# Tri_Btate_Bank.net
KiCad netlist of a schematic drawn in Altium Designer
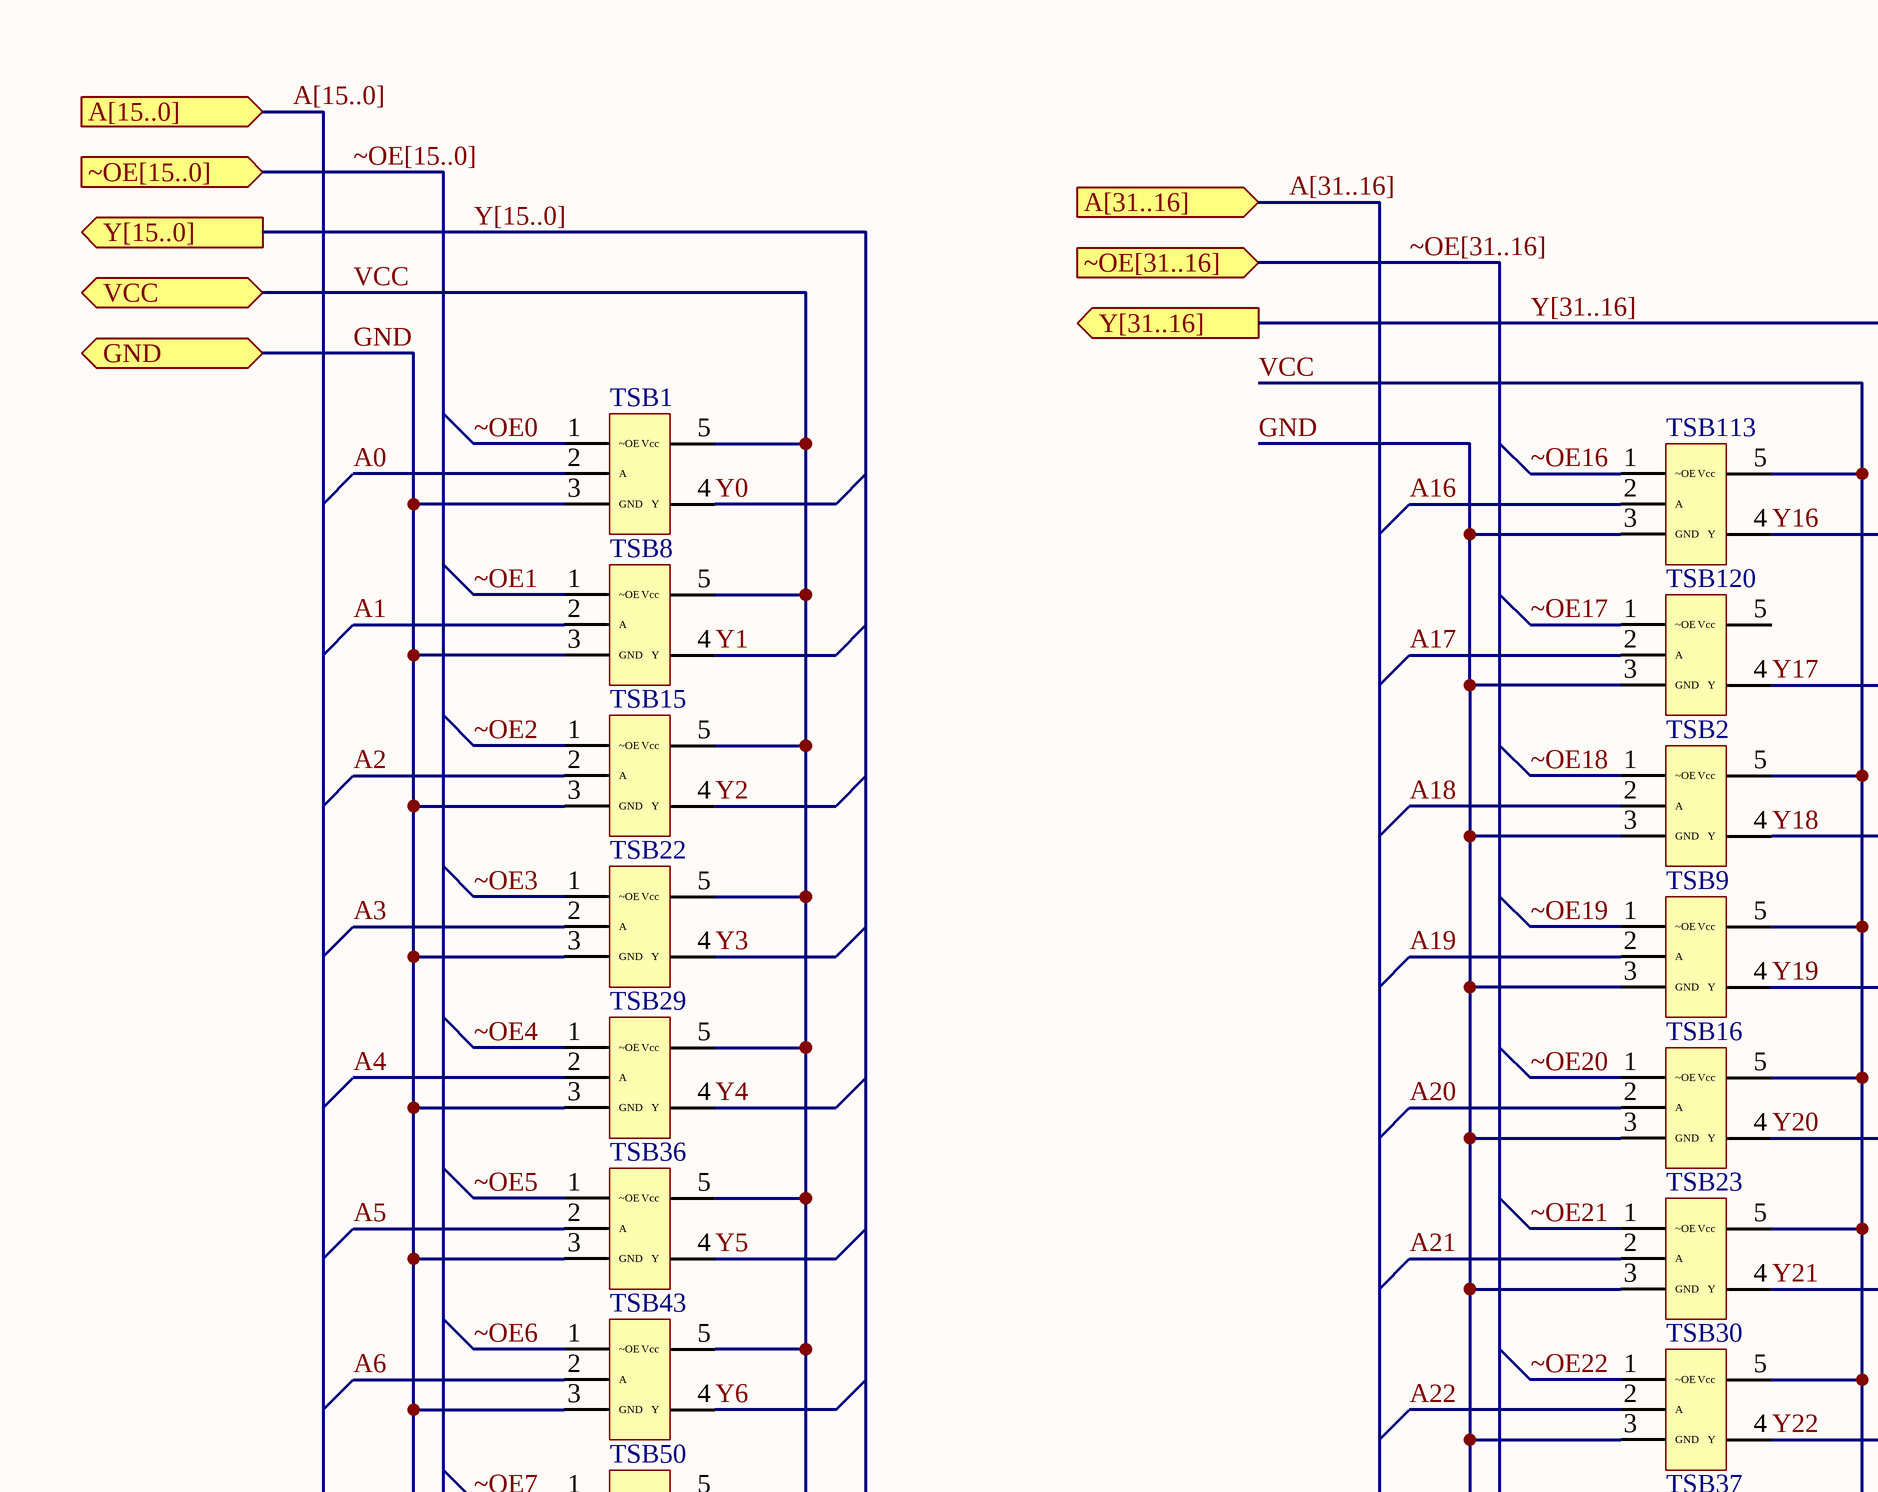
[diagram p0: Tri_Btate_Bank.SchDoc, top column 1 of 5]
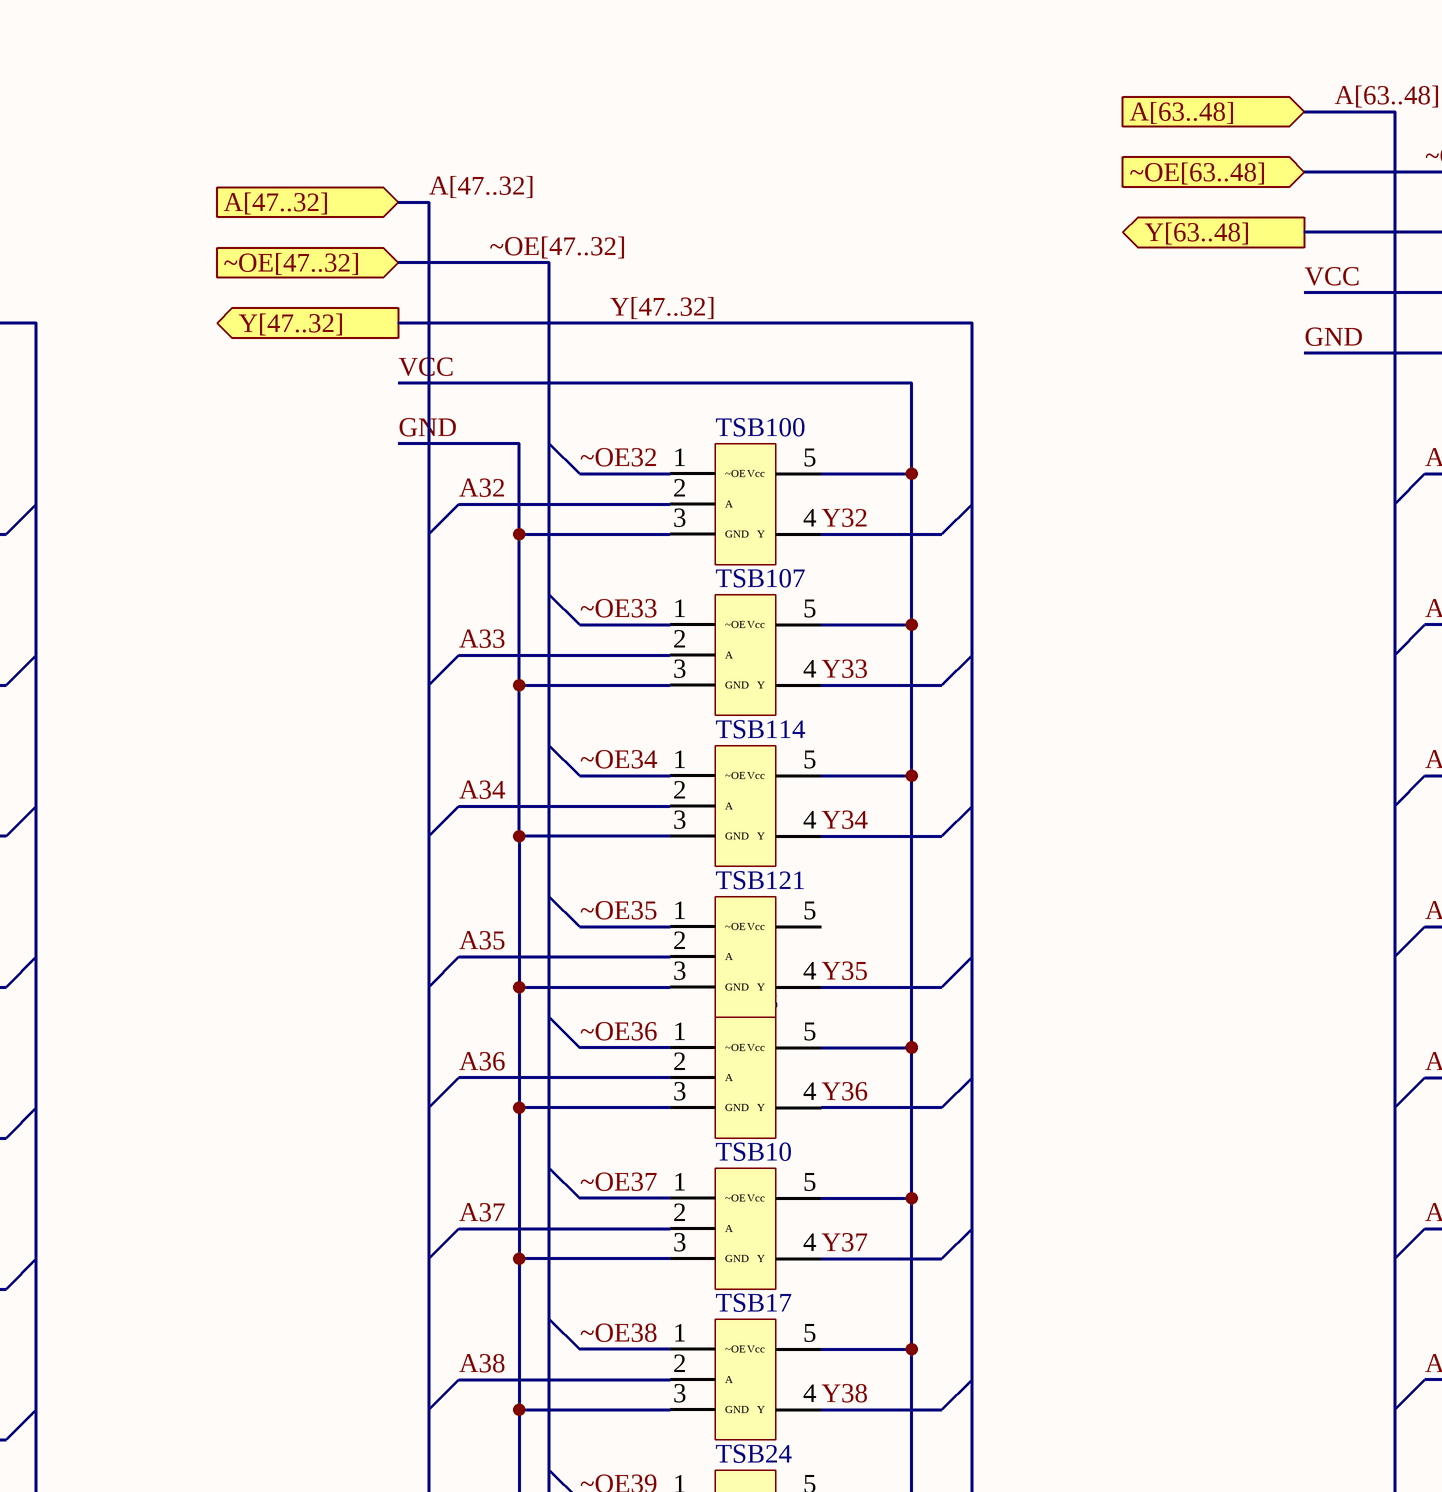
[diagram p1: Tri_Btate_Bank.SchDoc, top column 2 of 5]
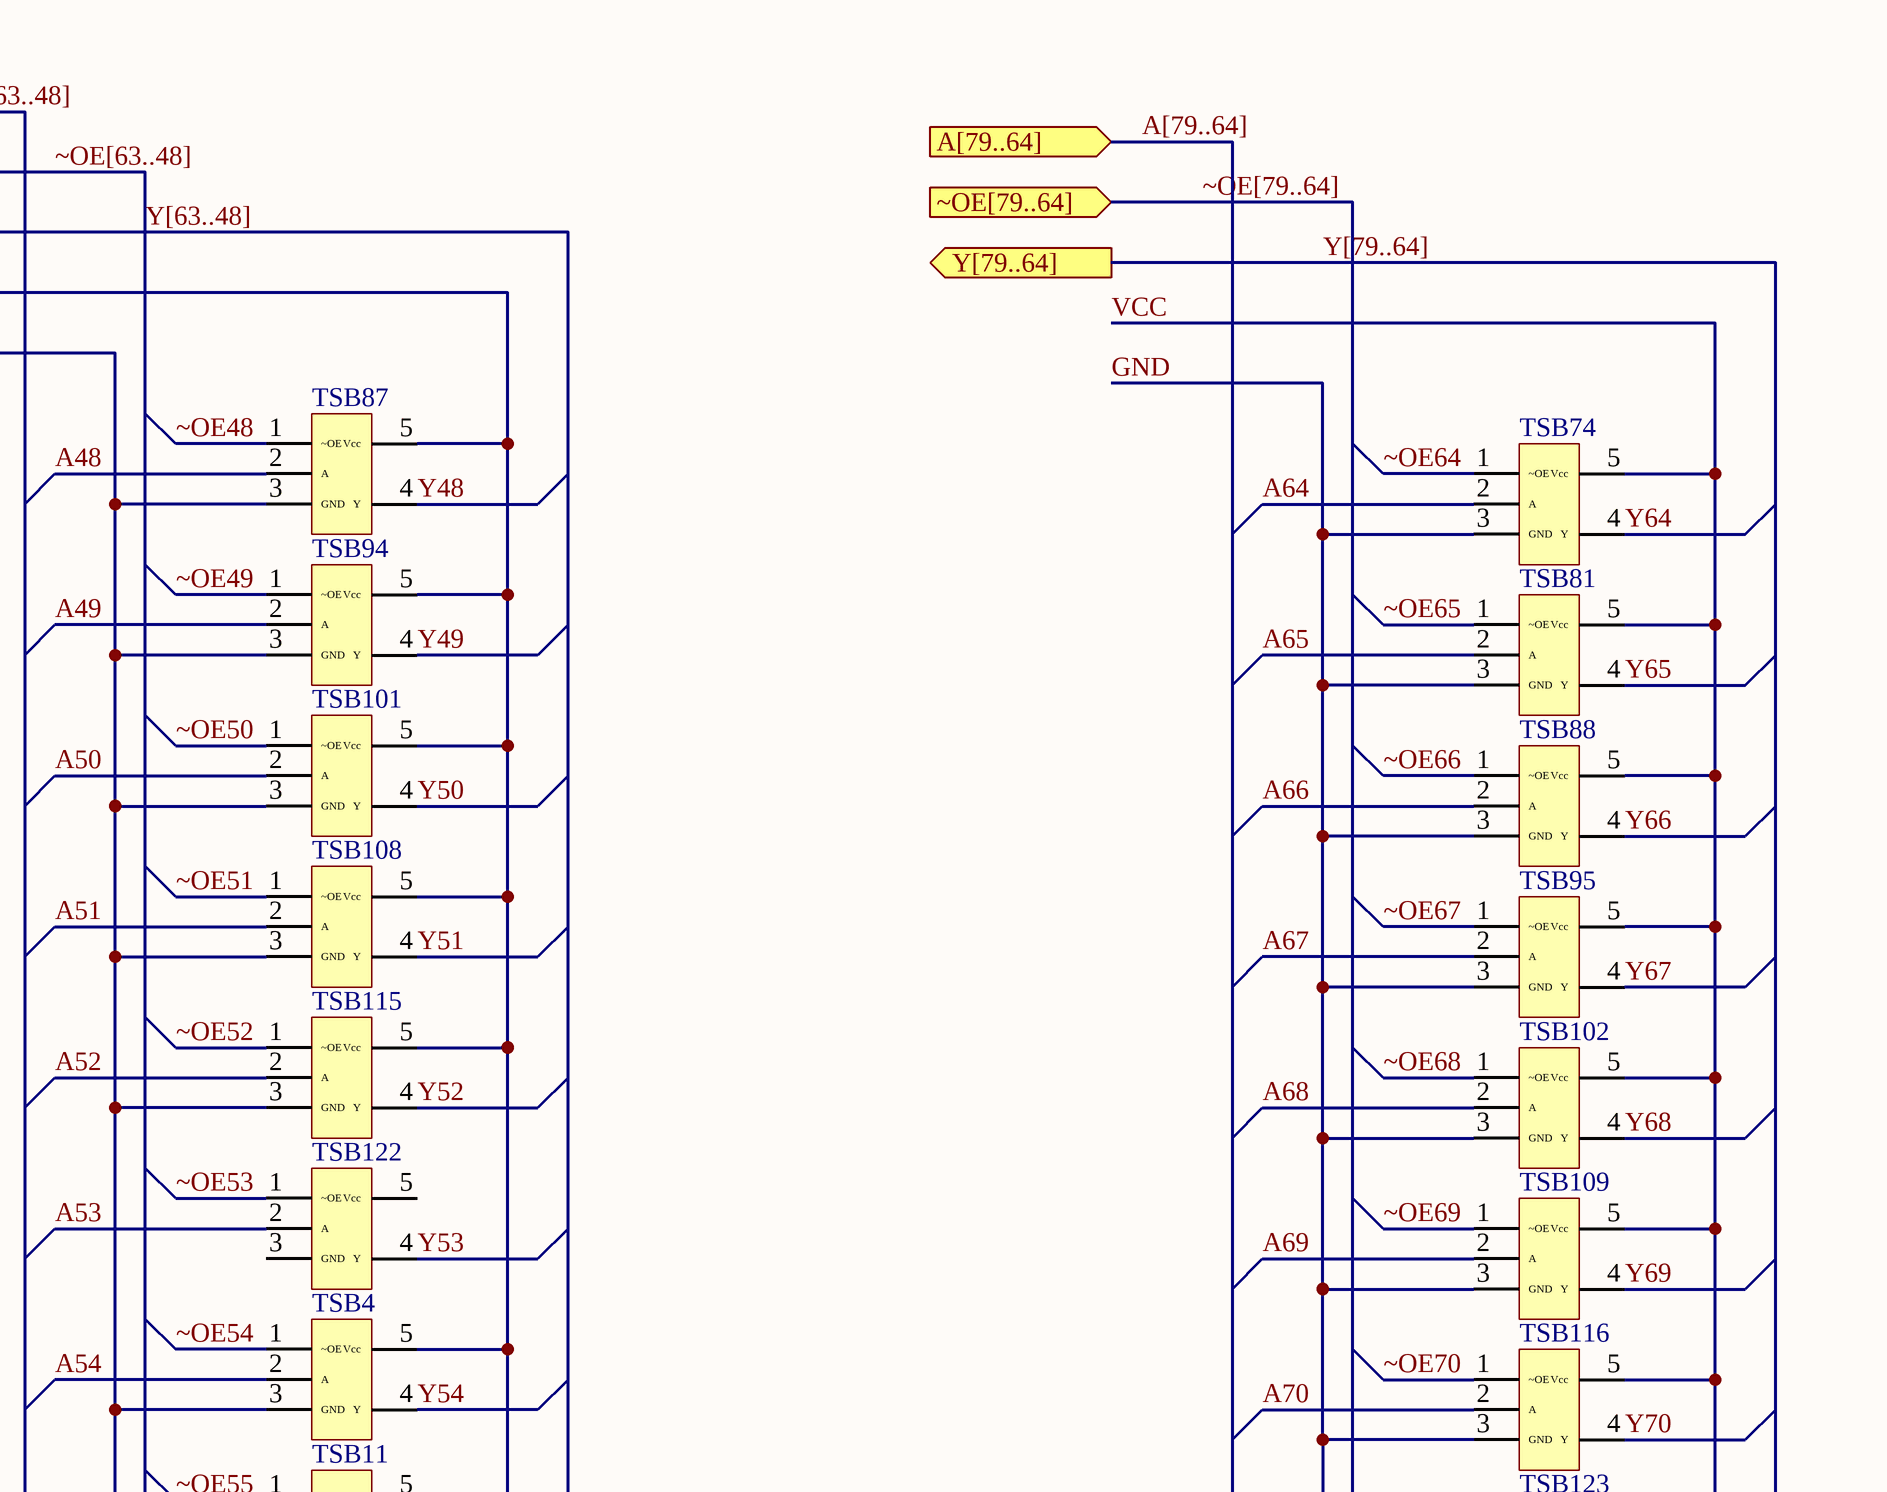
[diagram p2: Tri_Btate_Bank.SchDoc, top column 3 of 5]
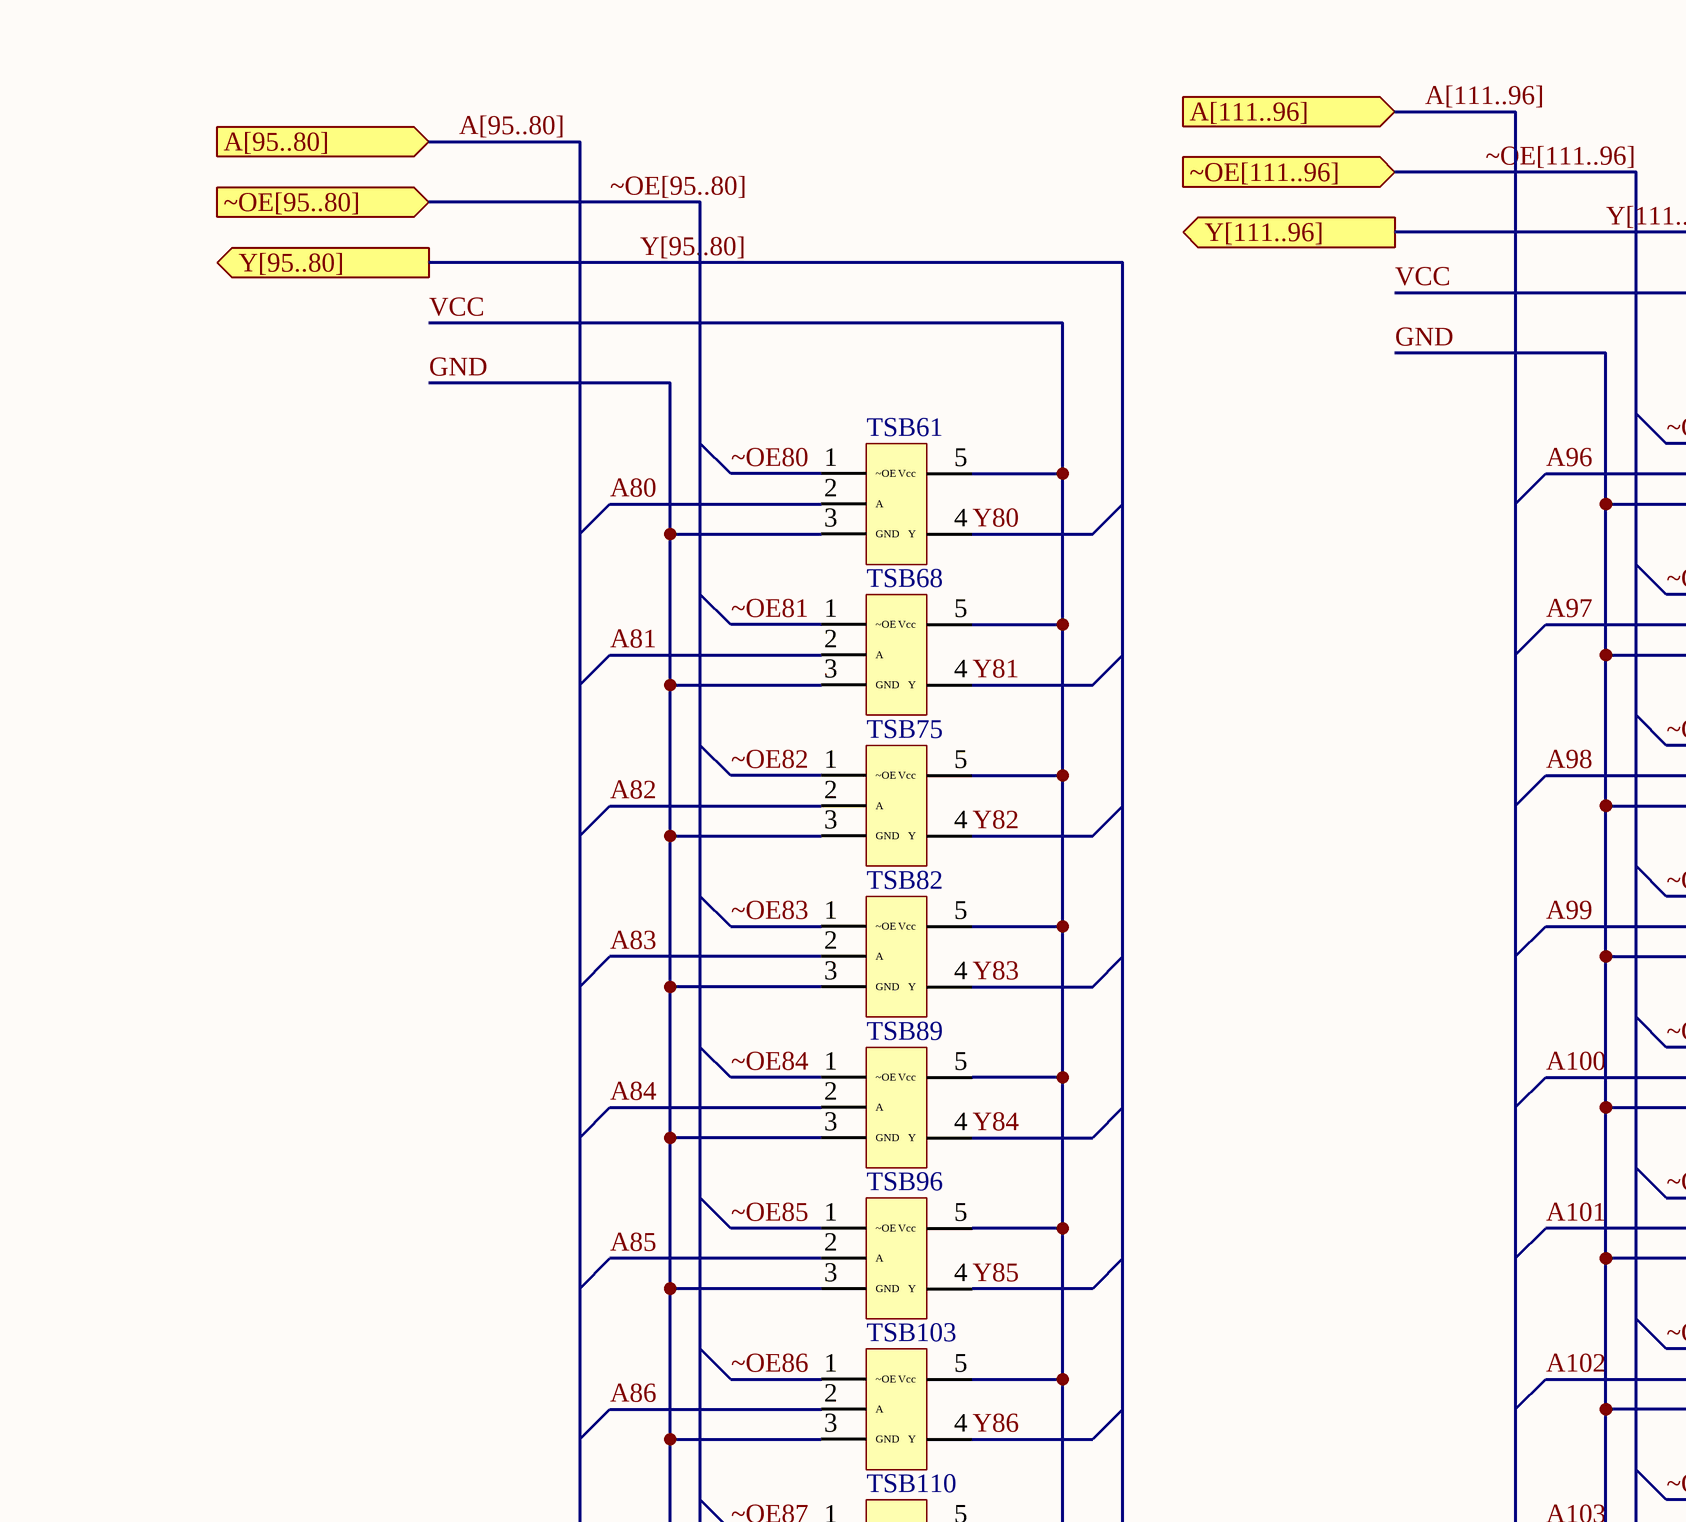
[diagram p3: Tri_Btate_Bank.SchDoc, top column 4 of 5]
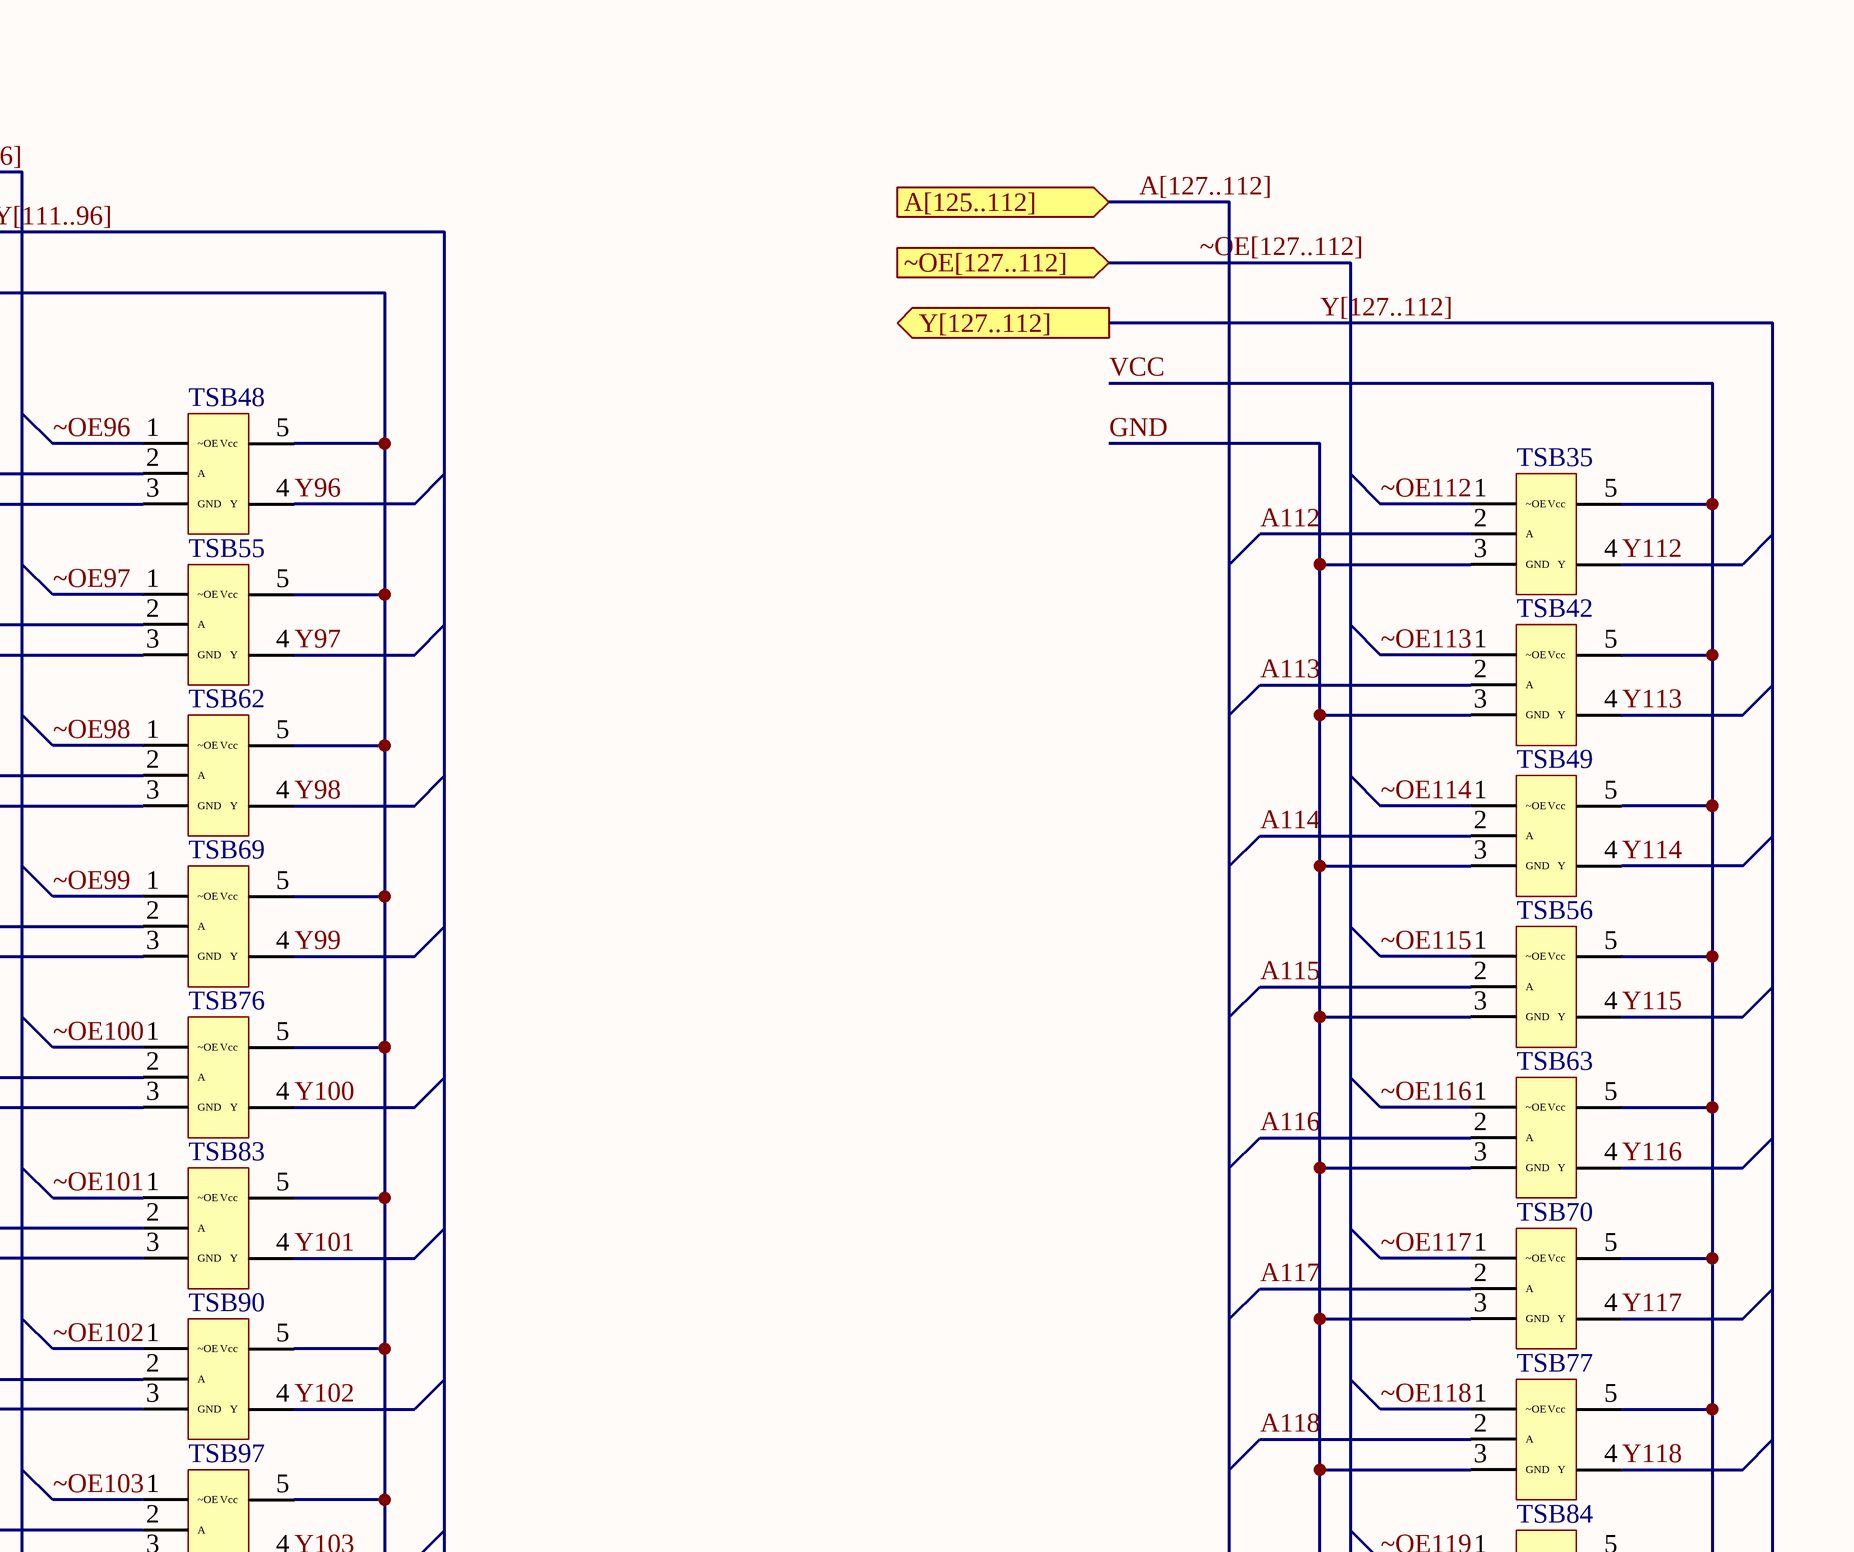
[diagram p4: Tri_Btate_Bank.SchDoc, top column 5 of 5]
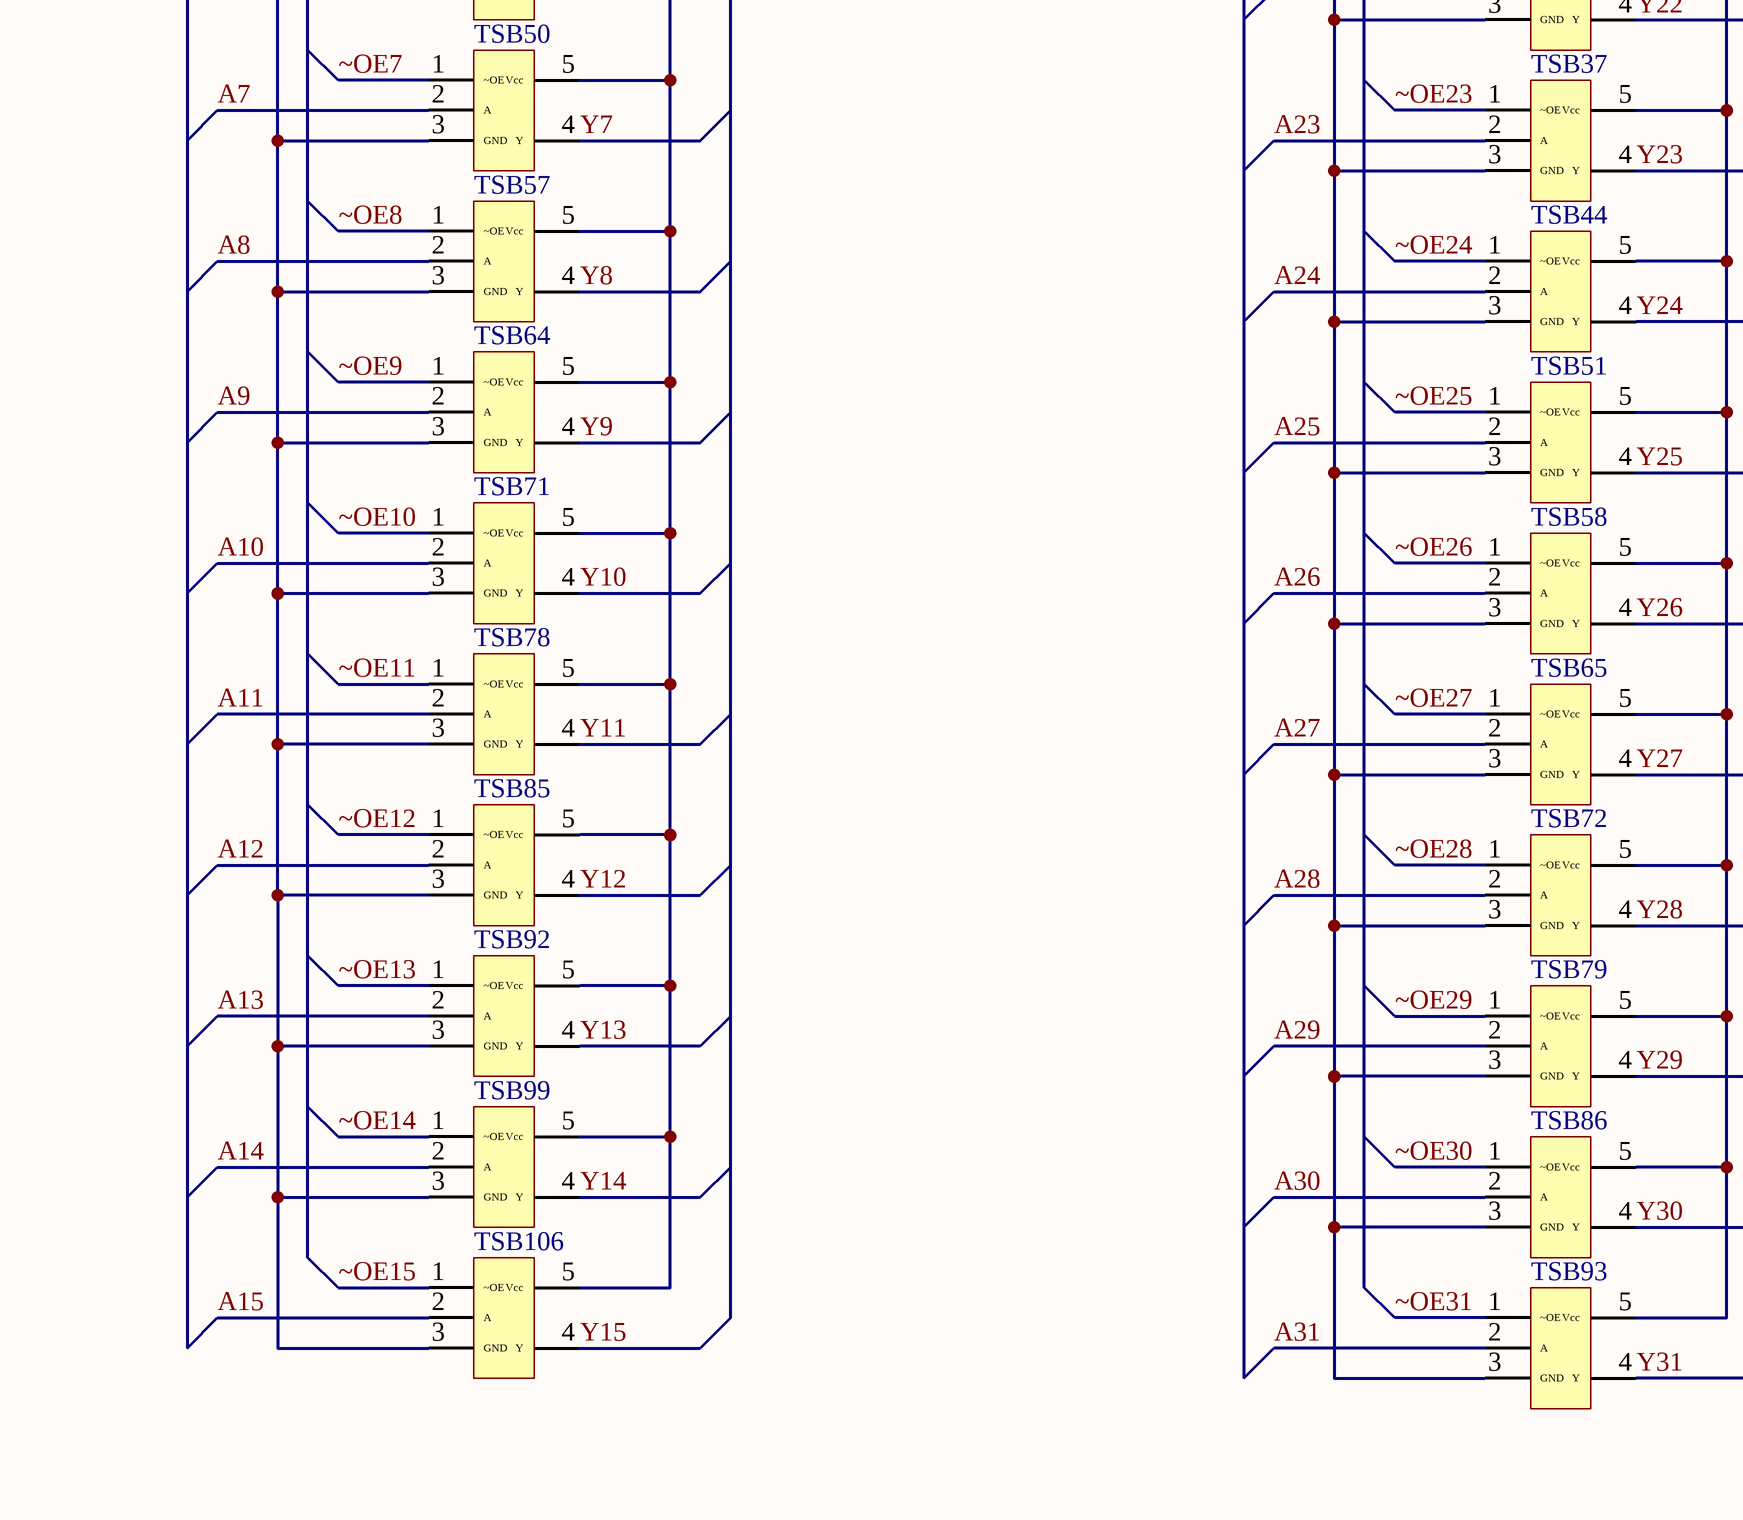
[diagram p5: Tri_Btate_Bank.SchDoc, bottom column 1 of 5]
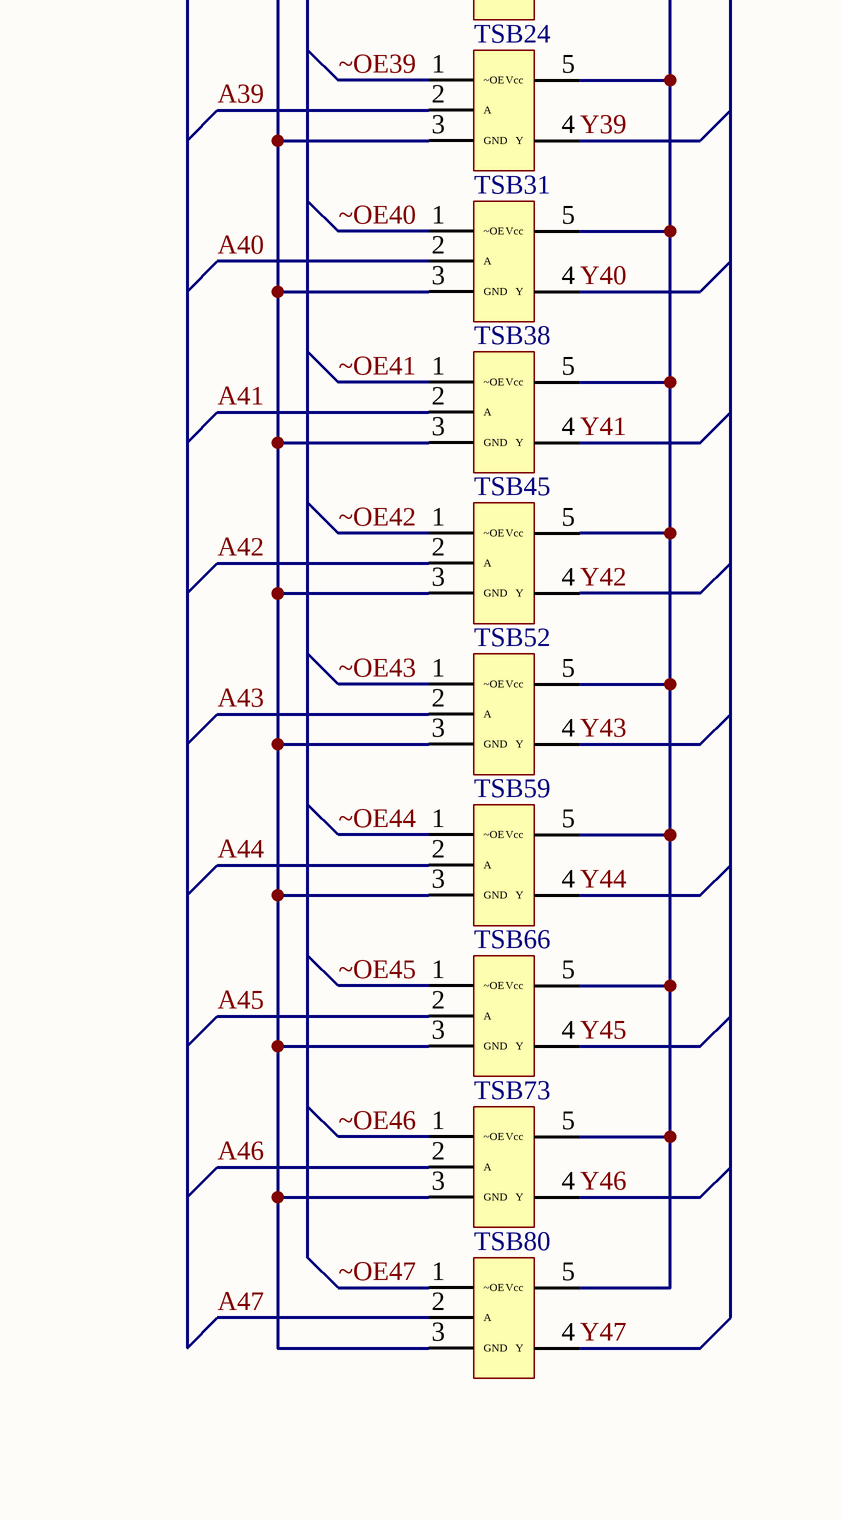
[diagram p6: Tri_Btate_Bank.SchDoc, bottom column 2 of 5]
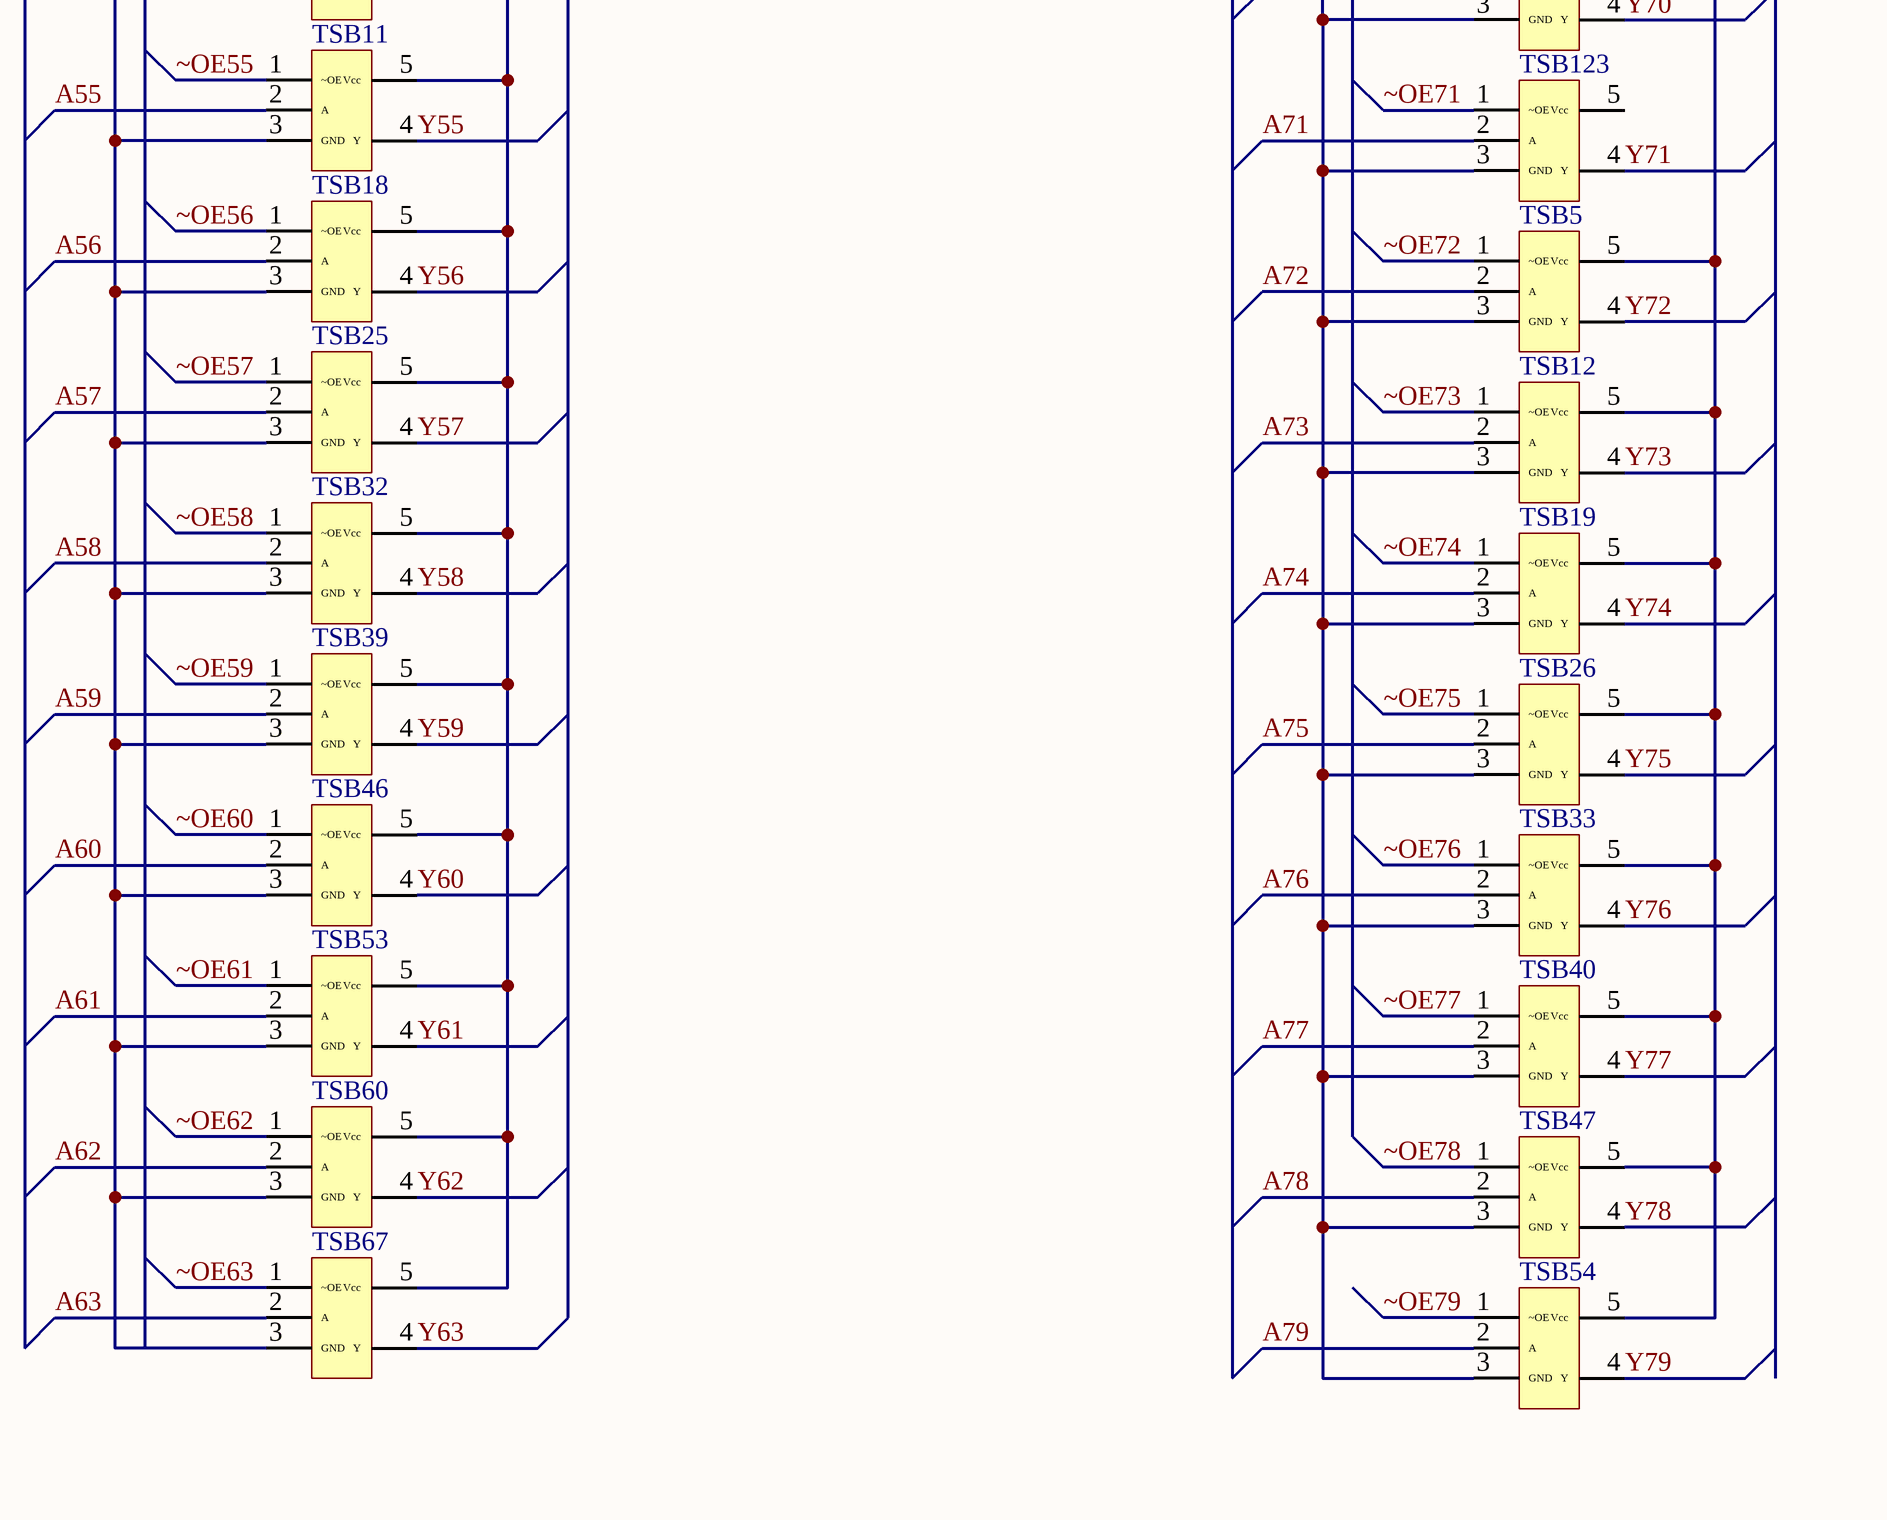
[diagram p7: Tri_Btate_Bank.SchDoc, bottom column 3 of 5]
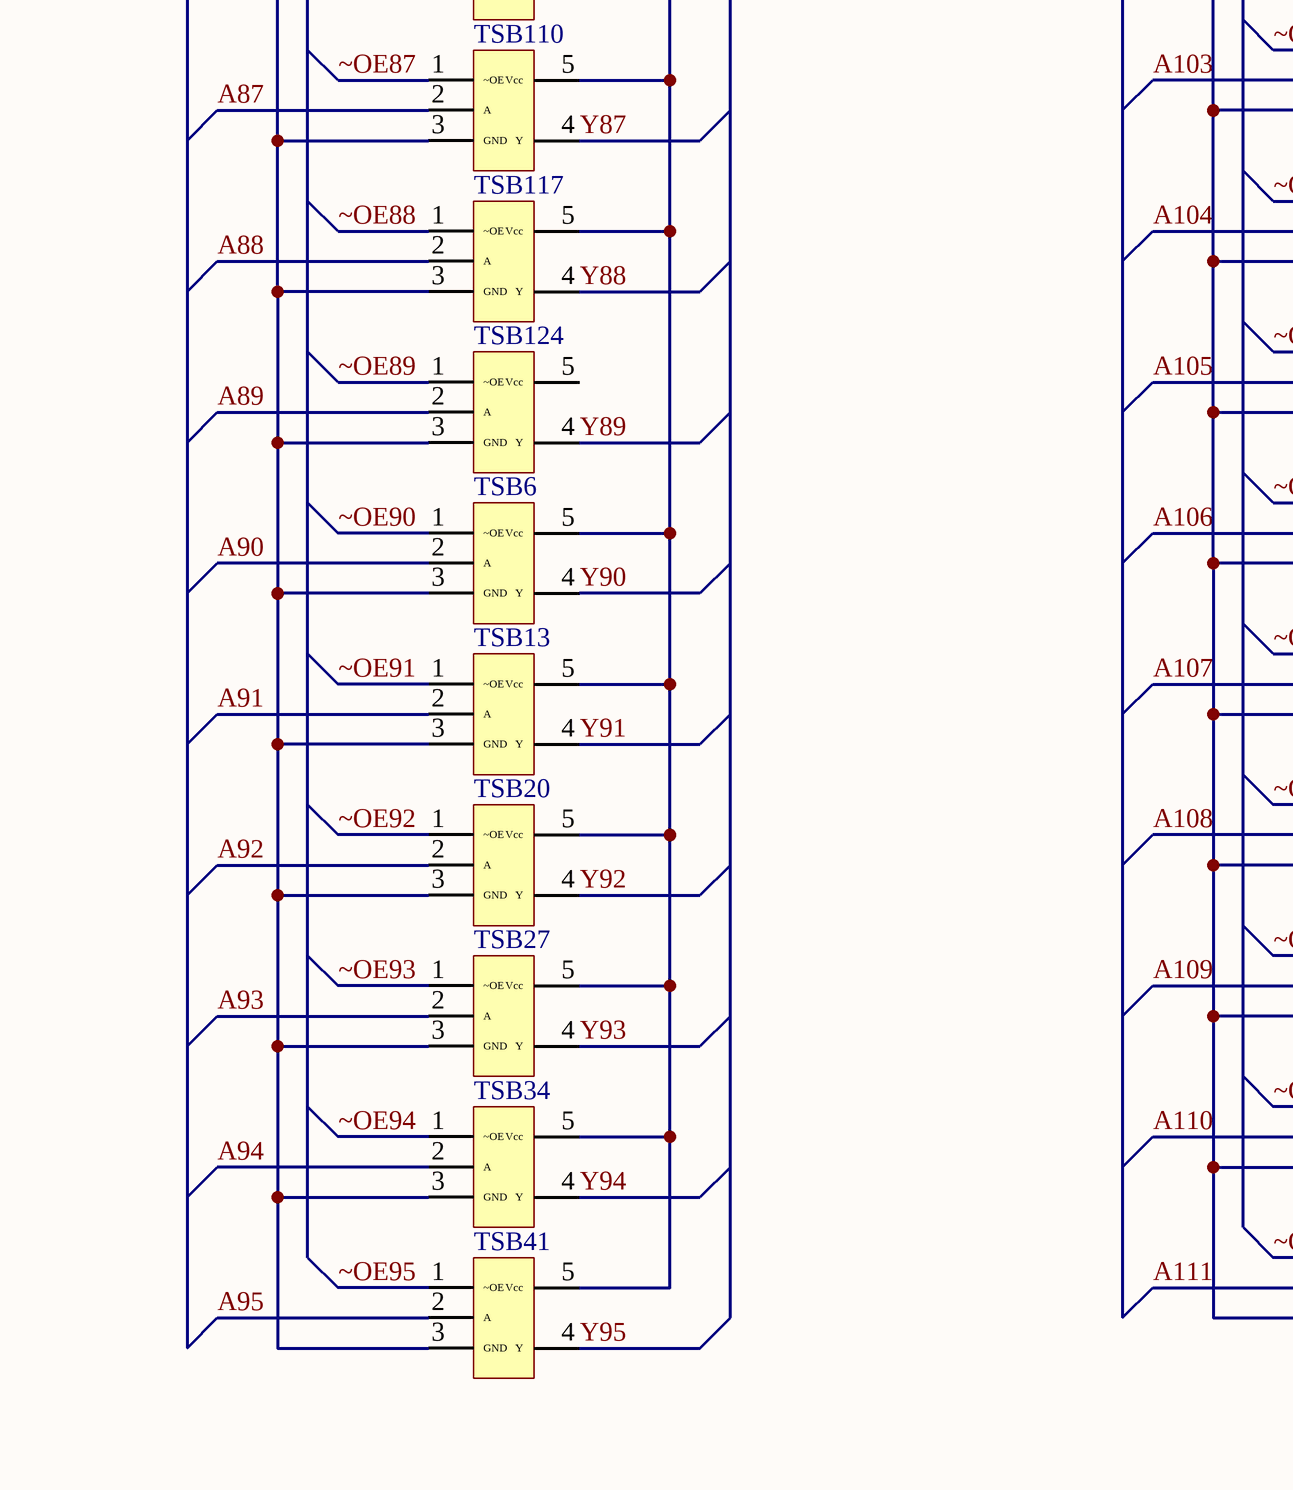
[diagram p8: Tri_Btate_Bank.SchDoc, bottom column 4 of 5]
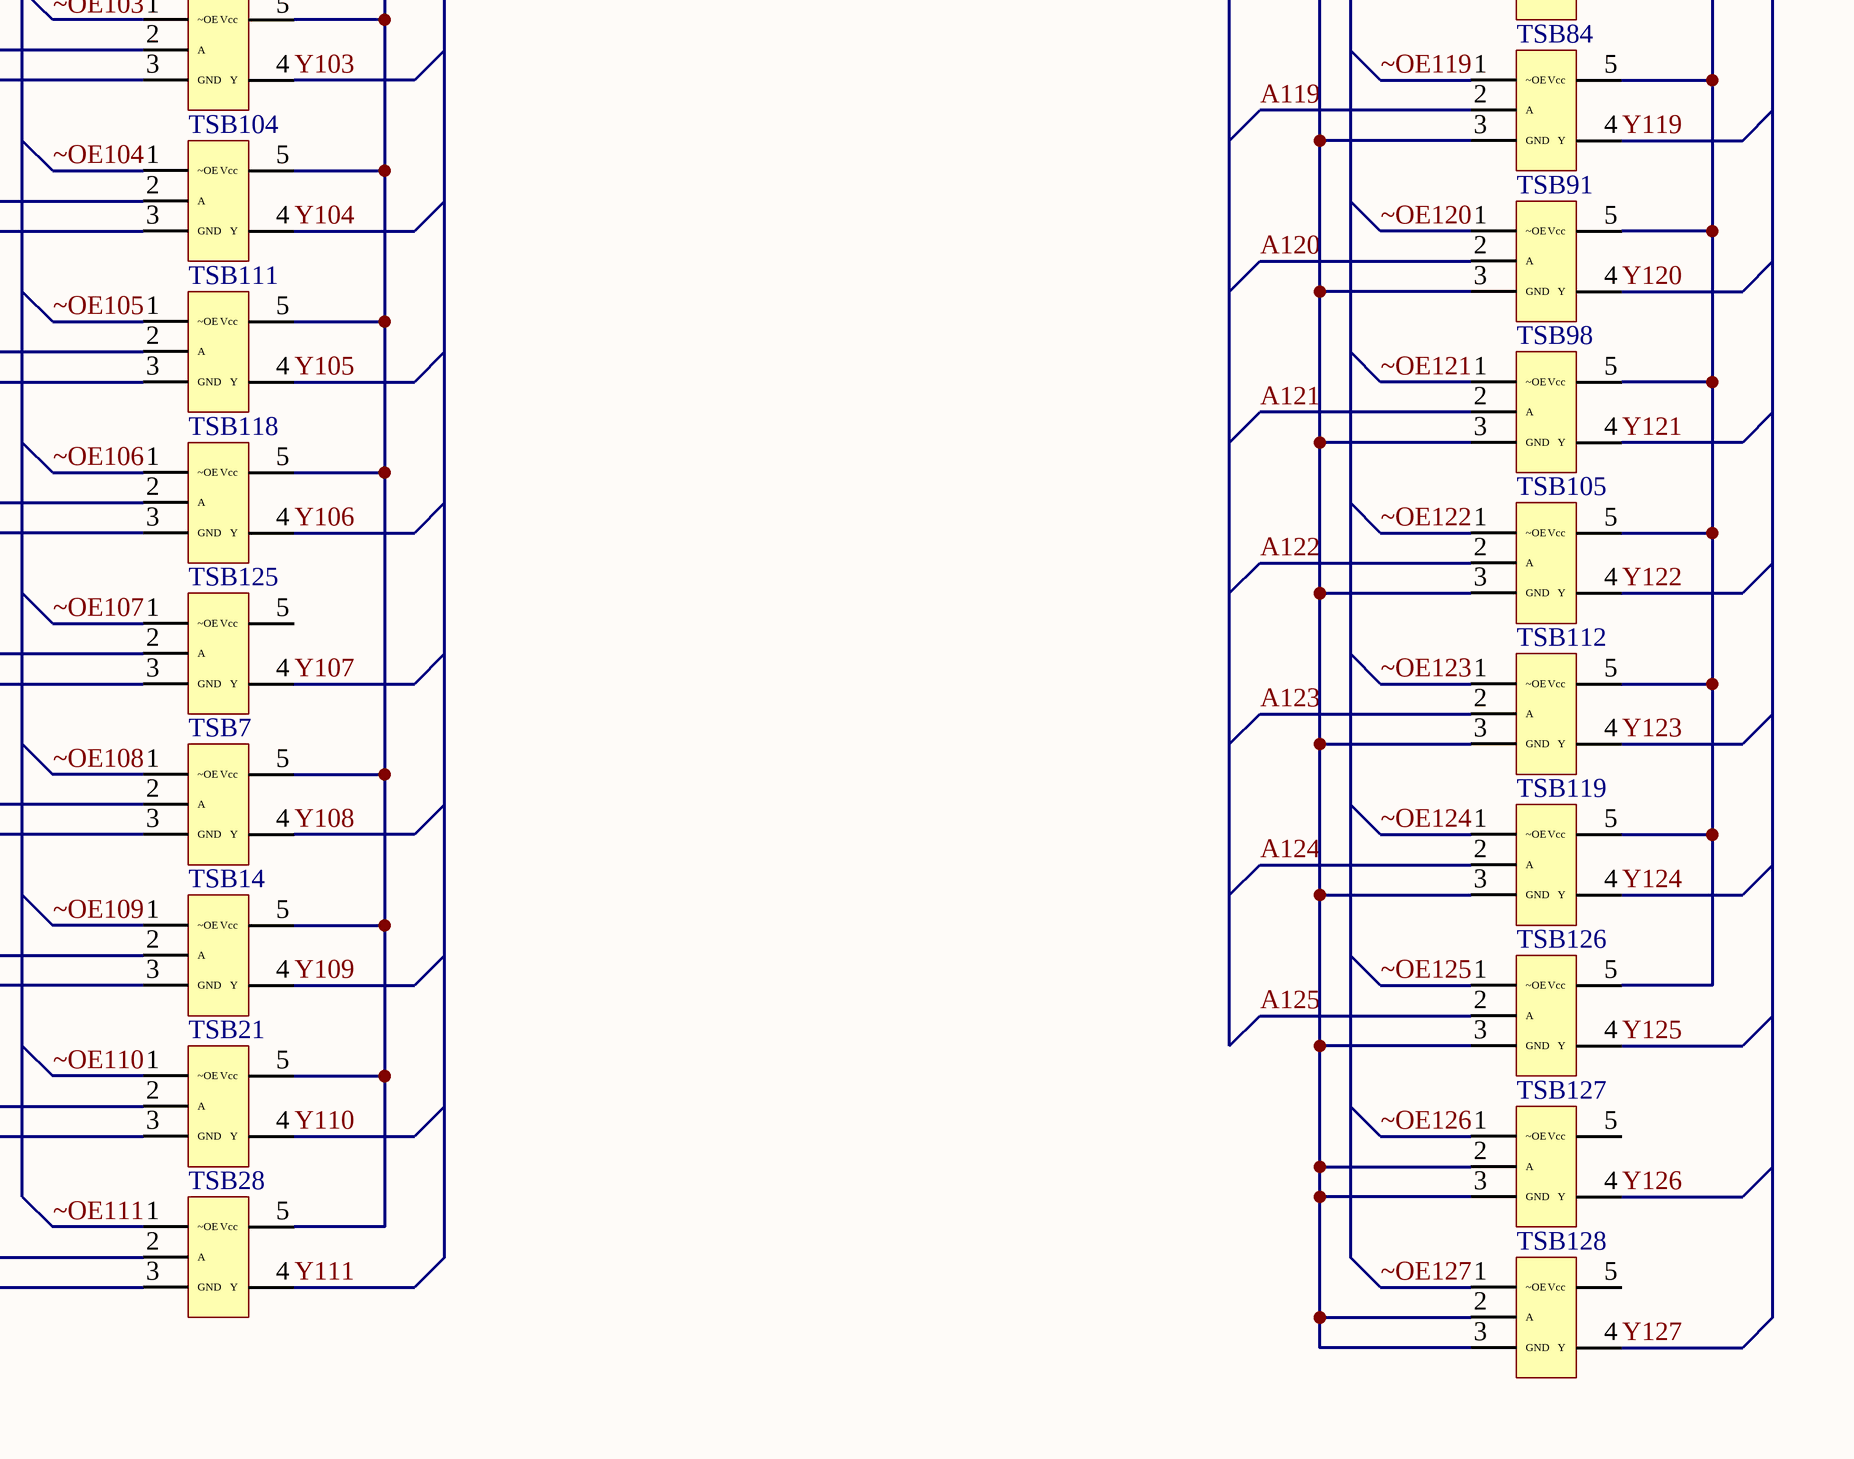
[diagram p9: Tri_Btate_Bank.SchDoc, bottom column 5 of 5]

(export (version "E")
  (design (tool "Eeschema 10.0.6"))
  (components
    (comp (ref "TSB1")
      (value "Tri-State Buffer Non-Inverting")
      (description "IC BUFF DVR TRI-ST N-INV 5TSSOP")
      (fields
        (field (name "MANUFACTURER") "NXP Semiconductors")
        (field (name "MANUFACTURER PART NUMBER") "74LVC1G125GW,125")
      )
      (libsource (lib "NORMS_LIB") (part "Tri-State Buffer Non-Inverting"))
    )
    (comp (ref "TSB2")
      (value "Tri-State Buffer Non-Inverting")
      (description "IC BUFF DVR TRI-ST N-INV 5TSSOP")
      (fields
        (field (name "MANUFACTURER") "NXP Semiconductors")
        (field (name "MANUFACTURER PART NUMBER") "74LVC1G125GW,125")
      )
      (libsource (lib "NORMS_LIB") (part "Tri-State Buffer Non-Inverting"))
    )
    (comp (ref "TSB3")
      (value "Tri-State Buffer Non-Inverting")
      (description "IC BUFF DVR TRI-ST N-INV 5TSSOP")
      (fields
        (field (name "MANUFACTURER") "NXP Semiconductors")
        (field (name "MANUFACTURER PART NUMBER") "74LVC1G125GW,125")
      )
      (libsource (lib "NORMS_LIB") (part "Tri-State Buffer Non-Inverting"))
    )
    (comp (ref "TSB4")
      (value "Tri-State Buffer Non-Inverting")
      (description "IC BUFF DVR TRI-ST N-INV 5TSSOP")
      (fields
        (field (name "MANUFACTURER") "NXP Semiconductors")
        (field (name "MANUFACTURER PART NUMBER") "74LVC1G125GW,125")
      )
      (libsource (lib "NORMS_LIB") (part "Tri-State Buffer Non-Inverting"))
    )
    (comp (ref "TSB5")
      (value "Tri-State Buffer Non-Inverting")
      (description "IC BUFF DVR TRI-ST N-INV 5TSSOP")
      (fields
        (field (name "MANUFACTURER") "NXP Semiconductors")
        (field (name "MANUFACTURER PART NUMBER") "74LVC1G125GW,125")
      )
      (libsource (lib "NORMS_LIB") (part "Tri-State Buffer Non-Inverting"))
    )
    (comp (ref "TSB6")
      (value "Tri-State Buffer Non-Inverting")
      (description "IC BUFF DVR TRI-ST N-INV 5TSSOP")
      (fields
        (field (name "MANUFACTURER") "NXP Semiconductors")
        (field (name "MANUFACTURER PART NUMBER") "74LVC1G125GW,125")
      )
      (libsource (lib "NORMS_LIB") (part "Tri-State Buffer Non-Inverting"))
    )
    (comp (ref "TSB7")
      (value "Tri-State Buffer Non-Inverting")
      (description "IC BUFF DVR TRI-ST N-INV 5TSSOP")
      (fields
        (field (name "MANUFACTURER") "NXP Semiconductors")
        (field (name "MANUFACTURER PART NUMBER") "74LVC1G125GW,125")
      )
      (libsource (lib "NORMS_LIB") (part "Tri-State Buffer Non-Inverting"))
    )
    (comp (ref "TSB8")
      (value "Tri-State Buffer Non-Inverting")
      (description "IC BUFF DVR TRI-ST N-INV 5TSSOP")
      (fields
        (field (name "MANUFACTURER") "NXP Semiconductors")
        (field (name "MANUFACTURER PART NUMBER") "74LVC1G125GW,125")
      )
      (libsource (lib "NORMS_LIB") (part "Tri-State Buffer Non-Inverting"))
    )
    (comp (ref "TSB9")
      (value "Tri-State Buffer Non-Inverting")
      (description "IC BUFF DVR TRI-ST N-INV 5TSSOP")
      (fields
        (field (name "MANUFACTURER") "NXP Semiconductors")
        (field (name "MANUFACTURER PART NUMBER") "74LVC1G125GW,125")
      )
      (libsource (lib "NORMS_LIB") (part "Tri-State Buffer Non-Inverting"))
    )
    (comp (ref "TSB10")
      (value "Tri-State Buffer Non-Inverting")
      (description "IC BUFF DVR TRI-ST N-INV 5TSSOP")
      (fields
        (field (name "MANUFACTURER") "NXP Semiconductors")
        (field (name "MANUFACTURER PART NUMBER") "74LVC1G125GW,125")
      )
      (libsource (lib "NORMS_LIB") (part "Tri-State Buffer Non-Inverting"))
    )
    (comp (ref "TSB11")
      (value "Tri-State Buffer Non-Inverting")
      (description "IC BUFF DVR TRI-ST N-INV 5TSSOP")
      (fields
        (field (name "MANUFACTURER") "NXP Semiconductors")
        (field (name "MANUFACTURER PART NUMBER") "74LVC1G125GW,125")
      )
      (libsource (lib "NORMS_LIB") (part "Tri-State Buffer Non-Inverting"))
    )
    (comp (ref "TSB12")
      (value "Tri-State Buffer Non-Inverting")
      (description "IC BUFF DVR TRI-ST N-INV 5TSSOP")
      (fields
        (field (name "MANUFACTURER") "NXP Semiconductors")
        (field (name "MANUFACTURER PART NUMBER") "74LVC1G125GW,125")
      )
      (libsource (lib "NORMS_LIB") (part "Tri-State Buffer Non-Inverting"))
    )
    (comp (ref "TSB13")
      (value "Tri-State Buffer Non-Inverting")
      (description "IC BUFF DVR TRI-ST N-INV 5TSSOP")
      (fields
        (field (name "MANUFACTURER") "NXP Semiconductors")
        (field (name "MANUFACTURER PART NUMBER") "74LVC1G125GW,125")
      )
      (libsource (lib "NORMS_LIB") (part "Tri-State Buffer Non-Inverting"))
    )
    (comp (ref "TSB14")
      (value "Tri-State Buffer Non-Inverting")
      (description "IC BUFF DVR TRI-ST N-INV 5TSSOP")
      (fields
        (field (name "MANUFACTURER") "NXP Semiconductors")
        (field (name "MANUFACTURER PART NUMBER") "74LVC1G125GW,125")
      )
      (libsource (lib "NORMS_LIB") (part "Tri-State Buffer Non-Inverting"))
    )
    (comp (ref "TSB15")
      (value "Tri-State Buffer Non-Inverting")
      (description "IC BUFF DVR TRI-ST N-INV 5TSSOP")
      (fields
        (field (name "MANUFACTURER") "NXP Semiconductors")
        (field (name "MANUFACTURER PART NUMBER") "74LVC1G125GW,125")
      )
      (libsource (lib "NORMS_LIB") (part "Tri-State Buffer Non-Inverting"))
    )
    (comp (ref "TSB16")
      (value "Tri-State Buffer Non-Inverting")
      (description "IC BUFF DVR TRI-ST N-INV 5TSSOP")
      (fields
        (field (name "MANUFACTURER") "NXP Semiconductors")
        (field (name "MANUFACTURER PART NUMBER") "74LVC1G125GW,125")
      )
      (libsource (lib "NORMS_LIB") (part "Tri-State Buffer Non-Inverting"))
    )
    (comp (ref "TSB17")
      (value "Tri-State Buffer Non-Inverting")
      (description "IC BUFF DVR TRI-ST N-INV 5TSSOP")
      (fields
        (field (name "MANUFACTURER") "NXP Semiconductors")
        (field (name "MANUFACTURER PART NUMBER") "74LVC1G125GW,125")
      )
      (libsource (lib "NORMS_LIB") (part "Tri-State Buffer Non-Inverting"))
    )
    (comp (ref "TSB18")
      (value "Tri-State Buffer Non-Inverting")
      (description "IC BUFF DVR TRI-ST N-INV 5TSSOP")
      (fields
        (field (name "MANUFACTURER") "NXP Semiconductors")
        (field (name "MANUFACTURER PART NUMBER") "74LVC1G125GW,125")
      )
      (libsource (lib "NORMS_LIB") (part "Tri-State Buffer Non-Inverting"))
    )
    (comp (ref "TSB19")
      (value "Tri-State Buffer Non-Inverting")
      (description "IC BUFF DVR TRI-ST N-INV 5TSSOP")
      (fields
        (field (name "MANUFACTURER") "NXP Semiconductors")
        (field (name "MANUFACTURER PART NUMBER") "74LVC1G125GW,125")
      )
      (libsource (lib "NORMS_LIB") (part "Tri-State Buffer Non-Inverting"))
    )
    (comp (ref "TSB20")
      (value "Tri-State Buffer Non-Inverting")
      (description "IC BUFF DVR TRI-ST N-INV 5TSSOP")
      (fields
        (field (name "MANUFACTURER") "NXP Semiconductors")
        (field (name "MANUFACTURER PART NUMBER") "74LVC1G125GW,125")
      )
      (libsource (lib "NORMS_LIB") (part "Tri-State Buffer Non-Inverting"))
    )
    (comp (ref "TSB21")
      (value "Tri-State Buffer Non-Inverting")
      (description "IC BUFF DVR TRI-ST N-INV 5TSSOP")
      (fields
        (field (name "MANUFACTURER") "NXP Semiconductors")
        (field (name "MANUFACTURER PART NUMBER") "74LVC1G125GW,125")
      )
      (libsource (lib "NORMS_LIB") (part "Tri-State Buffer Non-Inverting"))
    )
    (comp (ref "TSB22")
      (value "Tri-State Buffer Non-Inverting")
      (description "IC BUFF DVR TRI-ST N-INV 5TSSOP")
      (fields
        (field (name "MANUFACTURER") "NXP Semiconductors")
        (field (name "MANUFACTURER PART NUMBER") "74LVC1G125GW,125")
      )
      (libsource (lib "NORMS_LIB") (part "Tri-State Buffer Non-Inverting"))
    )
    (comp (ref "TSB23")
      (value "Tri-State Buffer Non-Inverting")
      (description "IC BUFF DVR TRI-ST N-INV 5TSSOP")
      (fields
        (field (name "MANUFACTURER") "NXP Semiconductors")
        (field (name "MANUFACTURER PART NUMBER") "74LVC1G125GW,125")
      )
      (libsource (lib "NORMS_LIB") (part "Tri-State Buffer Non-Inverting"))
    )
    (comp (ref "TSB24")
      (value "Tri-State Buffer Non-Inverting")
      (description "IC BUFF DVR TRI-ST N-INV 5TSSOP")
      (fields
        (field (name "MANUFACTURER") "NXP Semiconductors")
        (field (name "MANUFACTURER PART NUMBER") "74LVC1G125GW,125")
      )
      (libsource (lib "NORMS_LIB") (part "Tri-State Buffer Non-Inverting"))
    )
    (comp (ref "TSB25")
      (value "Tri-State Buffer Non-Inverting")
      (description "IC BUFF DVR TRI-ST N-INV 5TSSOP")
      (fields
        (field (name "MANUFACTURER") "NXP Semiconductors")
        (field (name "MANUFACTURER PART NUMBER") "74LVC1G125GW,125")
      )
      (libsource (lib "NORMS_LIB") (part "Tri-State Buffer Non-Inverting"))
    )
    (comp (ref "TSB26")
      (value "Tri-State Buffer Non-Inverting")
      (description "IC BUFF DVR TRI-ST N-INV 5TSSOP")
      (fields
        (field (name "MANUFACTURER") "NXP Semiconductors")
        (field (name "MANUFACTURER PART NUMBER") "74LVC1G125GW,125")
      )
      (libsource (lib "NORMS_LIB") (part "Tri-State Buffer Non-Inverting"))
    )
    (comp (ref "TSB27")
      (value "Tri-State Buffer Non-Inverting")
      (description "IC BUFF DVR TRI-ST N-INV 5TSSOP")
      (fields
        (field (name "MANUFACTURER") "NXP Semiconductors")
        (field (name "MANUFACTURER PART NUMBER") "74LVC1G125GW,125")
      )
      (libsource (lib "NORMS_LIB") (part "Tri-State Buffer Non-Inverting"))
    )
    (comp (ref "TSB28")
      (value "Tri-State Buffer Non-Inverting")
      (description "IC BUFF DVR TRI-ST N-INV 5TSSOP")
      (fields
        (field (name "MANUFACTURER") "NXP Semiconductors")
        (field (name "MANUFACTURER PART NUMBER") "74LVC1G125GW,125")
      )
      (libsource (lib "NORMS_LIB") (part "Tri-State Buffer Non-Inverting"))
    )
    (comp (ref "TSB29")
      (value "Tri-State Buffer Non-Inverting")
      (description "IC BUFF DVR TRI-ST N-INV 5TSSOP")
      (fields
        (field (name "MANUFACTURER") "NXP Semiconductors")
        (field (name "MANUFACTURER PART NUMBER") "74LVC1G125GW,125")
      )
      (libsource (lib "NORMS_LIB") (part "Tri-State Buffer Non-Inverting"))
    )
    (comp (ref "TSB30")
      (value "Tri-State Buffer Non-Inverting")
      (description "IC BUFF DVR TRI-ST N-INV 5TSSOP")
      (fields
        (field (name "MANUFACTURER") "NXP Semiconductors")
        (field (name "MANUFACTURER PART NUMBER") "74LVC1G125GW,125")
      )
      (libsource (lib "NORMS_LIB") (part "Tri-State Buffer Non-Inverting"))
    )
    (comp (ref "TSB31")
      (value "Tri-State Buffer Non-Inverting")
      (description "IC BUFF DVR TRI-ST N-INV 5TSSOP")
      (fields
        (field (name "MANUFACTURER") "NXP Semiconductors")
        (field (name "MANUFACTURER PART NUMBER") "74LVC1G125GW,125")
      )
      (libsource (lib "NORMS_LIB") (part "Tri-State Buffer Non-Inverting"))
    )
    (comp (ref "TSB32")
      (value "Tri-State Buffer Non-Inverting")
      (description "IC BUFF DVR TRI-ST N-INV 5TSSOP")
      (fields
        (field (name "MANUFACTURER") "NXP Semiconductors")
        (field (name "MANUFACTURER PART NUMBER") "74LVC1G125GW,125")
      )
      (libsource (lib "NORMS_LIB") (part "Tri-State Buffer Non-Inverting"))
    )
    (comp (ref "TSB33")
      (value "Tri-State Buffer Non-Inverting")
      (description "IC BUFF DVR TRI-ST N-INV 5TSSOP")
      (fields
        (field (name "MANUFACTURER") "NXP Semiconductors")
        (field (name "MANUFACTURER PART NUMBER") "74LVC1G125GW,125")
      )
      (libsource (lib "NORMS_LIB") (part "Tri-State Buffer Non-Inverting"))
    )
    (comp (ref "TSB34")
      (value "Tri-State Buffer Non-Inverting")
      (description "IC BUFF DVR TRI-ST N-INV 5TSSOP")
      (fields
        (field (name "MANUFACTURER") "NXP Semiconductors")
        (field (name "MANUFACTURER PART NUMBER") "74LVC1G125GW,125")
      )
      (libsource (lib "NORMS_LIB") (part "Tri-State Buffer Non-Inverting"))
    )
    (comp (ref "TSB35")
      (value "Tri-State Buffer Non-Inverting")
      (description "IC BUFF DVR TRI-ST N-INV 5TSSOP")
      (fields
        (field (name "MANUFACTURER") "NXP Semiconductors")
        (field (name "MANUFACTURER PART NUMBER") "74LVC1G125GW,125")
      )
      (libsource (lib "NORMS_LIB") (part "Tri-State Buffer Non-Inverting"))
    )
    (comp (ref "TSB36")
      (value "Tri-State Buffer Non-Inverting")
      (description "IC BUFF DVR TRI-ST N-INV 5TSSOP")
      (fields
        (field (name "MANUFACTURER") "NXP Semiconductors")
        (field (name "MANUFACTURER PART NUMBER") "74LVC1G125GW,125")
      )
      (libsource (lib "NORMS_LIB") (part "Tri-State Buffer Non-Inverting"))
    )
    (comp (ref "TSB37")
      (value "Tri-State Buffer Non-Inverting")
      (description "IC BUFF DVR TRI-ST N-INV 5TSSOP")
      (fields
        (field (name "MANUFACTURER") "NXP Semiconductors")
        (field (name "MANUFACTURER PART NUMBER") "74LVC1G125GW,125")
      )
      (libsource (lib "NORMS_LIB") (part "Tri-State Buffer Non-Inverting"))
    )
    (comp (ref "TSB38")
      (value "Tri-State Buffer Non-Inverting")
      (description "IC BUFF DVR TRI-ST N-INV 5TSSOP")
      (fields
        (field (name "MANUFACTURER") "NXP Semiconductors")
        (field (name "MANUFACTURER PART NUMBER") "74LVC1G125GW,125")
      )
      (libsource (lib "NORMS_LIB") (part "Tri-State Buffer Non-Inverting"))
    )
    (comp (ref "TSB39")
      (value "Tri-State Buffer Non-Inverting")
      (description "IC BUFF DVR TRI-ST N-INV 5TSSOP")
      (fields
        (field (name "MANUFACTURER") "NXP Semiconductors")
        (field (name "MANUFACTURER PART NUMBER") "74LVC1G125GW,125")
      )
      (libsource (lib "NORMS_LIB") (part "Tri-State Buffer Non-Inverting"))
    )
    (comp (ref "TSB40")
      (value "Tri-State Buffer Non-Inverting")
      (description "IC BUFF DVR TRI-ST N-INV 5TSSOP")
      (fields
        (field (name "MANUFACTURER") "NXP Semiconductors")
        (field (name "MANUFACTURER PART NUMBER") "74LVC1G125GW,125")
      )
      (libsource (lib "NORMS_LIB") (part "Tri-State Buffer Non-Inverting"))
    )
    (comp (ref "TSB41")
      (value "Tri-State Buffer Non-Inverting")
      (description "IC BUFF DVR TRI-ST N-INV 5TSSOP")
      (fields
        (field (name "MANUFACTURER") "NXP Semiconductors")
        (field (name "MANUFACTURER PART NUMBER") "74LVC1G125GW,125")
      )
      (libsource (lib "NORMS_LIB") (part "Tri-State Buffer Non-Inverting"))
    )
    (comp (ref "TSB42")
      (value "Tri-State Buffer Non-Inverting")
      (description "IC BUFF DVR TRI-ST N-INV 5TSSOP")
      (fields
        (field (name "MANUFACTURER") "NXP Semiconductors")
        (field (name "MANUFACTURER PART NUMBER") "74LVC1G125GW,125")
      )
      (libsource (lib "NORMS_LIB") (part "Tri-State Buffer Non-Inverting"))
    )
    (comp (ref "TSB43")
      (value "Tri-State Buffer Non-Inverting")
      (description "IC BUFF DVR TRI-ST N-INV 5TSSOP")
      (fields
        (field (name "MANUFACTURER") "NXP Semiconductors")
        (field (name "MANUFACTURER PART NUMBER") "74LVC1G125GW,125")
      )
      (libsource (lib "NORMS_LIB") (part "Tri-State Buffer Non-Inverting"))
    )
    (comp (ref "TSB44")
      (value "Tri-State Buffer Non-Inverting")
      (description "IC BUFF DVR TRI-ST N-INV 5TSSOP")
      (fields
        (field (name "MANUFACTURER") "NXP Semiconductors")
        (field (name "MANUFACTURER PART NUMBER") "74LVC1G125GW,125")
      )
      (libsource (lib "NORMS_LIB") (part "Tri-State Buffer Non-Inverting"))
    )
    (comp (ref "TSB45")
      (value "Tri-State Buffer Non-Inverting")
      (description "IC BUFF DVR TRI-ST N-INV 5TSSOP")
      (fields
        (field (name "MANUFACTURER") "NXP Semiconductors")
        (field (name "MANUFACTURER PART NUMBER") "74LVC1G125GW,125")
      )
      (libsource (lib "NORMS_LIB") (part "Tri-State Buffer Non-Inverting"))
    )
    (comp (ref "TSB46")
      (value "Tri-State Buffer Non-Inverting")
      (description "IC BUFF DVR TRI-ST N-INV 5TSSOP")
      (fields
        (field (name "MANUFACTURER") "NXP Semiconductors")
        (field (name "MANUFACTURER PART NUMBER") "74LVC1G125GW,125")
      )
      (libsource (lib "NORMS_LIB") (part "Tri-State Buffer Non-Inverting"))
    )
    (comp (ref "TSB47")
      (value "Tri-State Buffer Non-Inverting")
      (description "IC BUFF DVR TRI-ST N-INV 5TSSOP")
      (fields
        (field (name "MANUFACTURER") "NXP Semiconductors")
        (field (name "MANUFACTURER PART NUMBER") "74LVC1G125GW,125")
      )
      (libsource (lib "NORMS_LIB") (part "Tri-State Buffer Non-Inverting"))
    )
    (comp (ref "TSB48")
      (value "Tri-State Buffer Non-Inverting")
      (description "IC BUFF DVR TRI-ST N-INV 5TSSOP")
      (fields
        (field (name "MANUFACTURER") "NXP Semiconductors")
        (field (name "MANUFACTURER PART NUMBER") "74LVC1G125GW,125")
      )
      (libsource (lib "NORMS_LIB") (part "Tri-State Buffer Non-Inverting"))
    )
    (comp (ref "TSB49")
      (value "Tri-State Buffer Non-Inverting")
      (description "IC BUFF DVR TRI-ST N-INV 5TSSOP")
      (fields
        (field (name "MANUFACTURER") "NXP Semiconductors")
        (field (name "MANUFACTURER PART NUMBER") "74LVC1G125GW,125")
      )
      (libsource (lib "NORMS_LIB") (part "Tri-State Buffer Non-Inverting"))
    )
    (comp (ref "TSB50")
      (value "Tri-State Buffer Non-Inverting")
      (description "IC BUFF DVR TRI-ST N-INV 5TSSOP")
      (fields
        (field (name "MANUFACTURER") "NXP Semiconductors")
        (field (name "MANUFACTURER PART NUMBER") "74LVC1G125GW,125")
      )
      (libsource (lib "NORMS_LIB") (part "Tri-State Buffer Non-Inverting"))
    )
    (comp (ref "TSB51")
      (value "Tri-State Buffer Non-Inverting")
      (description "IC BUFF DVR TRI-ST N-INV 5TSSOP")
      (fields
        (field (name "MANUFACTURER") "NXP Semiconductors")
        (field (name "MANUFACTURER PART NUMBER") "74LVC1G125GW,125")
      )
      (libsource (lib "NORMS_LIB") (part "Tri-State Buffer Non-Inverting"))
    )
    (comp (ref "TSB52")
      (value "Tri-State Buffer Non-Inverting")
      (description "IC BUFF DVR TRI-ST N-INV 5TSSOP")
      (fields
        (field (name "MANUFACTURER") "NXP Semiconductors")
        (field (name "MANUFACTURER PART NUMBER") "74LVC1G125GW,125")
      )
      (libsource (lib "NORMS_LIB") (part "Tri-State Buffer Non-Inverting"))
    )
    (comp (ref "TSB53")
      (value "Tri-State Buffer Non-Inverting")
      (description "IC BUFF DVR TRI-ST N-INV 5TSSOP")
      (fields
        (field (name "MANUFACTURER") "NXP Semiconductors")
        (field (name "MANUFACTURER PART NUMBER") "74LVC1G125GW,125")
      )
      (libsource (lib "NORMS_LIB") (part "Tri-State Buffer Non-Inverting"))
    )
    (comp (ref "TSB54")
      (value "Tri-State Buffer Non-Inverting")
      (description "IC BUFF DVR TRI-ST N-INV 5TSSOP")
      (fields
        (field (name "MANUFACTURER") "NXP Semiconductors")
        (field (name "MANUFACTURER PART NUMBER") "74LVC1G125GW,125")
      )
      (libsource (lib "NORMS_LIB") (part "Tri-State Buffer Non-Inverting"))
    )
    (comp (ref "TSB55")
      (value "Tri-State Buffer Non-Inverting")
      (description "IC BUFF DVR TRI-ST N-INV 5TSSOP")
      (fields
        (field (name "MANUFACTURER") "NXP Semiconductors")
        (field (name "MANUFACTURER PART NUMBER") "74LVC1G125GW,125")
      )
      (libsource (lib "NORMS_LIB") (part "Tri-State Buffer Non-Inverting"))
    )
    (comp (ref "TSB56")
      (value "Tri-State Buffer Non-Inverting")
      (description "IC BUFF DVR TRI-ST N-INV 5TSSOP")
      (fields
        (field (name "MANUFACTURER") "NXP Semiconductors")
        (field (name "MANUFACTURER PART NUMBER") "74LVC1G125GW,125")
      )
      (libsource (lib "NORMS_LIB") (part "Tri-State Buffer Non-Inverting"))
    )
    (comp (ref "TSB57")
      (value "Tri-State Buffer Non-Inverting")
      (description "IC BUFF DVR TRI-ST N-INV 5TSSOP")
      (fields
        (field (name "MANUFACTURER") "NXP Semiconductors")
        (field (name "MANUFACTURER PART NUMBER") "74LVC1G125GW,125")
      )
      (libsource (lib "NORMS_LIB") (part "Tri-State Buffer Non-Inverting"))
    )
    (comp (ref "TSB58")
      (value "Tri-State Buffer Non-Inverting")
      (description "IC BUFF DVR TRI-ST N-INV 5TSSOP")
      (fields
        (field (name "MANUFACTURER") "NXP Semiconductors")
        (field (name "MANUFACTURER PART NUMBER") "74LVC1G125GW,125")
      )
      (libsource (lib "NORMS_LIB") (part "Tri-State Buffer Non-Inverting"))
    )
    (comp (ref "TSB59")
      (value "Tri-State Buffer Non-Inverting")
      (description "IC BUFF DVR TRI-ST N-INV 5TSSOP")
      (fields
        (field (name "MANUFACTURER") "NXP Semiconductors")
        (field (name "MANUFACTURER PART NUMBER") "74LVC1G125GW,125")
      )
      (libsource (lib "NORMS_LIB") (part "Tri-State Buffer Non-Inverting"))
    )
    (comp (ref "TSB60")
      (value "Tri-State Buffer Non-Inverting")
      (description "IC BUFF DVR TRI-ST N-INV 5TSSOP")
      (fields
        (field (name "MANUFACTURER") "NXP Semiconductors")
        (field (name "MANUFACTURER PART NUMBER") "74LVC1G125GW,125")
      )
      (libsource (lib "NORMS_LIB") (part "Tri-State Buffer Non-Inverting"))
    )
    (comp (ref "TSB61")
      (value "Tri-State Buffer Non-Inverting")
      (description "IC BUFF DVR TRI-ST N-INV 5TSSOP")
      (fields
        (field (name "MANUFACTURER") "NXP Semiconductors")
        (field (name "MANUFACTURER PART NUMBER") "74LVC1G125GW,125")
      )
      (libsource (lib "NORMS_LIB") (part "Tri-State Buffer Non-Inverting"))
    )
    (comp (ref "TSB62")
      (value "Tri-State Buffer Non-Inverting")
      (description "IC BUFF DVR TRI-ST N-INV 5TSSOP")
      (fields
        (field (name "MANUFACTURER") "NXP Semiconductors")
        (field (name "MANUFACTURER PART NUMBER") "74LVC1G125GW,125")
      )
      (libsource (lib "NORMS_LIB") (part "Tri-State Buffer Non-Inverting"))
    )
    (comp (ref "TSB63")
      (value "Tri-State Buffer Non-Inverting")
      (description "IC BUFF DVR TRI-ST N-INV 5TSSOP")
      (fields
        (field (name "MANUFACTURER") "NXP Semiconductors")
        (field (name "MANUFACTURER PART NUMBER") "74LVC1G125GW,125")
      )
      (libsource (lib "NORMS_LIB") (part "Tri-State Buffer Non-Inverting"))
    )
    (comp (ref "TSB64")
      (value "Tri-State Buffer Non-Inverting")
      (description "IC BUFF DVR TRI-ST N-INV 5TSSOP")
      (fields
        (field (name "MANUFACTURER") "NXP Semiconductors")
        (field (name "MANUFACTURER PART NUMBER") "74LVC1G125GW,125")
      )
      (libsource (lib "NORMS_LIB") (part "Tri-State Buffer Non-Inverting"))
    )
    (comp (ref "TSB65")
      (value "Tri-State Buffer Non-Inverting")
      (description "IC BUFF DVR TRI-ST N-INV 5TSSOP")
      (fields
        (field (name "MANUFACTURER") "NXP Semiconductors")
        (field (name "MANUFACTURER PART NUMBER") "74LVC1G125GW,125")
      )
      (libsource (lib "NORMS_LIB") (part "Tri-State Buffer Non-Inverting"))
    )
    (comp (ref "TSB66")
      (value "Tri-State Buffer Non-Inverting")
      (description "IC BUFF DVR TRI-ST N-INV 5TSSOP")
      (fields
        (field (name "MANUFACTURER") "NXP Semiconductors")
        (field (name "MANUFACTURER PART NUMBER") "74LVC1G125GW,125")
      )
      (libsource (lib "NORMS_LIB") (part "Tri-State Buffer Non-Inverting"))
    )
    (comp (ref "TSB67")
      (value "Tri-State Buffer Non-Inverting")
      (description "IC BUFF DVR TRI-ST N-INV 5TSSOP")
      (fields
        (field (name "MANUFACTURER") "NXP Semiconductors")
        (field (name "MANUFACTURER PART NUMBER") "74LVC1G125GW,125")
      )
      (libsource (lib "NORMS_LIB") (part "Tri-State Buffer Non-Inverting"))
    )
    (comp (ref "TSB68")
      (value "Tri-State Buffer Non-Inverting")
      (description "IC BUFF DVR TRI-ST N-INV 5TSSOP")
      (fields
        (field (name "MANUFACTURER") "NXP Semiconductors")
        (field (name "MANUFACTURER PART NUMBER") "74LVC1G125GW,125")
      )
      (libsource (lib "NORMS_LIB") (part "Tri-State Buffer Non-Inverting"))
    )
    (comp (ref "TSB69")
      (value "Tri-State Buffer Non-Inverting")
      (description "IC BUFF DVR TRI-ST N-INV 5TSSOP")
      (fields
        (field (name "MANUFACTURER") "NXP Semiconductors")
        (field (name "MANUFACTURER PART NUMBER") "74LVC1G125GW,125")
      )
      (libsource (lib "NORMS_LIB") (part "Tri-State Buffer Non-Inverting"))
    )
    (comp (ref "TSB70")
      (value "Tri-State Buffer Non-Inverting")
      (description "IC BUFF DVR TRI-ST N-INV 5TSSOP")
      (fields
        (field (name "MANUFACTURER") "NXP Semiconductors")
        (field (name "MANUFACTURER PART NUMBER") "74LVC1G125GW,125")
      )
      (libsource (lib "NORMS_LIB") (part "Tri-State Buffer Non-Inverting"))
    )
    (comp (ref "TSB71")
      (value "Tri-State Buffer Non-Inverting")
      (description "IC BUFF DVR TRI-ST N-INV 5TSSOP")
      (fields
        (field (name "MANUFACTURER") "NXP Semiconductors")
        (field (name "MANUFACTURER PART NUMBER") "74LVC1G125GW,125")
      )
      (libsource (lib "NORMS_LIB") (part "Tri-State Buffer Non-Inverting"))
    )
    (comp (ref "TSB72")
      (value "Tri-State Buffer Non-Inverting")
      (description "IC BUFF DVR TRI-ST N-INV 5TSSOP")
      (fields
        (field (name "MANUFACTURER") "NXP Semiconductors")
        (field (name "MANUFACTURER PART NUMBER") "74LVC1G125GW,125")
      )
      (libsource (lib "NORMS_LIB") (part "Tri-State Buffer Non-Inverting"))
    )
    (comp (ref "TSB73")
      (value "Tri-State Buffer Non-Inverting")
      (description "IC BUFF DVR TRI-ST N-INV 5TSSOP")
      (fields
        (field (name "MANUFACTURER") "NXP Semiconductors")
        (field (name "MANUFACTURER PART NUMBER") "74LVC1G125GW,125")
      )
      (libsource (lib "NORMS_LIB") (part "Tri-State Buffer Non-Inverting"))
    )
    (comp (ref "TSB74")
      (value "Tri-State Buffer Non-Inverting")
      (description "IC BUFF DVR TRI-ST N-INV 5TSSOP")
      (fields
        (field (name "MANUFACTURER") "NXP Semiconductors")
        (field (name "MANUFACTURER PART NUMBER") "74LVC1G125GW,125")
      )
      (libsource (lib "NORMS_LIB") (part "Tri-State Buffer Non-Inverting"))
    )
    (comp (ref "TSB75")
      (value "Tri-State Buffer Non-Inverting")
      (description "IC BUFF DVR TRI-ST N-INV 5TSSOP")
      (fields
        (field (name "MANUFACTURER") "NXP Semiconductors")
        (field (name "MANUFACTURER PART NUMBER") "74LVC1G125GW,125")
      )
      (libsource (lib "NORMS_LIB") (part "Tri-State Buffer Non-Inverting"))
    )
    (comp (ref "TSB76")
      (value "Tri-State Buffer Non-Inverting")
      (description "IC BUFF DVR TRI-ST N-INV 5TSSOP")
      (fields
        (field (name "MANUFACTURER") "NXP Semiconductors")
        (field (name "MANUFACTURER PART NUMBER") "74LVC1G125GW,125")
      )
      (libsource (lib "NORMS_LIB") (part "Tri-State Buffer Non-Inverting"))
    )
    (comp (ref "TSB77")
      (value "Tri-State Buffer Non-Inverting")
      (description "IC BUFF DVR TRI-ST N-INV 5TSSOP")
      (fields
        (field (name "MANUFACTURER") "NXP Semiconductors")
        (field (name "MANUFACTURER PART NUMBER") "74LVC1G125GW,125")
      )
      (libsource (lib "NORMS_LIB") (part "Tri-State Buffer Non-Inverting"))
    )
    (comp (ref "TSB78")
      (value "Tri-State Buffer Non-Inverting")
      (description "IC BUFF DVR TRI-ST N-INV 5TSSOP")
      (fields
        (field (name "MANUFACTURER") "NXP Semiconductors")
        (field (name "MANUFACTURER PART NUMBER") "74LVC1G125GW,125")
      )
      (libsource (lib "NORMS_LIB") (part "Tri-State Buffer Non-Inverting"))
    )
    (comp (ref "TSB79")
      (value "Tri-State Buffer Non-Inverting")
      (description "IC BUFF DVR TRI-ST N-INV 5TSSOP")
      (fields
        (field (name "MANUFACTURER") "NXP Semiconductors")
        (field (name "MANUFACTURER PART NUMBER") "74LVC1G125GW,125")
      )
      (libsource (lib "NORMS_LIB") (part "Tri-State Buffer Non-Inverting"))
    )
    (comp (ref "TSB80")
      (value "Tri-State Buffer Non-Inverting")
      (description "IC BUFF DVR TRI-ST N-INV 5TSSOP")
      (fields
        (field (name "MANUFACTURER") "NXP Semiconductors")
        (field (name "MANUFACTURER PART NUMBER") "74LVC1G125GW,125")
      )
      (libsource (lib "NORMS_LIB") (part "Tri-State Buffer Non-Inverting"))
    )
    (comp (ref "TSB81")
      (value "Tri-State Buffer Non-Inverting")
      (description "IC BUFF DVR TRI-ST N-INV 5TSSOP")
      (fields
        (field (name "MANUFACTURER") "NXP Semiconductors")
        (field (name "MANUFACTURER PART NUMBER") "74LVC1G125GW,125")
      )
      (libsource (lib "NORMS_LIB") (part "Tri-State Buffer Non-Inverting"))
    )
    (comp (ref "TSB82")
      (value "Tri-State Buffer Non-Inverting")
      (description "IC BUFF DVR TRI-ST N-INV 5TSSOP")
      (fields
        (field (name "MANUFACTURER") "NXP Semiconductors")
        (field (name "MANUFACTURER PART NUMBER") "74LVC1G125GW,125")
      )
      (libsource (lib "NORMS_LIB") (part "Tri-State Buffer Non-Inverting"))
    )
    (comp (ref "TSB83")
      (value "Tri-State Buffer Non-Inverting")
      (description "IC BUFF DVR TRI-ST N-INV 5TSSOP")
      (fields
        (field (name "MANUFACTURER") "NXP Semiconductors")
        (field (name "MANUFACTURER PART NUMBER") "74LVC1G125GW,125")
      )
      (libsource (lib "NORMS_LIB") (part "Tri-State Buffer Non-Inverting"))
    )
    (comp (ref "TSB84")
      (value "Tri-State Buffer Non-Inverting")
      (description "IC BUFF DVR TRI-ST N-INV 5TSSOP")
      (fields
        (field (name "MANUFACTURER") "NXP Semiconductors")
        (field (name "MANUFACTURER PART NUMBER") "74LVC1G125GW,125")
      )
      (libsource (lib "NORMS_LIB") (part "Tri-State Buffer Non-Inverting"))
    )
    (comp (ref "TSB85")
      (value "Tri-State Buffer Non-Inverting")
      (description "IC BUFF DVR TRI-ST N-INV 5TSSOP")
      (fields
        (field (name "MANUFACTURER") "NXP Semiconductors")
        (field (name "MANUFACTURER PART NUMBER") "74LVC1G125GW,125")
      )
      (libsource (lib "NORMS_LIB") (part "Tri-State Buffer Non-Inverting"))
    )
    (comp (ref "TSB86")
      (value "Tri-State Buffer Non-Inverting")
      (description "IC BUFF DVR TRI-ST N-INV 5TSSOP")
      (fields
        (field (name "MANUFACTURER") "NXP Semiconductors")
        (field (name "MANUFACTURER PART NUMBER") "74LVC1G125GW,125")
      )
      (libsource (lib "NORMS_LIB") (part "Tri-State Buffer Non-Inverting"))
    )
    (comp (ref "TSB87")
      (value "Tri-State Buffer Non-Inverting")
      (description "IC BUFF DVR TRI-ST N-INV 5TSSOP")
      (fields
        (field (name "MANUFACTURER") "NXP Semiconductors")
        (field (name "MANUFACTURER PART NUMBER") "74LVC1G125GW,125")
      )
      (libsource (lib "NORMS_LIB") (part "Tri-State Buffer Non-Inverting"))
    )
    (comp (ref "TSB88")
      (value "Tri-State Buffer Non-Inverting")
      (description "IC BUFF DVR TRI-ST N-INV 5TSSOP")
      (fields
        (field (name "MANUFACTURER") "NXP Semiconductors")
        (field (name "MANUFACTURER PART NUMBER") "74LVC1G125GW,125")
      )
      (libsource (lib "NORMS_LIB") (part "Tri-State Buffer Non-Inverting"))
    )
    (comp (ref "TSB89")
      (value "Tri-State Buffer Non-Inverting")
      (description "IC BUFF DVR TRI-ST N-INV 5TSSOP")
      (fields
        (field (name "MANUFACTURER") "NXP Semiconductors")
        (field (name "MANUFACTURER PART NUMBER") "74LVC1G125GW,125")
      )
      (libsource (lib "NORMS_LIB") (part "Tri-State Buffer Non-Inverting"))
    )
    (comp (ref "TSB90")
      (value "Tri-State Buffer Non-Inverting")
      (description "IC BUFF DVR TRI-ST N-INV 5TSSOP")
      (fields
        (field (name "MANUFACTURER") "NXP Semiconductors")
        (field (name "MANUFACTURER PART NUMBER") "74LVC1G125GW,125")
      )
      (libsource (lib "NORMS_LIB") (part "Tri-State Buffer Non-Inverting"))
    )
    (comp (ref "TSB91")
      (value "Tri-State Buffer Non-Inverting")
      (description "IC BUFF DVR TRI-ST N-INV 5TSSOP")
      (fields
        (field (name "MANUFACTURER") "NXP Semiconductors")
        (field (name "MANUFACTURER PART NUMBER") "74LVC1G125GW,125")
      )
      (libsource (lib "NORMS_LIB") (part "Tri-State Buffer Non-Inverting"))
    )
    (comp (ref "TSB92")
      (value "Tri-State Buffer Non-Inverting")
      (description "IC BUFF DVR TRI-ST N-INV 5TSSOP")
      (fields
        (field (name "MANUFACTURER") "NXP Semiconductors")
        (field (name "MANUFACTURER PART NUMBER") "74LVC1G125GW,125")
      )
      (libsource (lib "NORMS_LIB") (part "Tri-State Buffer Non-Inverting"))
    )
    (comp (ref "TSB93")
      (value "Tri-State Buffer Non-Inverting")
      (description "IC BUFF DVR TRI-ST N-INV 5TSSOP")
      (fields
        (field (name "MANUFACTURER") "NXP Semiconductors")
        (field (name "MANUFACTURER PART NUMBER") "74LVC1G125GW,125")
      )
      (libsource (lib "NORMS_LIB") (part "Tri-State Buffer Non-Inverting"))
    )
    (comp (ref "TSB94")
      (value "Tri-State Buffer Non-Inverting")
      (description "IC BUFF DVR TRI-ST N-INV 5TSSOP")
      (fields
        (field (name "MANUFACTURER") "NXP Semiconductors")
        (field (name "MANUFACTURER PART NUMBER") "74LVC1G125GW,125")
      )
      (libsource (lib "NORMS_LIB") (part "Tri-State Buffer Non-Inverting"))
    )
    (comp (ref "TSB95")
      (value "Tri-State Buffer Non-Inverting")
      (description "IC BUFF DVR TRI-ST N-INV 5TSSOP")
      (fields
        (field (name "MANUFACTURER") "NXP Semiconductors")
        (field (name "MANUFACTURER PART NUMBER") "74LVC1G125GW,125")
      )
      (libsource (lib "NORMS_LIB") (part "Tri-State Buffer Non-Inverting"))
    )
    (comp (ref "TSB96")
      (value "Tri-State Buffer Non-Inverting")
      (description "IC BUFF DVR TRI-ST N-INV 5TSSOP")
      (fields
        (field (name "MANUFACTURER") "NXP Semiconductors")
        (field (name "MANUFACTURER PART NUMBER") "74LVC1G125GW,125")
      )
      (libsource (lib "NORMS_LIB") (part "Tri-State Buffer Non-Inverting"))
    )
    (comp (ref "TSB97")
      (value "Tri-State Buffer Non-Inverting")
      (description "IC BUFF DVR TRI-ST N-INV 5TSSOP")
      (fields
        (field (name "MANUFACTURER") "NXP Semiconductors")
        (field (name "MANUFACTURER PART NUMBER") "74LVC1G125GW,125")
      )
      (libsource (lib "NORMS_LIB") (part "Tri-State Buffer Non-Inverting"))
    )
    (comp (ref "TSB98")
      (value "Tri-State Buffer Non-Inverting")
      (description "IC BUFF DVR TRI-ST N-INV 5TSSOP")
      (fields
        (field (name "MANUFACTURER") "NXP Semiconductors")
        (field (name "MANUFACTURER PART NUMBER") "74LVC1G125GW,125")
      )
      (libsource (lib "NORMS_LIB") (part "Tri-State Buffer Non-Inverting"))
    )
    (comp (ref "TSB99")
      (value "Tri-State Buffer Non-Inverting")
      (description "IC BUFF DVR TRI-ST N-INV 5TSSOP")
      (fields
        (field (name "MANUFACTURER") "NXP Semiconductors")
        (field (name "MANUFACTURER PART NUMBER") "74LVC1G125GW,125")
      )
      (libsource (lib "NORMS_LIB") (part "Tri-State Buffer Non-Inverting"))
    )
    (comp (ref "TSB100")
      (value "Tri-State Buffer Non-Inverting")
      (description "IC BUFF DVR TRI-ST N-INV 5TSSOP")
      (fields
        (field (name "MANUFACTURER") "NXP Semiconductors")
        (field (name "MANUFACTURER PART NUMBER") "74LVC1G125GW,125")
      )
      (libsource (lib "NORMS_LIB") (part "Tri-State Buffer Non-Inverting"))
    )
    (comp (ref "TSB101")
      (value "Tri-State Buffer Non-Inverting")
      (description "IC BUFF DVR TRI-ST N-INV 5TSSOP")
      (fields
        (field (name "MANUFACTURER") "NXP Semiconductors")
        (field (name "MANUFACTURER PART NUMBER") "74LVC1G125GW,125")
      )
      (libsource (lib "NORMS_LIB") (part "Tri-State Buffer Non-Inverting"))
    )
    (comp (ref "TSB102")
      (value "Tri-State Buffer Non-Inverting")
      (description "IC BUFF DVR TRI-ST N-INV 5TSSOP")
      (fields
        (field (name "MANUFACTURER") "NXP Semiconductors")
        (field (name "MANUFACTURER PART NUMBER") "74LVC1G125GW,125")
      )
      (libsource (lib "NORMS_LIB") (part "Tri-State Buffer Non-Inverting"))
    )
    (comp (ref "TSB103")
      (value "Tri-State Buffer Non-Inverting")
      (description "IC BUFF DVR TRI-ST N-INV 5TSSOP")
      (fields
        (field (name "MANUFACTURER") "NXP Semiconductors")
        (field (name "MANUFACTURER PART NUMBER") "74LVC1G125GW,125")
      )
      (libsource (lib "NORMS_LIB") (part "Tri-State Buffer Non-Inverting"))
    )
    (comp (ref "TSB104")
      (value "Tri-State Buffer Non-Inverting")
      (description "IC BUFF DVR TRI-ST N-INV 5TSSOP")
      (fields
        (field (name "MANUFACTURER") "NXP Semiconductors")
        (field (name "MANUFACTURER PART NUMBER") "74LVC1G125GW,125")
      )
      (libsource (lib "NORMS_LIB") (part "Tri-State Buffer Non-Inverting"))
    )
    (comp (ref "TSB105")
      (value "Tri-State Buffer Non-Inverting")
      (description "IC BUFF DVR TRI-ST N-INV 5TSSOP")
      (fields
        (field (name "MANUFACTURER") "NXP Semiconductors")
        (field (name "MANUFACTURER PART NUMBER") "74LVC1G125GW,125")
      )
      (libsource (lib "NORMS_LIB") (part "Tri-State Buffer Non-Inverting"))
    )
    (comp (ref "TSB106")
      (value "Tri-State Buffer Non-Inverting")
      (description "IC BUFF DVR TRI-ST N-INV 5TSSOP")
      (fields
        (field (name "MANUFACTURER") "NXP Semiconductors")
        (field (name "MANUFACTURER PART NUMBER") "74LVC1G125GW,125")
      )
      (libsource (lib "NORMS_LIB") (part "Tri-State Buffer Non-Inverting"))
    )
    (comp (ref "TSB107")
      (value "Tri-State Buffer Non-Inverting")
      (description "IC BUFF DVR TRI-ST N-INV 5TSSOP")
      (fields
        (field (name "MANUFACTURER") "NXP Semiconductors")
        (field (name "MANUFACTURER PART NUMBER") "74LVC1G125GW,125")
      )
      (libsource (lib "NORMS_LIB") (part "Tri-State Buffer Non-Inverting"))
    )
    (comp (ref "TSB108")
      (value "Tri-State Buffer Non-Inverting")
      (description "IC BUFF DVR TRI-ST N-INV 5TSSOP")
      (fields
        (field (name "MANUFACTURER") "NXP Semiconductors")
        (field (name "MANUFACTURER PART NUMBER") "74LVC1G125GW,125")
      )
      (libsource (lib "NORMS_LIB") (part "Tri-State Buffer Non-Inverting"))
    )
    (comp (ref "TSB109")
      (value "Tri-State Buffer Non-Inverting")
      (description "IC BUFF DVR TRI-ST N-INV 5TSSOP")
      (fields
        (field (name "MANUFACTURER") "NXP Semiconductors")
        (field (name "MANUFACTURER PART NUMBER") "74LVC1G125GW,125")
      )
      (libsource (lib "NORMS_LIB") (part "Tri-State Buffer Non-Inverting"))
    )
    (comp (ref "TSB110")
      (value "Tri-State Buffer Non-Inverting")
      (description "IC BUFF DVR TRI-ST N-INV 5TSSOP")
      (fields
        (field (name "MANUFACTURER") "NXP Semiconductors")
        (field (name "MANUFACTURER PART NUMBER") "74LVC1G125GW,125")
      )
      (libsource (lib "NORMS_LIB") (part "Tri-State Buffer Non-Inverting"))
    )
    (comp (ref "TSB111")
      (value "Tri-State Buffer Non-Inverting")
      (description "IC BUFF DVR TRI-ST N-INV 5TSSOP")
      (fields
        (field (name "MANUFACTURER") "NXP Semiconductors")
        (field (name "MANUFACTURER PART NUMBER") "74LVC1G125GW,125")
      )
      (libsource (lib "NORMS_LIB") (part "Tri-State Buffer Non-Inverting"))
    )
    (comp (ref "TSB112")
      (value "Tri-State Buffer Non-Inverting")
      (description "IC BUFF DVR TRI-ST N-INV 5TSSOP")
      (fields
        (field (name "MANUFACTURER") "NXP Semiconductors")
        (field (name "MANUFACTURER PART NUMBER") "74LVC1G125GW,125")
      )
      (libsource (lib "NORMS_LIB") (part "Tri-State Buffer Non-Inverting"))
    )
    (comp (ref "TSB113")
      (value "Tri-State Buffer Non-Inverting")
      (description "IC BUFF DVR TRI-ST N-INV 5TSSOP")
      (fields
        (field (name "MANUFACTURER") "NXP Semiconductors")
        (field (name "MANUFACTURER PART NUMBER") "74LVC1G125GW,125")
      )
      (libsource (lib "NORMS_LIB") (part "Tri-State Buffer Non-Inverting"))
    )
    (comp (ref "TSB114")
      (value "Tri-State Buffer Non-Inverting")
      (description "IC BUFF DVR TRI-ST N-INV 5TSSOP")
      (fields
        (field (name "MANUFACTURER") "NXP Semiconductors")
        (field (name "MANUFACTURER PART NUMBER") "74LVC1G125GW,125")
      )
      (libsource (lib "NORMS_LIB") (part "Tri-State Buffer Non-Inverting"))
    )
    (comp (ref "TSB115")
      (value "Tri-State Buffer Non-Inverting")
      (description "IC BUFF DVR TRI-ST N-INV 5TSSOP")
      (fields
        (field (name "MANUFACTURER") "NXP Semiconductors")
        (field (name "MANUFACTURER PART NUMBER") "74LVC1G125GW,125")
      )
      (libsource (lib "NORMS_LIB") (part "Tri-State Buffer Non-Inverting"))
    )
    (comp (ref "TSB116")
      (value "Tri-State Buffer Non-Inverting")
      (description "IC BUFF DVR TRI-ST N-INV 5TSSOP")
      (fields
        (field (name "MANUFACTURER") "NXP Semiconductors")
        (field (name "MANUFACTURER PART NUMBER") "74LVC1G125GW,125")
      )
      (libsource (lib "NORMS_LIB") (part "Tri-State Buffer Non-Inverting"))
    )
    (comp (ref "TSB117")
      (value "Tri-State Buffer Non-Inverting")
      (description "IC BUFF DVR TRI-ST N-INV 5TSSOP")
      (fields
        (field (name "MANUFACTURER") "NXP Semiconductors")
        (field (name "MANUFACTURER PART NUMBER") "74LVC1G125GW,125")
      )
      (libsource (lib "NORMS_LIB") (part "Tri-State Buffer Non-Inverting"))
    )
    (comp (ref "TSB118")
      (value "Tri-State Buffer Non-Inverting")
      (description "IC BUFF DVR TRI-ST N-INV 5TSSOP")
      (fields
        (field (name "MANUFACTURER") "NXP Semiconductors")
        (field (name "MANUFACTURER PART NUMBER") "74LVC1G125GW,125")
      )
      (libsource (lib "NORMS_LIB") (part "Tri-State Buffer Non-Inverting"))
    )
    (comp (ref "TSB119")
      (value "Tri-State Buffer Non-Inverting")
      (description "IC BUFF DVR TRI-ST N-INV 5TSSOP")
      (fields
        (field (name "MANUFACTURER") "NXP Semiconductors")
        (field (name "MANUFACTURER PART NUMBER") "74LVC1G125GW,125")
      )
      (libsource (lib "NORMS_LIB") (part "Tri-State Buffer Non-Inverting"))
    )
    (comp (ref "TSB120")
      (value "Tri-State Buffer Non-Inverting")
      (description "IC BUFF DVR TRI-ST N-INV 5TSSOP")
      (fields
        (field (name "MANUFACTURER") "NXP Semiconductors")
        (field (name "MANUFACTURER PART NUMBER") "74LVC1G125GW,125")
      )
      (libsource (lib "NORMS_LIB") (part "Tri-State Buffer Non-Inverting"))
    )
    (comp (ref "TSB121")
      (value "Tri-State Buffer Non-Inverting")
      (description "IC BUFF DVR TRI-ST N-INV 5TSSOP")
      (fields
        (field (name "MANUFACTURER") "NXP Semiconductors")
        (field (name "MANUFACTURER PART NUMBER") "74LVC1G125GW,125")
      )
      (libsource (lib "NORMS_LIB") (part "Tri-State Buffer Non-Inverting"))
    )
    (comp (ref "TSB122")
      (value "Tri-State Buffer Non-Inverting")
      (description "IC BUFF DVR TRI-ST N-INV 5TSSOP")
      (fields
        (field (name "MANUFACTURER") "NXP Semiconductors")
        (field (name "MANUFACTURER PART NUMBER") "74LVC1G125GW,125")
      )
      (libsource (lib "NORMS_LIB") (part "Tri-State Buffer Non-Inverting"))
    )
    (comp (ref "TSB123")
      (value "Tri-State Buffer Non-Inverting")
      (description "IC BUFF DVR TRI-ST N-INV 5TSSOP")
      (fields
        (field (name "MANUFACTURER") "NXP Semiconductors")
        (field (name "MANUFACTURER PART NUMBER") "74LVC1G125GW,125")
      )
      (libsource (lib "NORMS_LIB") (part "Tri-State Buffer Non-Inverting"))
    )
    (comp (ref "TSB124")
      (value "Tri-State Buffer Non-Inverting")
      (description "IC BUFF DVR TRI-ST N-INV 5TSSOP")
      (fields
        (field (name "MANUFACTURER") "NXP Semiconductors")
        (field (name "MANUFACTURER PART NUMBER") "74LVC1G125GW,125")
      )
      (libsource (lib "NORMS_LIB") (part "Tri-State Buffer Non-Inverting"))
    )
    (comp (ref "TSB125")
      (value "Tri-State Buffer Non-Inverting")
      (description "IC BUFF DVR TRI-ST N-INV 5TSSOP")
      (fields
        (field (name "MANUFACTURER") "NXP Semiconductors")
        (field (name "MANUFACTURER PART NUMBER") "74LVC1G125GW,125")
      )
      (libsource (lib "NORMS_LIB") (part "Tri-State Buffer Non-Inverting"))
    )
    (comp (ref "TSB126")
      (value "Tri-State Buffer Non-Inverting")
      (description "IC BUFF DVR TRI-ST N-INV 5TSSOP")
      (fields
        (field (name "MANUFACTURER") "NXP Semiconductors")
        (field (name "MANUFACTURER PART NUMBER") "74LVC1G125GW,125")
      )
      (libsource (lib "NORMS_LIB") (part "Tri-State Buffer Non-Inverting"))
    )
    (comp (ref "TSB127")
      (value "Tri-State Buffer Non-Inverting")
      (description "IC BUFF DVR TRI-ST N-INV 5TSSOP")
      (fields
        (field (name "MANUFACTURER") "NXP Semiconductors")
        (field (name "MANUFACTURER PART NUMBER") "74LVC1G125GW,125")
      )
      (libsource (lib "NORMS_LIB") (part "Tri-State Buffer Non-Inverting"))
    )
    (comp (ref "TSB128")
      (value "Tri-State Buffer Non-Inverting")
      (description "IC BUFF DVR TRI-ST N-INV 5TSSOP")
      (fields
        (field (name "MANUFACTURER") "NXP Semiconductors")
        (field (name "MANUFACTURER PART NUMBER") "74LVC1G125GW,125")
      )
      (libsource (lib "NORMS_LIB") (part "Tri-State Buffer Non-Inverting"))
    )
  )
  (nets
    (net (code "3") (name "/A0") (class "Default")
      (node (ref "TSB1") (pin "2") (pinfunction "A_2") (pintype "passive"))
    )
    (net (code "4") (name "/A1") (class "Default")
      (node (ref "TSB8") (pin "2") (pinfunction "A_2") (pintype "passive"))
    )
    (net (code "5") (name "/A2") (class "Default")
      (node (ref "TSB15") (pin "2") (pinfunction "A_2") (pintype "passive"))
    )
    (net (code "6") (name "/A3") (class "Default")
      (node (ref "TSB22") (pin "2") (pinfunction "A_2") (pintype "passive"))
    )
    (net (code "7") (name "/A4") (class "Default")
      (node (ref "TSB29") (pin "2") (pinfunction "A_2") (pintype "passive"))
    )
    (net (code "8") (name "/A5") (class "Default")
      (node (ref "TSB36") (pin "2") (pinfunction "A_2") (pintype "passive"))
    )
    (net (code "9") (name "/A6") (class "Default")
      (node (ref "TSB43") (pin "2") (pinfunction "A_2") (pintype "passive"))
    )
    (net (code "10") (name "/A7") (class "Default")
      (node (ref "TSB50") (pin "2") (pinfunction "A_2") (pintype "passive"))
    )
    (net (code "11") (name "/A8") (class "Default")
      (node (ref "TSB57") (pin "2") (pinfunction "A_2") (pintype "passive"))
    )
    (net (code "12") (name "/A9") (class "Default")
      (node (ref "TSB64") (pin "2") (pinfunction "A_2") (pintype "passive"))
    )
    (net (code "13") (name "/A10") (class "Default")
      (node (ref "TSB71") (pin "2") (pinfunction "A_2") (pintype "passive"))
    )
    (net (code "14") (name "/A11") (class "Default")
      (node (ref "TSB78") (pin "2") (pinfunction "A_2") (pintype "passive"))
    )
    (net (code "15") (name "/A12") (class "Default")
      (node (ref "TSB85") (pin "2") (pinfunction "A_2") (pintype "passive"))
    )
    (net (code "16") (name "/A13") (class "Default")
      (node (ref "TSB92") (pin "2") (pinfunction "A_2") (pintype "passive"))
    )
    (net (code "17") (name "/A14") (class "Default")
      (node (ref "TSB99") (pin "2") (pinfunction "A_2") (pintype "passive"))
    )
    (net (code "18") (name "/A15") (class "Default")
      (node (ref "TSB106") (pin "2") (pinfunction "A_2") (pintype "passive"))
    )
    (net (code "19") (name "/A16") (class "Default")
      (node (ref "TSB113") (pin "2") (pinfunction "A_2") (pintype "passive"))
    )
    (net (code "20") (name "/A17") (class "Default")
      (node (ref "TSB120") (pin "2") (pinfunction "A_2") (pintype "passive"))
    )
    (net (code "21") (name "/A18") (class "Default")
      (node (ref "TSB2") (pin "2") (pinfunction "A_2") (pintype "passive"))
    )
    (net (code "22") (name "/A19") (class "Default")
      (node (ref "TSB9") (pin "2") (pinfunction "A_2") (pintype "passive"))
    )
    (net (code "23") (name "/A20") (class "Default")
      (node (ref "TSB16") (pin "2") (pinfunction "A_2") (pintype "passive"))
    )
    (net (code "24") (name "/A21") (class "Default")
      (node (ref "TSB23") (pin "2") (pinfunction "A_2") (pintype "passive"))
    )
    (net (code "25") (name "/A22") (class "Default")
      (node (ref "TSB30") (pin "2") (pinfunction "A_2") (pintype "passive"))
    )
    (net (code "26") (name "/A23") (class "Default")
      (node (ref "TSB37") (pin "2") (pinfunction "A_2") (pintype "passive"))
    )
    (net (code "27") (name "/A24") (class "Default")
      (node (ref "TSB44") (pin "2") (pinfunction "A_2") (pintype "passive"))
    )
    (net (code "28") (name "/A25") (class "Default")
      (node (ref "TSB51") (pin "2") (pinfunction "A_2") (pintype "passive"))
    )
    (net (code "29") (name "/A26") (class "Default")
      (node (ref "TSB58") (pin "2") (pinfunction "A_2") (pintype "passive"))
    )
    (net (code "30") (name "/A27") (class "Default")
      (node (ref "TSB65") (pin "2") (pinfunction "A_2") (pintype "passive"))
    )
    (net (code "31") (name "/A28") (class "Default")
      (node (ref "TSB72") (pin "2") (pinfunction "A_2") (pintype "passive"))
    )
    (net (code "32") (name "/A29") (class "Default")
      (node (ref "TSB79") (pin "2") (pinfunction "A_2") (pintype "passive"))
    )
    (net (code "33") (name "/A30") (class "Default")
      (node (ref "TSB86") (pin "2") (pinfunction "A_2") (pintype "passive"))
    )
    (net (code "34") (name "/A31") (class "Default")
      (node (ref "TSB93") (pin "2") (pinfunction "A_2") (pintype "passive"))
    )
    (net (code "35") (name "/A32") (class "Default")
      (node (ref "TSB100") (pin "2") (pinfunction "A_2") (pintype "passive"))
    )
    (net (code "36") (name "/A33") (class "Default")
      (node (ref "TSB107") (pin "2") (pinfunction "A_2") (pintype "passive"))
    )
    (net (code "37") (name "/A34") (class "Default")
      (node (ref "TSB114") (pin "2") (pinfunction "A_2") (pintype "passive"))
    )
    (net (code "38") (name "/A35") (class "Default")
      (node (ref "TSB121") (pin "2") (pinfunction "A_2") (pintype "passive"))
    )
    (net (code "39") (name "/A36") (class "Default")
      (node (ref "TSB3") (pin "2") (pinfunction "A_2") (pintype "passive"))
    )
    (net (code "40") (name "/A37") (class "Default")
      (node (ref "TSB10") (pin "2") (pinfunction "A_2") (pintype "passive"))
    )
    (net (code "41") (name "/A38") (class "Default")
      (node (ref "TSB17") (pin "2") (pinfunction "A_2") (pintype "passive"))
    )
    (net (code "42") (name "/A39") (class "Default")
      (node (ref "TSB24") (pin "2") (pinfunction "A_2") (pintype "passive"))
    )
    (net (code "43") (name "/A40") (class "Default")
      (node (ref "TSB31") (pin "2") (pinfunction "A_2") (pintype "passive"))
    )
    (net (code "44") (name "/A41") (class "Default")
      (node (ref "TSB38") (pin "2") (pinfunction "A_2") (pintype "passive"))
    )
    (net (code "45") (name "/A42") (class "Default")
      (node (ref "TSB45") (pin "2") (pinfunction "A_2") (pintype "passive"))
    )
    (net (code "46") (name "/A43") (class "Default")
      (node (ref "TSB52") (pin "2") (pinfunction "A_2") (pintype "passive"))
    )
    (net (code "47") (name "/A44") (class "Default")
      (node (ref "TSB59") (pin "2") (pinfunction "A_2") (pintype "passive"))
    )
    (net (code "48") (name "/A45") (class "Default")
      (node (ref "TSB66") (pin "2") (pinfunction "A_2") (pintype "passive"))
    )
    (net (code "49") (name "/A46") (class "Default")
      (node (ref "TSB73") (pin "2") (pinfunction "A_2") (pintype "passive"))
    )
    (net (code "50") (name "/A47") (class "Default")
      (node (ref "TSB80") (pin "2") (pinfunction "A_2") (pintype "passive"))
    )
    (net (code "51") (name "/A48") (class "Default")
      (node (ref "TSB87") (pin "2") (pinfunction "A_2") (pintype "passive"))
    )
    (net (code "52") (name "/A49") (class "Default")
      (node (ref "TSB94") (pin "2") (pinfunction "A_2") (pintype "passive"))
    )
    (net (code "53") (name "/A50") (class "Default")
      (node (ref "TSB101") (pin "2") (pinfunction "A_2") (pintype "passive"))
    )
    (net (code "54") (name "/A51") (class "Default")
      (node (ref "TSB108") (pin "2") (pinfunction "A_2") (pintype "passive"))
    )
    (net (code "55") (name "/A52") (class "Default")
      (node (ref "TSB115") (pin "2") (pinfunction "A_2") (pintype "passive"))
    )
    (net (code "56") (name "/A53") (class "Default")
      (node (ref "TSB122") (pin "2") (pinfunction "A_2") (pintype "passive"))
    )
    (net (code "57") (name "/A54") (class "Default")
      (node (ref "TSB4") (pin "2") (pinfunction "A_2") (pintype "passive"))
    )
    (net (code "58") (name "/A55") (class "Default")
      (node (ref "TSB11") (pin "2") (pinfunction "A_2") (pintype "passive"))
    )
    (net (code "59") (name "/A56") (class "Default")
      (node (ref "TSB18") (pin "2") (pinfunction "A_2") (pintype "passive"))
    )
    (net (code "60") (name "/A57") (class "Default")
      (node (ref "TSB25") (pin "2") (pinfunction "A_2") (pintype "passive"))
    )
    (net (code "61") (name "/A58") (class "Default")
      (node (ref "TSB32") (pin "2") (pinfunction "A_2") (pintype "passive"))
    )
    (net (code "62") (name "/A59") (class "Default")
      (node (ref "TSB39") (pin "2") (pinfunction "A_2") (pintype "passive"))
    )
    (net (code "63") (name "/A60") (class "Default")
      (node (ref "TSB46") (pin "2") (pinfunction "A_2") (pintype "passive"))
    )
    (net (code "64") (name "/A61") (class "Default")
      (node (ref "TSB53") (pin "2") (pinfunction "A_2") (pintype "passive"))
    )
    (net (code "65") (name "/A62") (class "Default")
      (node (ref "TSB60") (pin "2") (pinfunction "A_2") (pintype "passive"))
    )
    (net (code "66") (name "/A63") (class "Default")
      (node (ref "TSB67") (pin "2") (pinfunction "A_2") (pintype "passive"))
    )
    (net (code "67") (name "/A64") (class "Default")
      (node (ref "TSB74") (pin "2") (pinfunction "A_2") (pintype "passive"))
    )
    (net (code "68") (name "/A65") (class "Default")
      (node (ref "TSB81") (pin "2") (pinfunction "A_2") (pintype "passive"))
    )
    (net (code "69") (name "/A66") (class "Default")
      (node (ref "TSB88") (pin "2") (pinfunction "A_2") (pintype "passive"))
    )
    (net (code "70") (name "/A67") (class "Default")
      (node (ref "TSB95") (pin "2") (pinfunction "A_2") (pintype "passive"))
    )
    (net (code "71") (name "/A68") (class "Default")
      (node (ref "TSB102") (pin "2") (pinfunction "A_2") (pintype "passive"))
    )
    (net (code "72") (name "/A69") (class "Default")
      (node (ref "TSB109") (pin "2") (pinfunction "A_2") (pintype "passive"))
    )
    (net (code "73") (name "/A70") (class "Default")
      (node (ref "TSB116") (pin "2") (pinfunction "A_2") (pintype "passive"))
    )
    (net (code "74") (name "/A71") (class "Default")
      (node (ref "TSB123") (pin "2") (pinfunction "A_2") (pintype "passive"))
    )
    (net (code "75") (name "/A72") (class "Default")
      (node (ref "TSB5") (pin "2") (pinfunction "A_2") (pintype "passive"))
    )
    (net (code "76") (name "/A73") (class "Default")
      (node (ref "TSB12") (pin "2") (pinfunction "A_2") (pintype "passive"))
    )
    (net (code "77") (name "/A74") (class "Default")
      (node (ref "TSB19") (pin "2") (pinfunction "A_2") (pintype "passive"))
    )
    (net (code "78") (name "/A75") (class "Default")
      (node (ref "TSB26") (pin "2") (pinfunction "A_2") (pintype "passive"))
    )
    (net (code "79") (name "/A76") (class "Default")
      (node (ref "TSB33") (pin "2") (pinfunction "A_2") (pintype "passive"))
    )
    (net (code "80") (name "/A77") (class "Default")
      (node (ref "TSB40") (pin "2") (pinfunction "A_2") (pintype "passive"))
    )
    (net (code "81") (name "/A78") (class "Default")
      (node (ref "TSB47") (pin "2") (pinfunction "A_2") (pintype "passive"))
    )
    (net (code "82") (name "/A79") (class "Default")
      (node (ref "TSB54") (pin "2") (pinfunction "A_2") (pintype "passive"))
    )
    (net (code "83") (name "/A80") (class "Default")
      (node (ref "TSB61") (pin "2") (pinfunction "A_2") (pintype "passive"))
    )
    (net (code "84") (name "/A81") (class "Default")
      (node (ref "TSB68") (pin "2") (pinfunction "A_2") (pintype "passive"))
    )
    (net (code "85") (name "/A82") (class "Default")
      (node (ref "TSB75") (pin "2") (pinfunction "A_2") (pintype "passive"))
    )
    (net (code "86") (name "/A83") (class "Default")
      (node (ref "TSB82") (pin "2") (pinfunction "A_2") (pintype "passive"))
    )
    (net (code "87") (name "/A84") (class "Default")
      (node (ref "TSB89") (pin "2") (pinfunction "A_2") (pintype "passive"))
    )
    (net (code "88") (name "/A85") (class "Default")
      (node (ref "TSB96") (pin "2") (pinfunction "A_2") (pintype "passive"))
    )
    (net (code "89") (name "/A86") (class "Default")
      (node (ref "TSB103") (pin "2") (pinfunction "A_2") (pintype "passive"))
    )
    (net (code "90") (name "/A87") (class "Default")
      (node (ref "TSB110") (pin "2") (pinfunction "A_2") (pintype "passive"))
    )
    (net (code "91") (name "/A88") (class "Default")
      (node (ref "TSB117") (pin "2") (pinfunction "A_2") (pintype "passive"))
    )
    (net (code "92") (name "/A89") (class "Default")
      (node (ref "TSB124") (pin "2") (pinfunction "A_2") (pintype "passive"))
    )
    (net (code "93") (name "/A90") (class "Default")
      (node (ref "TSB6") (pin "2") (pinfunction "A_2") (pintype "passive"))
    )
    (net (code "94") (name "/A91") (class "Default")
      (node (ref "TSB13") (pin "2") (pinfunction "A_2") (pintype "passive"))
    )
    (net (code "95") (name "/A92") (class "Default")
      (node (ref "TSB20") (pin "2") (pinfunction "A_2") (pintype "passive"))
    )
    (net (code "96") (name "/A93") (class "Default")
      (node (ref "TSB27") (pin "2") (pinfunction "A_2") (pintype "passive"))
    )
    (net (code "97") (name "/A94") (class "Default")
      (node (ref "TSB34") (pin "2") (pinfunction "A_2") (pintype "passive"))
    )
    (net (code "98") (name "/A95") (class "Default")
      (node (ref "TSB41") (pin "2") (pinfunction "A_2") (pintype "passive"))
    )
    (net (code "99") (name "/A96") (class "Default")
      (node (ref "TSB48") (pin "2") (pinfunction "A_2") (pintype "passive"))
    )
    (net (code "100") (name "/A97") (class "Default")
      (node (ref "TSB55") (pin "2") (pinfunction "A_2") (pintype "passive"))
    )
    (net (code "101") (name "/A98") (class "Default")
      (node (ref "TSB62") (pin "2") (pinfunction "A_2") (pintype "passive"))
    )
    (net (code "102") (name "/A99") (class "Default")
      (node (ref "TSB69") (pin "2") (pinfunction "A_2") (pintype "passive"))
    )
    (net (code "103") (name "/A100") (class "Default")
      (node (ref "TSB76") (pin "2") (pinfunction "A_2") (pintype "passive"))
    )
    (net (code "104") (name "/A101") (class "Default")
      (node (ref "TSB83") (pin "2") (pinfunction "A_2") (pintype "passive"))
    )
    (net (code "105") (name "/A102") (class "Default")
      (node (ref "TSB90") (pin "2") (pinfunction "A_2") (pintype "passive"))
    )
    (net (code "106") (name "/A103") (class "Default")
      (node (ref "TSB97") (pin "2") (pinfunction "A_2") (pintype "passive"))
    )
    (net (code "107") (name "/A104") (class "Default")
      (node (ref "TSB104") (pin "2") (pinfunction "A_2") (pintype "passive"))
    )
    (net (code "108") (name "/A105") (class "Default")
      (node (ref "TSB111") (pin "2") (pinfunction "A_2") (pintype "passive"))
    )
    (net (code "109") (name "/A106") (class "Default")
      (node (ref "TSB118") (pin "2") (pinfunction "A_2") (pintype "passive"))
    )
    (net (code "110") (name "/A107") (class "Default")
      (node (ref "TSB125") (pin "2") (pinfunction "A_2") (pintype "passive"))
    )
    (net (code "111") (name "/A108") (class "Default")
      (node (ref "TSB7") (pin "2") (pinfunction "A_2") (pintype "passive"))
    )
    (net (code "112") (name "/A109") (class "Default")
      (node (ref "TSB14") (pin "2") (pinfunction "A_2") (pintype "passive"))
    )
    (net (code "113") (name "/A110") (class "Default")
      (node (ref "TSB21") (pin "2") (pinfunction "A_2") (pintype "passive"))
    )
    (net (code "114") (name "/A111") (class "Default")
      (node (ref "TSB28") (pin "2") (pinfunction "A_2") (pintype "passive"))
    )
    (net (code "115") (name "/A112") (class "Default")
      (node (ref "TSB35") (pin "2") (pinfunction "A_2") (pintype "passive"))
    )
    (net (code "116") (name "/A113") (class "Default")
      (node (ref "TSB42") (pin "2") (pinfunction "A_2") (pintype "passive"))
    )
    (net (code "117") (name "/A114") (class "Default")
      (node (ref "TSB49") (pin "2") (pinfunction "A_2") (pintype "passive"))
    )
    (net (code "118") (name "/A115") (class "Default")
      (node (ref "TSB56") (pin "2") (pinfunction "A_2") (pintype "passive"))
    )
    (net (code "119") (name "/A116") (class "Default")
      (node (ref "TSB63") (pin "2") (pinfunction "A_2") (pintype "passive"))
    )
    (net (code "120") (name "/A117") (class "Default")
      (node (ref "TSB70") (pin "2") (pinfunction "A_2") (pintype "passive"))
    )
    (net (code "121") (name "/A118") (class "Default")
      (node (ref "TSB77") (pin "2") (pinfunction "A_2") (pintype "passive"))
    )
    (net (code "122") (name "/A119") (class "Default")
      (node (ref "TSB84") (pin "2") (pinfunction "A_2") (pintype "passive"))
    )
    (net (code "123") (name "/A120") (class "Default")
      (node (ref "TSB91") (pin "2") (pinfunction "A_2") (pintype "passive"))
    )
    (net (code "124") (name "/A121") (class "Default")
      (node (ref "TSB98") (pin "2") (pinfunction "A_2") (pintype "passive"))
    )
    (net (code "125") (name "/A122") (class "Default")
      (node (ref "TSB105") (pin "2") (pinfunction "A_2") (pintype "passive"))
    )
    (net (code "126") (name "/A123") (class "Default")
      (node (ref "TSB112") (pin "2") (pinfunction "A_2") (pintype "passive"))
    )
    (net (code "127") (name "/A124") (class "Default")
      (node (ref "TSB119") (pin "2") (pinfunction "A_2") (pintype "passive"))
    )
    (net (code "128") (name "/A125") (class "Default")
      (node (ref "TSB126") (pin "2") (pinfunction "A_2") (pintype "passive"))
    )
    (net (code "137") (name "/GND") (class "Default")
      (node (ref "TSB1") (pin "3") (pinfunction "GND_3") (pintype "passive"))
      (node (ref "TSB10") (pin "3") (pinfunction "GND_3") (pintype "passive"))
      (node (ref "TSB100") (pin "3") (pinfunction "GND_3") (pintype "passive"))
      (node (ref "TSB101") (pin "3") (pinfunction "GND_3") (pintype "passive"))
      (node (ref "TSB102") (pin "3") (pinfunction "GND_3") (pintype "passive"))
      (node (ref "TSB103") (pin "3") (pinfunction "GND_3") (pintype "passive"))
      (node (ref "TSB104") (pin "3") (pinfunction "GND_3") (pintype "passive"))
      (node (ref "TSB105") (pin "3") (pinfunction "GND_3") (pintype "passive"))
      (node (ref "TSB106") (pin "3") (pinfunction "GND_3") (pintype "passive"))
      (node (ref "TSB107") (pin "3") (pinfunction "GND_3") (pintype "passive"))
      (node (ref "TSB108") (pin "3") (pinfunction "GND_3") (pintype "passive"))
      (node (ref "TSB109") (pin "3") (pinfunction "GND_3") (pintype "passive"))
      (node (ref "TSB11") (pin "3") (pinfunction "GND_3") (pintype "passive"))
      (node (ref "TSB110") (pin "3") (pinfunction "GND_3") (pintype "passive"))
      (node (ref "TSB111") (pin "3") (pinfunction "GND_3") (pintype "passive"))
      (node (ref "TSB112") (pin "3") (pinfunction "GND_3") (pintype "passive"))
      (node (ref "TSB113") (pin "3") (pinfunction "GND_3") (pintype "passive"))
      (node (ref "TSB114") (pin "3") (pinfunction "GND_3") (pintype "passive"))
      (node (ref "TSB115") (pin "3") (pinfunction "GND_3") (pintype "passive"))
      (node (ref "TSB116") (pin "3") (pinfunction "GND_3") (pintype "passive"))
      (node (ref "TSB117") (pin "3") (pinfunction "GND_3") (pintype "passive"))
      (node (ref "TSB118") (pin "3") (pinfunction "GND_3") (pintype "passive"))
      (node (ref "TSB119") (pin "3") (pinfunction "GND_3") (pintype "passive"))
      (node (ref "TSB12") (pin "3") (pinfunction "GND_3") (pintype "passive"))
      (node (ref "TSB120") (pin "3") (pinfunction "GND_3") (pintype "passive"))
      (node (ref "TSB121") (pin "3") (pinfunction "GND_3") (pintype "passive"))
      (node (ref "TSB123") (pin "3") (pinfunction "GND_3") (pintype "passive"))
      (node (ref "TSB124") (pin "3") (pinfunction "GND_3") (pintype "passive"))
      (node (ref "TSB125") (pin "3") (pinfunction "GND_3") (pintype "passive"))
      (node (ref "TSB126") (pin "3") (pinfunction "GND_3") (pintype "passive"))
      (node (ref "TSB127") (pin "2") (pinfunction "A_2") (pintype "passive"))
      (node (ref "TSB127") (pin "3") (pinfunction "GND_3") (pintype "passive"))
      (node (ref "TSB128") (pin "2") (pinfunction "A_2") (pintype "passive"))
      (node (ref "TSB128") (pin "3") (pinfunction "GND_3") (pintype "passive"))
      (node (ref "TSB13") (pin "3") (pinfunction "GND_3") (pintype "passive"))
      (node (ref "TSB14") (pin "3") (pinfunction "GND_3") (pintype "passive"))
      (node (ref "TSB15") (pin "3") (pinfunction "GND_3") (pintype "passive"))
      (node (ref "TSB16") (pin "3") (pinfunction "GND_3") (pintype "passive"))
      (node (ref "TSB17") (pin "3") (pinfunction "GND_3") (pintype "passive"))
      (node (ref "TSB18") (pin "3") (pinfunction "GND_3") (pintype "passive"))
      (node (ref "TSB19") (pin "3") (pinfunction "GND_3") (pintype "passive"))
      (node (ref "TSB2") (pin "3") (pinfunction "GND_3") (pintype "passive"))
      (node (ref "TSB20") (pin "3") (pinfunction "GND_3") (pintype "passive"))
      (node (ref "TSB21") (pin "3") (pinfunction "GND_3") (pintype "passive"))
      (node (ref "TSB22") (pin "3") (pinfunction "GND_3") (pintype "passive"))
      (node (ref "TSB23") (pin "3") (pinfunction "GND_3") (pintype "passive"))
      (node (ref "TSB24") (pin "3") (pinfunction "GND_3") (pintype "passive"))
      (node (ref "TSB25") (pin "3") (pinfunction "GND_3") (pintype "passive"))
      (node (ref "TSB26") (pin "3") (pinfunction "GND_3") (pintype "passive"))
      (node (ref "TSB27") (pin "3") (pinfunction "GND_3") (pintype "passive"))
      (node (ref "TSB28") (pin "3") (pinfunction "GND_3") (pintype "passive"))
      (node (ref "TSB29") (pin "3") (pinfunction "GND_3") (pintype "passive"))
      (node (ref "TSB3") (pin "3") (pinfunction "GND_3") (pintype "passive"))
      (node (ref "TSB30") (pin "3") (pinfunction "GND_3") (pintype "passive"))
      (node (ref "TSB31") (pin "3") (pinfunction "GND_3") (pintype "passive"))
      (node (ref "TSB32") (pin "3") (pinfunction "GND_3") (pintype "passive"))
      (node (ref "TSB33") (pin "3") (pinfunction "GND_3") (pintype "passive"))
      (node (ref "TSB34") (pin "3") (pinfunction "GND_3") (pintype "passive"))
      (node (ref "TSB35") (pin "3") (pinfunction "GND_3") (pintype "passive"))
      (node (ref "TSB36") (pin "3") (pinfunction "GND_3") (pintype "passive"))
      (node (ref "TSB37") (pin "3") (pinfunction "GND_3") (pintype "passive"))
      (node (ref "TSB38") (pin "3") (pinfunction "GND_3") (pintype "passive"))
      (node (ref "TSB39") (pin "3") (pinfunction "GND_3") (pintype "passive"))
      (node (ref "TSB4") (pin "3") (pinfunction "GND_3") (pintype "passive"))
      (node (ref "TSB40") (pin "3") (pinfunction "GND_3") (pintype "passive"))
      (node (ref "TSB41") (pin "3") (pinfunction "GND_3") (pintype "passive"))
      (node (ref "TSB42") (pin "3") (pinfunction "GND_3") (pintype "passive"))
      (node (ref "TSB43") (pin "3") (pinfunction "GND_3") (pintype "passive"))
      (node (ref "TSB44") (pin "3") (pinfunction "GND_3") (pintype "passive"))
      (node (ref "TSB45") (pin "3") (pinfunction "GND_3") (pintype "passive"))
      (node (ref "TSB46") (pin "3") (pinfunction "GND_3") (pintype "passive"))
      (node (ref "TSB47") (pin "3") (pinfunction "GND_3") (pintype "passive"))
      (node (ref "TSB48") (pin "3") (pinfunction "GND_3") (pintype "passive"))
      (node (ref "TSB49") (pin "3") (pinfunction "GND_3") (pintype "passive"))
      (node (ref "TSB5") (pin "3") (pinfunction "GND_3") (pintype "passive"))
      (node (ref "TSB50") (pin "3") (pinfunction "GND_3") (pintype "passive"))
      (node (ref "TSB51") (pin "3") (pinfunction "GND_3") (pintype "passive"))
      (node (ref "TSB52") (pin "3") (pinfunction "GND_3") (pintype "passive"))
      (node (ref "TSB53") (pin "3") (pinfunction "GND_3") (pintype "passive"))
      (node (ref "TSB54") (pin "3") (pinfunction "GND_3") (pintype "passive"))
      (node (ref "TSB55") (pin "3") (pinfunction "GND_3") (pintype "passive"))
      (node (ref "TSB56") (pin "3") (pinfunction "GND_3") (pintype "passive"))
      (node (ref "TSB57") (pin "3") (pinfunction "GND_3") (pintype "passive"))
      (node (ref "TSB58") (pin "3") (pinfunction "GND_3") (pintype "passive"))
      (node (ref "TSB59") (pin "3") (pinfunction "GND_3") (pintype "passive"))
      (node (ref "TSB6") (pin "3") (pinfunction "GND_3") (pintype "passive"))
      (node (ref "TSB60") (pin "3") (pinfunction "GND_3") (pintype "passive"))
      (node (ref "TSB61") (pin "3") (pinfunction "GND_3") (pintype "passive"))
      (node (ref "TSB62") (pin "3") (pinfunction "GND_3") (pintype "passive"))
      (node (ref "TSB63") (pin "3") (pinfunction "GND_3") (pintype "passive"))
      (node (ref "TSB64") (pin "3") (pinfunction "GND_3") (pintype "passive"))
      (node (ref "TSB65") (pin "3") (pinfunction "GND_3") (pintype "passive"))
      (node (ref "TSB66") (pin "3") (pinfunction "GND_3") (pintype "passive"))
      (node (ref "TSB67") (pin "3") (pinfunction "GND_3") (pintype "passive"))
      (node (ref "TSB68") (pin "3") (pinfunction "GND_3") (pintype "passive"))
      (node (ref "TSB69") (pin "3") (pinfunction "GND_3") (pintype "passive"))
      (node (ref "TSB7") (pin "3") (pinfunction "GND_3") (pintype "passive"))
      (node (ref "TSB70") (pin "3") (pinfunction "GND_3") (pintype "passive"))
      (node (ref "TSB71") (pin "3") (pinfunction "GND_3") (pintype "passive"))
      (node (ref "TSB72") (pin "3") (pinfunction "GND_3") (pintype "passive"))
      (node (ref "TSB73") (pin "3") (pinfunction "GND_3") (pintype "passive"))
      (node (ref "TSB74") (pin "3") (pinfunction "GND_3") (pintype "passive"))
      (node (ref "TSB75") (pin "3") (pinfunction "GND_3") (pintype "passive"))
      (node (ref "TSB76") (pin "3") (pinfunction "GND_3") (pintype "passive"))
      (node (ref "TSB77") (pin "3") (pinfunction "GND_3") (pintype "passive"))
      (node (ref "TSB78") (pin "3") (pinfunction "GND_3") (pintype "passive"))
      (node (ref "TSB79") (pin "3") (pinfunction "GND_3") (pintype "passive"))
      (node (ref "TSB8") (pin "3") (pinfunction "GND_3") (pintype "passive"))
      (node (ref "TSB80") (pin "3") (pinfunction "GND_3") (pintype "passive"))
      (node (ref "TSB81") (pin "3") (pinfunction "GND_3") (pintype "passive"))
      (node (ref "TSB82") (pin "3") (pinfunction "GND_3") (pintype "passive"))
      (node (ref "TSB83") (pin "3") (pinfunction "GND_3") (pintype "passive"))
      (node (ref "TSB84") (pin "3") (pinfunction "GND_3") (pintype "passive"))
      (node (ref "TSB85") (pin "3") (pinfunction "GND_3") (pintype "passive"))
      (node (ref "TSB86") (pin "3") (pinfunction "GND_3") (pintype "passive"))
      (node (ref "TSB87") (pin "3") (pinfunction "GND_3") (pintype "passive"))
      (node (ref "TSB88") (pin "3") (pinfunction "GND_3") (pintype "passive"))
      (node (ref "TSB89") (pin "3") (pinfunction "GND_3") (pintype "passive"))
      (node (ref "TSB9") (pin "3") (pinfunction "GND_3") (pintype "passive"))
      (node (ref "TSB90") (pin "3") (pinfunction "GND_3") (pintype "passive"))
      (node (ref "TSB91") (pin "3") (pinfunction "GND_3") (pintype "passive"))
      (node (ref "TSB92") (pin "3") (pinfunction "GND_3") (pintype "passive"))
      (node (ref "TSB93") (pin "3") (pinfunction "GND_3") (pintype "passive"))
      (node (ref "TSB94") (pin "3") (pinfunction "GND_3") (pintype "passive"))
      (node (ref "TSB95") (pin "3") (pinfunction "GND_3") (pintype "passive"))
      (node (ref "TSB96") (pin "3") (pinfunction "GND_3") (pintype "passive"))
      (node (ref "TSB97") (pin "3") (pinfunction "GND_3") (pintype "passive"))
      (node (ref "TSB98") (pin "3") (pinfunction "GND_3") (pintype "passive"))
      (node (ref "TSB99") (pin "3") (pinfunction "GND_3") (pintype "passive"))
    )
    (net (code "138") (name "/VCC") (class "Default")
      (node (ref "TSB1") (pin "5") (pinfunction "Vcc_5") (pintype "passive"))
      (node (ref "TSB10") (pin "5") (pinfunction "Vcc_5") (pintype "passive"))
      (node (ref "TSB100") (pin "5") (pinfunction "Vcc_5") (pintype "passive"))
      (node (ref "TSB101") (pin "5") (pinfunction "Vcc_5") (pintype "passive"))
      (node (ref "TSB102") (pin "5") (pinfunction "Vcc_5") (pintype "passive"))
      (node (ref "TSB103") (pin "5") (pinfunction "Vcc_5") (pintype "passive"))
      (node (ref "TSB104") (pin "5") (pinfunction "Vcc_5") (pintype "passive"))
      (node (ref "TSB105") (pin "5") (pinfunction "Vcc_5") (pintype "passive"))
      (node (ref "TSB106") (pin "5") (pinfunction "Vcc_5") (pintype "passive"))
      (node (ref "TSB107") (pin "5") (pinfunction "Vcc_5") (pintype "passive"))
      (node (ref "TSB108") (pin "5") (pinfunction "Vcc_5") (pintype "passive"))
      (node (ref "TSB109") (pin "5") (pinfunction "Vcc_5") (pintype "passive"))
      (node (ref "TSB11") (pin "5") (pinfunction "Vcc_5") (pintype "passive"))
      (node (ref "TSB110") (pin "5") (pinfunction "Vcc_5") (pintype "passive"))
      (node (ref "TSB111") (pin "5") (pinfunction "Vcc_5") (pintype "passive"))
      (node (ref "TSB112") (pin "5") (pinfunction "Vcc_5") (pintype "passive"))
      (node (ref "TSB113") (pin "5") (pinfunction "Vcc_5") (pintype "passive"))
      (node (ref "TSB114") (pin "5") (pinfunction "Vcc_5") (pintype "passive"))
      (node (ref "TSB115") (pin "5") (pinfunction "Vcc_5") (pintype "passive"))
      (node (ref "TSB116") (pin "5") (pinfunction "Vcc_5") (pintype "passive"))
      (node (ref "TSB117") (pin "5") (pinfunction "Vcc_5") (pintype "passive"))
      (node (ref "TSB118") (pin "5") (pinfunction "Vcc_5") (pintype "passive"))
      (node (ref "TSB119") (pin "5") (pinfunction "Vcc_5") (pintype "passive"))
      (node (ref "TSB12") (pin "5") (pinfunction "Vcc_5") (pintype "passive"))
      (node (ref "TSB126") (pin "5") (pinfunction "Vcc_5") (pintype "passive"))
      (node (ref "TSB13") (pin "5") (pinfunction "Vcc_5") (pintype "passive"))
      (node (ref "TSB14") (pin "5") (pinfunction "Vcc_5") (pintype "passive"))
      (node (ref "TSB15") (pin "5") (pinfunction "Vcc_5") (pintype "passive"))
      (node (ref "TSB16") (pin "5") (pinfunction "Vcc_5") (pintype "passive"))
      (node (ref "TSB17") (pin "5") (pinfunction "Vcc_5") (pintype "passive"))
      (node (ref "TSB18") (pin "5") (pinfunction "Vcc_5") (pintype "passive"))
      (node (ref "TSB19") (pin "5") (pinfunction "Vcc_5") (pintype "passive"))
      (node (ref "TSB2") (pin "5") (pinfunction "Vcc_5") (pintype "passive"))
      (node (ref "TSB20") (pin "5") (pinfunction "Vcc_5") (pintype "passive"))
      (node (ref "TSB21") (pin "5") (pinfunction "Vcc_5") (pintype "passive"))
      (node (ref "TSB22") (pin "5") (pinfunction "Vcc_5") (pintype "passive"))
      (node (ref "TSB23") (pin "5") (pinfunction "Vcc_5") (pintype "passive"))
      (node (ref "TSB24") (pin "5") (pinfunction "Vcc_5") (pintype "passive"))
      (node (ref "TSB25") (pin "5") (pinfunction "Vcc_5") (pintype "passive"))
      (node (ref "TSB26") (pin "5") (pinfunction "Vcc_5") (pintype "passive"))
      (node (ref "TSB27") (pin "5") (pinfunction "Vcc_5") (pintype "passive"))
      (node (ref "TSB28") (pin "5") (pinfunction "Vcc_5") (pintype "passive"))
      (node (ref "TSB29") (pin "5") (pinfunction "Vcc_5") (pintype "passive"))
      (node (ref "TSB3") (pin "5") (pinfunction "Vcc_5") (pintype "passive"))
      (node (ref "TSB30") (pin "5") (pinfunction "Vcc_5") (pintype "passive"))
      (node (ref "TSB31") (pin "5") (pinfunction "Vcc_5") (pintype "passive"))
      (node (ref "TSB32") (pin "5") (pinfunction "Vcc_5") (pintype "passive"))
      (node (ref "TSB33") (pin "5") (pinfunction "Vcc_5") (pintype "passive"))
      (node (ref "TSB34") (pin "5") (pinfunction "Vcc_5") (pintype "passive"))
      (node (ref "TSB35") (pin "5") (pinfunction "Vcc_5") (pintype "passive"))
      (node (ref "TSB36") (pin "5") (pinfunction "Vcc_5") (pintype "passive"))
      (node (ref "TSB37") (pin "5") (pinfunction "Vcc_5") (pintype "passive"))
      (node (ref "TSB38") (pin "5") (pinfunction "Vcc_5") (pintype "passive"))
      (node (ref "TSB39") (pin "5") (pinfunction "Vcc_5") (pintype "passive"))
      (node (ref "TSB4") (pin "5") (pinfunction "Vcc_5") (pintype "passive"))
      (node (ref "TSB40") (pin "5") (pinfunction "Vcc_5") (pintype "passive"))
      (node (ref "TSB41") (pin "5") (pinfunction "Vcc_5") (pintype "passive"))
      (node (ref "TSB42") (pin "5") (pinfunction "Vcc_5") (pintype "passive"))
      (node (ref "TSB43") (pin "5") (pinfunction "Vcc_5") (pintype "passive"))
      (node (ref "TSB44") (pin "5") (pinfunction "Vcc_5") (pintype "passive"))
      (node (ref "TSB45") (pin "5") (pinfunction "Vcc_5") (pintype "passive"))
      (node (ref "TSB46") (pin "5") (pinfunction "Vcc_5") (pintype "passive"))
      (node (ref "TSB47") (pin "5") (pinfunction "Vcc_5") (pintype "passive"))
      (node (ref "TSB48") (pin "5") (pinfunction "Vcc_5") (pintype "passive"))
      (node (ref "TSB49") (pin "5") (pinfunction "Vcc_5") (pintype "passive"))
      (node (ref "TSB5") (pin "5") (pinfunction "Vcc_5") (pintype "passive"))
      (node (ref "TSB50") (pin "5") (pinfunction "Vcc_5") (pintype "passive"))
      (node (ref "TSB51") (pin "5") (pinfunction "Vcc_5") (pintype "passive"))
      (node (ref "TSB52") (pin "5") (pinfunction "Vcc_5") (pintype "passive"))
      (node (ref "TSB53") (pin "5") (pinfunction "Vcc_5") (pintype "passive"))
      (node (ref "TSB54") (pin "5") (pinfunction "Vcc_5") (pintype "passive"))
      (node (ref "TSB55") (pin "5") (pinfunction "Vcc_5") (pintype "passive"))
      (node (ref "TSB56") (pin "5") (pinfunction "Vcc_5") (pintype "passive"))
      (node (ref "TSB57") (pin "5") (pinfunction "Vcc_5") (pintype "passive"))
      (node (ref "TSB58") (pin "5") (pinfunction "Vcc_5") (pintype "passive"))
      (node (ref "TSB59") (pin "5") (pinfunction "Vcc_5") (pintype "passive"))
      (node (ref "TSB6") (pin "5") (pinfunction "Vcc_5") (pintype "passive"))
      (node (ref "TSB60") (pin "5") (pinfunction "Vcc_5") (pintype "passive"))
      (node (ref "TSB61") (pin "5") (pinfunction "Vcc_5") (pintype "passive"))
      (node (ref "TSB62") (pin "5") (pinfunction "Vcc_5") (pintype "passive"))
      (node (ref "TSB63") (pin "5") (pinfunction "Vcc_5") (pintype "passive"))
      (node (ref "TSB64") (pin "5") (pinfunction "Vcc_5") (pintype "passive"))
      (node (ref "TSB65") (pin "5") (pinfunction "Vcc_5") (pintype "passive"))
      (node (ref "TSB66") (pin "5") (pinfunction "Vcc_5") (pintype "passive"))
      (node (ref "TSB67") (pin "5") (pinfunction "Vcc_5") (pintype "passive"))
      (node (ref "TSB68") (pin "5") (pinfunction "Vcc_5") (pintype "passive"))
      (node (ref "TSB69") (pin "5") (pinfunction "Vcc_5") (pintype "passive"))
      (node (ref "TSB7") (pin "5") (pinfunction "Vcc_5") (pintype "passive"))
      (node (ref "TSB70") (pin "5") (pinfunction "Vcc_5") (pintype "passive"))
      (node (ref "TSB71") (pin "5") (pinfunction "Vcc_5") (pintype "passive"))
      (node (ref "TSB72") (pin "5") (pinfunction "Vcc_5") (pintype "passive"))
      (node (ref "TSB73") (pin "5") (pinfunction "Vcc_5") (pintype "passive"))
      (node (ref "TSB74") (pin "5") (pinfunction "Vcc_5") (pintype "passive"))
      (node (ref "TSB75") (pin "5") (pinfunction "Vcc_5") (pintype "passive"))
      (node (ref "TSB76") (pin "5") (pinfunction "Vcc_5") (pintype "passive"))
      (node (ref "TSB77") (pin "5") (pinfunction "Vcc_5") (pintype "passive"))
      (node (ref "TSB78") (pin "5") (pinfunction "Vcc_5") (pintype "passive"))
      (node (ref "TSB79") (pin "5") (pinfunction "Vcc_5") (pintype "passive"))
      (node (ref "TSB8") (pin "5") (pinfunction "Vcc_5") (pintype "passive"))
      (node (ref "TSB80") (pin "5") (pinfunction "Vcc_5") (pintype "passive"))
      (node (ref "TSB81") (pin "5") (pinfunction "Vcc_5") (pintype "passive"))
      (node (ref "TSB82") (pin "5") (pinfunction "Vcc_5") (pintype "passive"))
      (node (ref "TSB83") (pin "5") (pinfunction "Vcc_5") (pintype "passive"))
      (node (ref "TSB84") (pin "5") (pinfunction "Vcc_5") (pintype "passive"))
      (node (ref "TSB85") (pin "5") (pinfunction "Vcc_5") (pintype "passive"))
      (node (ref "TSB86") (pin "5") (pinfunction "Vcc_5") (pintype "passive"))
      (node (ref "TSB87") (pin "5") (pinfunction "Vcc_5") (pintype "passive"))
      (node (ref "TSB88") (pin "5") (pinfunction "Vcc_5") (pintype "passive"))
      (node (ref "TSB89") (pin "5") (pinfunction "Vcc_5") (pintype "passive"))
      (node (ref "TSB9") (pin "5") (pinfunction "Vcc_5") (pintype "passive"))
      (node (ref "TSB90") (pin "5") (pinfunction "Vcc_5") (pintype "passive"))
      (node (ref "TSB91") (pin "5") (pinfunction "Vcc_5") (pintype "passive"))
      (node (ref "TSB92") (pin "5") (pinfunction "Vcc_5") (pintype "passive"))
      (node (ref "TSB93") (pin "5") (pinfunction "Vcc_5") (pintype "passive"))
      (node (ref "TSB94") (pin "5") (pinfunction "Vcc_5") (pintype "passive"))
      (node (ref "TSB95") (pin "5") (pinfunction "Vcc_5") (pintype "passive"))
      (node (ref "TSB96") (pin "5") (pinfunction "Vcc_5") (pintype "passive"))
      (node (ref "TSB97") (pin "5") (pinfunction "Vcc_5") (pintype "passive"))
      (node (ref "TSB98") (pin "5") (pinfunction "Vcc_5") (pintype "passive"))
      (node (ref "TSB99") (pin "5") (pinfunction "Vcc_5") (pintype "passive"))
    )
    (net (code "139") (name "/Y0") (class "Default")
      (node (ref "TSB1") (pin "4") (pinfunction "Y_4") (pintype "passive"))
    )
    (net (code "140") (name "/Y1") (class "Default")
      (node (ref "TSB8") (pin "4") (pinfunction "Y_4") (pintype "passive"))
    )
    (net (code "141") (name "/Y2") (class "Default")
      (node (ref "TSB15") (pin "4") (pinfunction "Y_4") (pintype "passive"))
    )
    (net (code "142") (name "/Y3") (class "Default")
      (node (ref "TSB22") (pin "4") (pinfunction "Y_4") (pintype "passive"))
    )
    (net (code "143") (name "/Y4") (class "Default")
      (node (ref "TSB29") (pin "4") (pinfunction "Y_4") (pintype "passive"))
    )
    (net (code "144") (name "/Y5") (class "Default")
      (node (ref "TSB36") (pin "4") (pinfunction "Y_4") (pintype "passive"))
    )
    (net (code "145") (name "/Y6") (class "Default")
      (node (ref "TSB43") (pin "4") (pinfunction "Y_4") (pintype "passive"))
    )
    (net (code "146") (name "/Y7") (class "Default")
      (node (ref "TSB50") (pin "4") (pinfunction "Y_4") (pintype "passive"))
    )
    (net (code "147") (name "/Y8") (class "Default")
      (node (ref "TSB57") (pin "4") (pinfunction "Y_4") (pintype "passive"))
    )
    (net (code "148") (name "/Y9") (class "Default")
      (node (ref "TSB64") (pin "4") (pinfunction "Y_4") (pintype "passive"))
    )
    (net (code "149") (name "/Y10") (class "Default")
      (node (ref "TSB71") (pin "4") (pinfunction "Y_4") (pintype "passive"))
    )
    (net (code "150") (name "/Y11") (class "Default")
      (node (ref "TSB78") (pin "4") (pinfunction "Y_4") (pintype "passive"))
    )
    (net (code "151") (name "/Y12") (class "Default")
      (node (ref "TSB85") (pin "4") (pinfunction "Y_4") (pintype "passive"))
    )
    (net (code "152") (name "/Y13") (class "Default")
      (node (ref "TSB92") (pin "4") (pinfunction "Y_4") (pintype "passive"))
    )
    (net (code "153") (name "/Y14") (class "Default")
      (node (ref "TSB99") (pin "4") (pinfunction "Y_4") (pintype "passive"))
    )
    (net (code "154") (name "/Y15") (class "Default")
      (node (ref "TSB106") (pin "4") (pinfunction "Y_4") (pintype "passive"))
    )
    (net (code "155") (name "/Y16") (class "Default")
      (node (ref "TSB113") (pin "4") (pinfunction "Y_4") (pintype "passive"))
    )
    (net (code "156") (name "/Y17") (class "Default")
      (node (ref "TSB120") (pin "4") (pinfunction "Y_4") (pintype "passive"))
    )
    (net (code "157") (name "/Y18") (class "Default")
      (node (ref "TSB2") (pin "4") (pinfunction "Y_4") (pintype "passive"))
    )
    (net (code "158") (name "/Y19") (class "Default")
      (node (ref "TSB9") (pin "4") (pinfunction "Y_4") (pintype "passive"))
    )
    (net (code "159") (name "/Y20") (class "Default")
      (node (ref "TSB16") (pin "4") (pinfunction "Y_4") (pintype "passive"))
    )
    (net (code "160") (name "/Y21") (class "Default")
      (node (ref "TSB23") (pin "4") (pinfunction "Y_4") (pintype "passive"))
    )
    (net (code "161") (name "/Y22") (class "Default")
      (node (ref "TSB30") (pin "4") (pinfunction "Y_4") (pintype "passive"))
    )
    (net (code "162") (name "/Y23") (class "Default")
      (node (ref "TSB37") (pin "4") (pinfunction "Y_4") (pintype "passive"))
    )
    (net (code "163") (name "/Y24") (class "Default")
      (node (ref "TSB44") (pin "4") (pinfunction "Y_4") (pintype "passive"))
    )
    (net (code "164") (name "/Y25") (class "Default")
      (node (ref "TSB51") (pin "4") (pinfunction "Y_4") (pintype "passive"))
    )
    (net (code "165") (name "/Y26") (class "Default")
      (node (ref "TSB58") (pin "4") (pinfunction "Y_4") (pintype "passive"))
    )
    (net (code "166") (name "/Y27") (class "Default")
      (node (ref "TSB65") (pin "4") (pinfunction "Y_4") (pintype "passive"))
    )
    (net (code "167") (name "/Y28") (class "Default")
      (node (ref "TSB72") (pin "4") (pinfunction "Y_4") (pintype "passive"))
    )
    (net (code "168") (name "/Y29") (class "Default")
      (node (ref "TSB79") (pin "4") (pinfunction "Y_4") (pintype "passive"))
    )
    (net (code "169") (name "/Y30") (class "Default")
      (node (ref "TSB86") (pin "4") (pinfunction "Y_4") (pintype "passive"))
    )
    (net (code "170") (name "/Y31") (class "Default")
      (node (ref "TSB93") (pin "4") (pinfunction "Y_4") (pintype "passive"))
    )
    (net (code "171") (name "/Y32") (class "Default")
      (node (ref "TSB100") (pin "4") (pinfunction "Y_4") (pintype "passive"))
    )
    (net (code "172") (name "/Y33") (class "Default")
      (node (ref "TSB107") (pin "4") (pinfunction "Y_4") (pintype "passive"))
    )
    (net (code "173") (name "/Y34") (class "Default")
      (node (ref "TSB114") (pin "4") (pinfunction "Y_4") (pintype "passive"))
    )
    (net (code "174") (name "/Y35") (class "Default")
      (node (ref "TSB121") (pin "4") (pinfunction "Y_4") (pintype "passive"))
    )
    (net (code "175") (name "/Y36") (class "Default")
      (node (ref "TSB3") (pin "4") (pinfunction "Y_4") (pintype "passive"))
    )
    (net (code "176") (name "/Y37") (class "Default")
      (node (ref "TSB10") (pin "4") (pinfunction "Y_4") (pintype "passive"))
    )
    (net (code "177") (name "/Y38") (class "Default")
      (node (ref "TSB17") (pin "4") (pinfunction "Y_4") (pintype "passive"))
    )
    (net (code "178") (name "/Y39") (class "Default")
      (node (ref "TSB24") (pin "4") (pinfunction "Y_4") (pintype "passive"))
    )
    (net (code "179") (name "/Y40") (class "Default")
      (node (ref "TSB31") (pin "4") (pinfunction "Y_4") (pintype "passive"))
    )
    (net (code "180") (name "/Y41") (class "Default")
      (node (ref "TSB38") (pin "4") (pinfunction "Y_4") (pintype "passive"))
    )
    (net (code "181") (name "/Y42") (class "Default")
      (node (ref "TSB45") (pin "4") (pinfunction "Y_4") (pintype "passive"))
    )
    (net (code "182") (name "/Y43") (class "Default")
      (node (ref "TSB52") (pin "4") (pinfunction "Y_4") (pintype "passive"))
    )
    (net (code "183") (name "/Y44") (class "Default")
      (node (ref "TSB59") (pin "4") (pinfunction "Y_4") (pintype "passive"))
    )
    (net (code "184") (name "/Y45") (class "Default")
      (node (ref "TSB66") (pin "4") (pinfunction "Y_4") (pintype "passive"))
    )
    (net (code "185") (name "/Y46") (class "Default")
      (node (ref "TSB73") (pin "4") (pinfunction "Y_4") (pintype "passive"))
    )
    (net (code "186") (name "/Y47") (class "Default")
      (node (ref "TSB80") (pin "4") (pinfunction "Y_4") (pintype "passive"))
    )
    (net (code "187") (name "/Y48") (class "Default")
      (node (ref "TSB87") (pin "1") (pinfunction "~OE_1") (pintype "passive"))
      (node (ref "TSB87") (pin "4") (pinfunction "Y_4") (pintype "passive"))
    )
    (net (code "188") (name "/Y49") (class "Default")
      (node (ref "TSB94") (pin "1") (pinfunction "~OE_1") (pintype "passive"))
      (node (ref "TSB94") (pin "4") (pinfunction "Y_4") (pintype "passive"))
    )
    (net (code "189") (name "/Y50") (class "Default")
      (node (ref "TSB101") (pin "1") (pinfunction "~OE_1") (pintype "passive"))
      (node (ref "TSB101") (pin "4") (pinfunction "Y_4") (pintype "passive"))
    )
    (net (code "190") (name "/Y51") (class "Default")
      (node (ref "TSB108") (pin "1") (pinfunction "~OE_1") (pintype "passive"))
      (node (ref "TSB108") (pin "4") (pinfunction "Y_4") (pintype "passive"))
    )
    (net (code "191") (name "/Y52") (class "Default")
      (node (ref "TSB115") (pin "1") (pinfunction "~OE_1") (pintype "passive"))
      (node (ref "TSB115") (pin "4") (pinfunction "Y_4") (pintype "passive"))
    )
    (net (code "192") (name "/Y53") (class "Default")
      (node (ref "TSB122") (pin "1") (pinfunction "~OE_1") (pintype "passive"))
      (node (ref "TSB122") (pin "4") (pinfunction "Y_4") (pintype "passive"))
    )
    (net (code "193") (name "/Y54") (class "Default")
      (node (ref "TSB4") (pin "1") (pinfunction "~OE_1") (pintype "passive"))
      (node (ref "TSB4") (pin "4") (pinfunction "Y_4") (pintype "passive"))
    )
    (net (code "194") (name "/Y55") (class "Default")
      (node (ref "TSB11") (pin "1") (pinfunction "~OE_1") (pintype "passive"))
      (node (ref "TSB11") (pin "4") (pinfunction "Y_4") (pintype "passive"))
    )
    (net (code "195") (name "/Y56") (class "Default")
      (node (ref "TSB18") (pin "1") (pinfunction "~OE_1") (pintype "passive"))
      (node (ref "TSB18") (pin "4") (pinfunction "Y_4") (pintype "passive"))
    )
    (net (code "196") (name "/Y57") (class "Default")
      (node (ref "TSB25") (pin "1") (pinfunction "~OE_1") (pintype "passive"))
      (node (ref "TSB25") (pin "4") (pinfunction "Y_4") (pintype "passive"))
    )
    (net (code "197") (name "/Y58") (class "Default")
      (node (ref "TSB32") (pin "1") (pinfunction "~OE_1") (pintype "passive"))
      (node (ref "TSB32") (pin "4") (pinfunction "Y_4") (pintype "passive"))
    )
    (net (code "198") (name "/Y59") (class "Default")
      (node (ref "TSB39") (pin "1") (pinfunction "~OE_1") (pintype "passive"))
      (node (ref "TSB39") (pin "4") (pinfunction "Y_4") (pintype "passive"))
    )
    (net (code "199") (name "/Y60") (class "Default")
      (node (ref "TSB46") (pin "1") (pinfunction "~OE_1") (pintype "passive"))
      (node (ref "TSB46") (pin "4") (pinfunction "Y_4") (pintype "passive"))
    )
    (net (code "200") (name "/Y61") (class "Default")
      (node (ref "TSB53") (pin "1") (pinfunction "~OE_1") (pintype "passive"))
      (node (ref "TSB53") (pin "4") (pinfunction "Y_4") (pintype "passive"))
    )
    (net (code "201") (name "/Y62") (class "Default")
      (node (ref "TSB60") (pin "1") (pinfunction "~OE_1") (pintype "passive"))
      (node (ref "TSB60") (pin "4") (pinfunction "Y_4") (pintype "passive"))
    )
    (net (code "202") (name "/Y63") (class "Default")
      (node (ref "TSB67") (pin "1") (pinfunction "~OE_1") (pintype "passive"))
      (node (ref "TSB67") (pin "4") (pinfunction "Y_4") (pintype "passive"))
    )
    (net (code "203") (name "/Y64") (class "Default")
      (node (ref "TSB74") (pin "4") (pinfunction "Y_4") (pintype "passive"))
    )
    (net (code "204") (name "/Y65") (class "Default")
      (node (ref "TSB81") (pin "4") (pinfunction "Y_4") (pintype "passive"))
    )
    (net (code "205") (name "/Y66") (class "Default")
      (node (ref "TSB88") (pin "4") (pinfunction "Y_4") (pintype "passive"))
    )
    (net (code "206") (name "/Y67") (class "Default")
      (node (ref "TSB95") (pin "4") (pinfunction "Y_4") (pintype "passive"))
    )
    (net (code "207") (name "/Y68") (class "Default")
      (node (ref "TSB102") (pin "4") (pinfunction "Y_4") (pintype "passive"))
    )
    (net (code "208") (name "/Y69") (class "Default")
      (node (ref "TSB109") (pin "4") (pinfunction "Y_4") (pintype "passive"))
    )
    (net (code "209") (name "/Y70") (class "Default")
      (node (ref "TSB116") (pin "4") (pinfunction "Y_4") (pintype "passive"))
    )
    (net (code "210") (name "/Y71") (class "Default")
      (node (ref "TSB123") (pin "4") (pinfunction "Y_4") (pintype "passive"))
    )
    (net (code "211") (name "/Y72") (class "Default")
      (node (ref "TSB5") (pin "4") (pinfunction "Y_4") (pintype "passive"))
    )
    (net (code "212") (name "/Y73") (class "Default")
      (node (ref "TSB12") (pin "4") (pinfunction "Y_4") (pintype "passive"))
    )
    (net (code "213") (name "/Y74") (class "Default")
      (node (ref "TSB19") (pin "4") (pinfunction "Y_4") (pintype "passive"))
    )
    (net (code "214") (name "/Y75") (class "Default")
      (node (ref "TSB26") (pin "4") (pinfunction "Y_4") (pintype "passive"))
    )
    (net (code "215") (name "/Y76") (class "Default")
      (node (ref "TSB33") (pin "4") (pinfunction "Y_4") (pintype "passive"))
    )
    (net (code "216") (name "/Y77") (class "Default")
      (node (ref "TSB40") (pin "4") (pinfunction "Y_4") (pintype "passive"))
    )
    (net (code "217") (name "/Y78") (class "Default")
      (node (ref "TSB47") (pin "4") (pinfunction "Y_4") (pintype "passive"))
    )
    (net (code "218") (name "/Y79") (class "Default")
      (node (ref "TSB54") (pin "4") (pinfunction "Y_4") (pintype "passive"))
    )
    (net (code "219") (name "/Y80") (class "Default")
      (node (ref "TSB61") (pin "4") (pinfunction "Y_4") (pintype "passive"))
    )
    (net (code "220") (name "/Y81") (class "Default")
      (node (ref "TSB68") (pin "4") (pinfunction "Y_4") (pintype "passive"))
    )
    (net (code "221") (name "/Y82") (class "Default")
      (node (ref "TSB75") (pin "4") (pinfunction "Y_4") (pintype "passive"))
    )
    (net (code "222") (name "/Y83") (class "Default")
      (node (ref "TSB82") (pin "4") (pinfunction "Y_4") (pintype "passive"))
    )
    (net (code "223") (name "/Y84") (class "Default")
      (node (ref "TSB89") (pin "4") (pinfunction "Y_4") (pintype "passive"))
    )
    (net (code "224") (name "/Y85") (class "Default")
      (node (ref "TSB96") (pin "4") (pinfunction "Y_4") (pintype "passive"))
    )
    (net (code "225") (name "/Y86") (class "Default")
      (node (ref "TSB103") (pin "4") (pinfunction "Y_4") (pintype "passive"))
    )
    (net (code "226") (name "/Y87") (class "Default")
      (node (ref "TSB110") (pin "4") (pinfunction "Y_4") (pintype "passive"))
    )
    (net (code "227") (name "/Y88") (class "Default")
      (node (ref "TSB117") (pin "4") (pinfunction "Y_4") (pintype "passive"))
    )
    (net (code "228") (name "/Y89") (class "Default")
      (node (ref "TSB124") (pin "4") (pinfunction "Y_4") (pintype "passive"))
    )
    (net (code "229") (name "/Y90") (class "Default")
      (node (ref "TSB6") (pin "4") (pinfunction "Y_4") (pintype "passive"))
    )
    (net (code "230") (name "/Y91") (class "Default")
      (node (ref "TSB13") (pin "4") (pinfunction "Y_4") (pintype "passive"))
    )
    (net (code "231") (name "/Y92") (class "Default")
      (node (ref "TSB20") (pin "4") (pinfunction "Y_4") (pintype "passive"))
    )
    (net (code "232") (name "/Y93") (class "Default")
      (node (ref "TSB27") (pin "4") (pinfunction "Y_4") (pintype "passive"))
    )
    (net (code "233") (name "/Y94") (class "Default")
      (node (ref "TSB34") (pin "4") (pinfunction "Y_4") (pintype "passive"))
    )
    (net (code "234") (name "/Y95") (class "Default")
      (node (ref "TSB41") (pin "4") (pinfunction "Y_4") (pintype "passive"))
    )
    (net (code "235") (name "/Y96") (class "Default")
      (node (ref "TSB48") (pin "4") (pinfunction "Y_4") (pintype "passive"))
    )
    (net (code "236") (name "/Y97") (class "Default")
      (node (ref "TSB55") (pin "4") (pinfunction "Y_4") (pintype "passive"))
    )
    (net (code "237") (name "/Y98") (class "Default")
      (node (ref "TSB62") (pin "4") (pinfunction "Y_4") (pintype "passive"))
    )
    (net (code "238") (name "/Y99") (class "Default")
      (node (ref "TSB69") (pin "4") (pinfunction "Y_4") (pintype "passive"))
    )
    (net (code "239") (name "/Y100") (class "Default")
      (node (ref "TSB76") (pin "4") (pinfunction "Y_4") (pintype "passive"))
    )
    (net (code "240") (name "/Y101") (class "Default")
      (node (ref "TSB83") (pin "4") (pinfunction "Y_4") (pintype "passive"))
    )
    (net (code "241") (name "/Y102") (class "Default")
      (node (ref "TSB90") (pin "4") (pinfunction "Y_4") (pintype "passive"))
    )
    (net (code "242") (name "/Y103") (class "Default")
      (node (ref "TSB97") (pin "4") (pinfunction "Y_4") (pintype "passive"))
    )
    (net (code "243") (name "/Y104") (class "Default")
      (node (ref "TSB104") (pin "4") (pinfunction "Y_4") (pintype "passive"))
    )
    (net (code "244") (name "/Y105") (class "Default")
      (node (ref "TSB111") (pin "4") (pinfunction "Y_4") (pintype "passive"))
    )
    (net (code "245") (name "/Y106") (class "Default")
      (node (ref "TSB118") (pin "4") (pinfunction "Y_4") (pintype "passive"))
    )
    (net (code "246") (name "/Y107") (class "Default")
      (node (ref "TSB125") (pin "4") (pinfunction "Y_4") (pintype "passive"))
    )
    (net (code "247") (name "/Y108") (class "Default")
      (node (ref "TSB7") (pin "4") (pinfunction "Y_4") (pintype "passive"))
    )
    (net (code "248") (name "/Y109") (class "Default")
      (node (ref "TSB14") (pin "4") (pinfunction "Y_4") (pintype "passive"))
    )
    (net (code "249") (name "/Y110") (class "Default")
      (node (ref "TSB21") (pin "4") (pinfunction "Y_4") (pintype "passive"))
    )
    (net (code "250") (name "/Y111") (class "Default")
      (node (ref "TSB28") (pin "4") (pinfunction "Y_4") (pintype "passive"))
    )
    (net (code "251") (name "/Y112") (class "Default")
      (node (ref "TSB35") (pin "4") (pinfunction "Y_4") (pintype "passive"))
    )
    (net (code "252") (name "/Y113") (class "Default")
      (node (ref "TSB42") (pin "4") (pinfunction "Y_4") (pintype "passive"))
    )
    (net (code "253") (name "/Y114") (class "Default")
      (node (ref "TSB49") (pin "4") (pinfunction "Y_4") (pintype "passive"))
    )
    (net (code "254") (name "/Y115") (class "Default")
      (node (ref "TSB56") (pin "4") (pinfunction "Y_4") (pintype "passive"))
    )
    (net (code "255") (name "/Y116") (class "Default")
      (node (ref "TSB63") (pin "4") (pinfunction "Y_4") (pintype "passive"))
    )
    (net (code "256") (name "/Y117") (class "Default")
      (node (ref "TSB70") (pin "4") (pinfunction "Y_4") (pintype "passive"))
    )
    (net (code "257") (name "/Y118") (class "Default")
      (node (ref "TSB77") (pin "4") (pinfunction "Y_4") (pintype "passive"))
    )
    (net (code "258") (name "/Y119") (class "Default")
      (node (ref "TSB84") (pin "4") (pinfunction "Y_4") (pintype "passive"))
    )
    (net (code "259") (name "/Y120") (class "Default")
      (node (ref "TSB91") (pin "4") (pinfunction "Y_4") (pintype "passive"))
    )
    (net (code "260") (name "/Y121") (class "Default")
      (node (ref "TSB98") (pin "4") (pinfunction "Y_4") (pintype "passive"))
    )
    (net (code "261") (name "/Y122") (class "Default")
      (node (ref "TSB105") (pin "4") (pinfunction "Y_4") (pintype "passive"))
    )
    (net (code "262") (name "/Y123") (class "Default")
      (node (ref "TSB112") (pin "4") (pinfunction "Y_4") (pintype "passive"))
    )
    (net (code "263") (name "/Y124") (class "Default")
      (node (ref "TSB119") (pin "4") (pinfunction "Y_4") (pintype "passive"))
    )
    (net (code "264") (name "/Y125") (class "Default")
      (node (ref "TSB126") (pin "4") (pinfunction "Y_4") (pintype "passive"))
    )
    (net (code "265") (name "/Y126") (class "Default")
      (node (ref "TSB127") (pin "4") (pinfunction "Y_4") (pintype "passive"))
    )
    (net (code "266") (name "/Y127") (class "Default")
      (node (ref "TSB128") (pin "4") (pinfunction "Y_4") (pintype "passive"))
    )
    (net (code "275") (name "/~OE0") (class "Default")
      (node (ref "TSB1") (pin "1") (pinfunction "~OE_1") (pintype "passive"))
    )
    (net (code "276") (name "/~OE1") (class "Default")
      (node (ref "TSB8") (pin "1") (pinfunction "~OE_1") (pintype "passive"))
    )
    (net (code "277") (name "/~OE2") (class "Default")
      (node (ref "TSB15") (pin "1") (pinfunction "~OE_1") (pintype "passive"))
    )
    (net (code "278") (name "/~OE3") (class "Default")
      (node (ref "TSB22") (pin "1") (pinfunction "~OE_1") (pintype "passive"))
    )
    (net (code "279") (name "/~OE4") (class "Default")
      (node (ref "TSB29") (pin "1") (pinfunction "~OE_1") (pintype "passive"))
    )
    (net (code "280") (name "/~OE5") (class "Default")
      (node (ref "TSB36") (pin "1") (pinfunction "~OE_1") (pintype "passive"))
    )
    (net (code "281") (name "/~OE6") (class "Default")
      (node (ref "TSB43") (pin "1") (pinfunction "~OE_1") (pintype "passive"))
    )
    (net (code "282") (name "/~OE7") (class "Default")
      (node (ref "TSB50") (pin "1") (pinfunction "~OE_1") (pintype "passive"))
    )
    (net (code "283") (name "/~OE8") (class "Default")
      (node (ref "TSB57") (pin "1") (pinfunction "~OE_1") (pintype "passive"))
    )
    (net (code "284") (name "/~OE9") (class "Default")
      (node (ref "TSB64") (pin "1") (pinfunction "~OE_1") (pintype "passive"))
    )
    (net (code "285") (name "/~OE10") (class "Default")
      (node (ref "TSB71") (pin "1") (pinfunction "~OE_1") (pintype "passive"))
    )
    (net (code "286") (name "/~OE11") (class "Default")
      (node (ref "TSB78") (pin "1") (pinfunction "~OE_1") (pintype "passive"))
    )
    (net (code "287") (name "/~OE12") (class "Default")
      (node (ref "TSB85") (pin "1") (pinfunction "~OE_1") (pintype "passive"))
    )
    (net (code "288") (name "/~OE13") (class "Default")
      (node (ref "TSB92") (pin "1") (pinfunction "~OE_1") (pintype "passive"))
    )
    (net (code "289") (name "/~OE14") (class "Default")
      (node (ref "TSB99") (pin "1") (pinfunction "~OE_1") (pintype "passive"))
    )
    (net (code "290") (name "/~OE15") (class "Default")
      (node (ref "TSB106") (pin "1") (pinfunction "~OE_1") (pintype "passive"))
    )
    (net (code "291") (name "/~OE16") (class "Default")
      (node (ref "TSB113") (pin "1") (pinfunction "~OE_1") (pintype "passive"))
    )
    (net (code "292") (name "/~OE17") (class "Default")
      (node (ref "TSB120") (pin "1") (pinfunction "~OE_1") (pintype "passive"))
    )
    (net (code "293") (name "/~OE18") (class "Default")
      (node (ref "TSB2") (pin "1") (pinfunction "~OE_1") (pintype "passive"))
    )
    (net (code "294") (name "/~OE19") (class "Default")
      (node (ref "TSB9") (pin "1") (pinfunction "~OE_1") (pintype "passive"))
    )
    (net (code "295") (name "/~OE20") (class "Default")
      (node (ref "TSB16") (pin "1") (pinfunction "~OE_1") (pintype "passive"))
    )
    (net (code "296") (name "/~OE21") (class "Default")
      (node (ref "TSB23") (pin "1") (pinfunction "~OE_1") (pintype "passive"))
    )
    (net (code "297") (name "/~OE22") (class "Default")
      (node (ref "TSB30") (pin "1") (pinfunction "~OE_1") (pintype "passive"))
    )
    (net (code "298") (name "/~OE23") (class "Default")
      (node (ref "TSB37") (pin "1") (pinfunction "~OE_1") (pintype "passive"))
    )
    (net (code "299") (name "/~OE24") (class "Default")
      (node (ref "TSB44") (pin "1") (pinfunction "~OE_1") (pintype "passive"))
    )
    (net (code "300") (name "/~OE25") (class "Default")
      (node (ref "TSB51") (pin "1") (pinfunction "~OE_1") (pintype "passive"))
    )
    (net (code "301") (name "/~OE26") (class "Default")
      (node (ref "TSB58") (pin "1") (pinfunction "~OE_1") (pintype "passive"))
    )
    (net (code "302") (name "/~OE27") (class "Default")
      (node (ref "TSB65") (pin "1") (pinfunction "~OE_1") (pintype "passive"))
    )
    (net (code "303") (name "/~OE28") (class "Default")
      (node (ref "TSB72") (pin "1") (pinfunction "~OE_1") (pintype "passive"))
    )
    (net (code "304") (name "/~OE29") (class "Default")
      (node (ref "TSB79") (pin "1") (pinfunction "~OE_1") (pintype "passive"))
    )
    (net (code "305") (name "/~OE30") (class "Default")
      (node (ref "TSB86") (pin "1") (pinfunction "~OE_1") (pintype "passive"))
    )
    (net (code "306") (name "/~OE31") (class "Default")
      (node (ref "TSB93") (pin "1") (pinfunction "~OE_1") (pintype "passive"))
    )
    (net (code "307") (name "/~OE32") (class "Default")
      (node (ref "TSB100") (pin "1") (pinfunction "~OE_1") (pintype "passive"))
    )
    (net (code "308") (name "/~OE33") (class "Default")
      (node (ref "TSB107") (pin "1") (pinfunction "~OE_1") (pintype "passive"))
    )
    (net (code "309") (name "/~OE34") (class "Default")
      (node (ref "TSB114") (pin "1") (pinfunction "~OE_1") (pintype "passive"))
    )
    (net (code "310") (name "/~OE35") (class "Default")
      (node (ref "TSB121") (pin "1") (pinfunction "~OE_1") (pintype "passive"))
    )
    (net (code "311") (name "/~OE36") (class "Default")
      (node (ref "TSB3") (pin "1") (pinfunction "~OE_1") (pintype "passive"))
    )
    (net (code "312") (name "/~OE37") (class "Default")
      (node (ref "TSB10") (pin "1") (pinfunction "~OE_1") (pintype "passive"))
    )
    (net (code "313") (name "/~OE38") (class "Default")
      (node (ref "TSB17") (pin "1") (pinfunction "~OE_1") (pintype "passive"))
    )
    (net (code "314") (name "/~OE39") (class "Default")
      (node (ref "TSB24") (pin "1") (pinfunction "~OE_1") (pintype "passive"))
    )
    (net (code "315") (name "/~OE40") (class "Default")
      (node (ref "TSB31") (pin "1") (pinfunction "~OE_1") (pintype "passive"))
    )
    (net (code "316") (name "/~OE41") (class "Default")
      (node (ref "TSB38") (pin "1") (pinfunction "~OE_1") (pintype "passive"))
    )
    (net (code "317") (name "/~OE42") (class "Default")
      (node (ref "TSB45") (pin "1") (pinfunction "~OE_1") (pintype "passive"))
    )
    (net (code "318") (name "/~OE43") (class "Default")
      (node (ref "TSB52") (pin "1") (pinfunction "~OE_1") (pintype "passive"))
    )
    (net (code "319") (name "/~OE44") (class "Default")
      (node (ref "TSB59") (pin "1") (pinfunction "~OE_1") (pintype "passive"))
    )
    (net (code "320") (name "/~OE45") (class "Default")
      (node (ref "TSB66") (pin "1") (pinfunction "~OE_1") (pintype "passive"))
    )
    (net (code "321") (name "/~OE46") (class "Default")
      (node (ref "TSB73") (pin "1") (pinfunction "~OE_1") (pintype "passive"))
    )
    (net (code "322") (name "/~OE47") (class "Default")
      (node (ref "TSB80") (pin "1") (pinfunction "~OE_1") (pintype "passive"))
    )
    (net (code "323") (name "/~OE64") (class "Default")
      (node (ref "TSB74") (pin "1") (pinfunction "~OE_1") (pintype "passive"))
    )
    (net (code "324") (name "/~OE65") (class "Default")
      (node (ref "TSB81") (pin "1") (pinfunction "~OE_1") (pintype "passive"))
    )
    (net (code "325") (name "/~OE66") (class "Default")
      (node (ref "TSB88") (pin "1") (pinfunction "~OE_1") (pintype "passive"))
    )
    (net (code "326") (name "/~OE67") (class "Default")
      (node (ref "TSB95") (pin "1") (pinfunction "~OE_1") (pintype "passive"))
    )
    (net (code "327") (name "/~OE68") (class "Default")
      (node (ref "TSB102") (pin "1") (pinfunction "~OE_1") (pintype "passive"))
    )
    (net (code "328") (name "/~OE69") (class "Default")
      (node (ref "TSB109") (pin "1") (pinfunction "~OE_1") (pintype "passive"))
    )
    (net (code "329") (name "/~OE70") (class "Default")
      (node (ref "TSB116") (pin "1") (pinfunction "~OE_1") (pintype "passive"))
    )
    (net (code "330") (name "/~OE71") (class "Default")
      (node (ref "TSB123") (pin "1") (pinfunction "~OE_1") (pintype "passive"))
    )
    (net (code "331") (name "/~OE72") (class "Default")
      (node (ref "TSB5") (pin "1") (pinfunction "~OE_1") (pintype "passive"))
    )
    (net (code "332") (name "/~OE73") (class "Default")
      (node (ref "TSB12") (pin "1") (pinfunction "~OE_1") (pintype "passive"))
    )
    (net (code "333") (name "/~OE74") (class "Default")
      (node (ref "TSB19") (pin "1") (pinfunction "~OE_1") (pintype "passive"))
    )
    (net (code "334") (name "/~OE75") (class "Default")
      (node (ref "TSB26") (pin "1") (pinfunction "~OE_1") (pintype "passive"))
    )
    (net (code "335") (name "/~OE76") (class "Default")
      (node (ref "TSB33") (pin "1") (pinfunction "~OE_1") (pintype "passive"))
    )
    (net (code "336") (name "/~OE77") (class "Default")
      (node (ref "TSB40") (pin "1") (pinfunction "~OE_1") (pintype "passive"))
    )
    (net (code "337") (name "/~OE78") (class "Default")
      (node (ref "TSB47") (pin "1") (pinfunction "~OE_1") (pintype "passive"))
    )
    (net (code "338") (name "/~OE79") (class "Default")
      (node (ref "TSB54") (pin "1") (pinfunction "~OE_1") (pintype "passive"))
    )
    (net (code "339") (name "/~OE80") (class "Default")
      (node (ref "TSB61") (pin "1") (pinfunction "~OE_1") (pintype "passive"))
    )
    (net (code "340") (name "/~OE81") (class "Default")
      (node (ref "TSB68") (pin "1") (pinfunction "~OE_1") (pintype "passive"))
    )
    (net (code "341") (name "/~OE82") (class "Default")
      (node (ref "TSB75") (pin "1") (pinfunction "~OE_1") (pintype "passive"))
    )
    (net (code "342") (name "/~OE83") (class "Default")
      (node (ref "TSB82") (pin "1") (pinfunction "~OE_1") (pintype "passive"))
    )
    (net (code "343") (name "/~OE84") (class "Default")
      (node (ref "TSB89") (pin "1") (pinfunction "~OE_1") (pintype "passive"))
    )
    (net (code "344") (name "/~OE85") (class "Default")
      (node (ref "TSB96") (pin "1") (pinfunction "~OE_1") (pintype "passive"))
    )
    (net (code "345") (name "/~OE86") (class "Default")
      (node (ref "TSB103") (pin "1") (pinfunction "~OE_1") (pintype "passive"))
    )
    (net (code "346") (name "/~OE87") (class "Default")
      (node (ref "TSB110") (pin "1") (pinfunction "~OE_1") (pintype "passive"))
    )
    (net (code "347") (name "/~OE88") (class "Default")
      (node (ref "TSB117") (pin "1") (pinfunction "~OE_1") (pintype "passive"))
    )
    (net (code "348") (name "/~OE89") (class "Default")
      (node (ref "TSB124") (pin "1") (pinfunction "~OE_1") (pintype "passive"))
    )
    (net (code "349") (name "/~OE90") (class "Default")
      (node (ref "TSB6") (pin "1") (pinfunction "~OE_1") (pintype "passive"))
    )
    (net (code "350") (name "/~OE91") (class "Default")
      (node (ref "TSB13") (pin "1") (pinfunction "~OE_1") (pintype "passive"))
    )
    (net (code "351") (name "/~OE92") (class "Default")
      (node (ref "TSB20") (pin "1") (pinfunction "~OE_1") (pintype "passive"))
    )
    (net (code "352") (name "/~OE93") (class "Default")
      (node (ref "TSB27") (pin "1") (pinfunction "~OE_1") (pintype "passive"))
    )
    (net (code "353") (name "/~OE94") (class "Default")
      (node (ref "TSB34") (pin "1") (pinfunction "~OE_1") (pintype "passive"))
    )
    (net (code "354") (name "/~OE95") (class "Default")
      (node (ref "TSB41") (pin "1") (pinfunction "~OE_1") (pintype "passive"))
    )
    (net (code "355") (name "/~OE96") (class "Default")
      (node (ref "TSB48") (pin "1") (pinfunction "~OE_1") (pintype "passive"))
    )
    (net (code "356") (name "/~OE97") (class "Default")
      (node (ref "TSB55") (pin "1") (pinfunction "~OE_1") (pintype "passive"))
    )
    (net (code "357") (name "/~OE98") (class "Default")
      (node (ref "TSB62") (pin "1") (pinfunction "~OE_1") (pintype "passive"))
    )
    (net (code "358") (name "/~OE99") (class "Default")
      (node (ref "TSB69") (pin "1") (pinfunction "~OE_1") (pintype "passive"))
    )
    (net (code "359") (name "/~OE100") (class "Default")
      (node (ref "TSB76") (pin "1") (pinfunction "~OE_1") (pintype "passive"))
    )
    (net (code "360") (name "/~OE101") (class "Default")
      (node (ref "TSB83") (pin "1") (pinfunction "~OE_1") (pintype "passive"))
    )
    (net (code "361") (name "/~OE102") (class "Default")
      (node (ref "TSB90") (pin "1") (pinfunction "~OE_1") (pintype "passive"))
    )
    (net (code "362") (name "/~OE103") (class "Default")
      (node (ref "TSB97") (pin "1") (pinfunction "~OE_1") (pintype "passive"))
    )
    (net (code "363") (name "/~OE104") (class "Default")
      (node (ref "TSB104") (pin "1") (pinfunction "~OE_1") (pintype "passive"))
    )
    (net (code "364") (name "/~OE105") (class "Default")
      (node (ref "TSB111") (pin "1") (pinfunction "~OE_1") (pintype "passive"))
    )
    (net (code "365") (name "/~OE106") (class "Default")
      (node (ref "TSB118") (pin "1") (pinfunction "~OE_1") (pintype "passive"))
    )
    (net (code "366") (name "/~OE107") (class "Default")
      (node (ref "TSB125") (pin "1") (pinfunction "~OE_1") (pintype "passive"))
    )
    (net (code "367") (name "/~OE108") (class "Default")
      (node (ref "TSB7") (pin "1") (pinfunction "~OE_1") (pintype "passive"))
    )
    (net (code "368") (name "/~OE109") (class "Default")
      (node (ref "TSB14") (pin "1") (pinfunction "~OE_1") (pintype "passive"))
    )
    (net (code "369") (name "/~OE110") (class "Default")
      (node (ref "TSB21") (pin "1") (pinfunction "~OE_1") (pintype "passive"))
    )
    (net (code "370") (name "/~OE111") (class "Default")
      (node (ref "TSB28") (pin "1") (pinfunction "~OE_1") (pintype "passive"))
    )
    (net (code "371") (name "/~OE112") (class "Default")
      (node (ref "TSB35") (pin "1") (pinfunction "~OE_1") (pintype "passive"))
    )
    (net (code "372") (name "/~OE113") (class "Default")
      (node (ref "TSB42") (pin "1") (pinfunction "~OE_1") (pintype "passive"))
    )
    (net (code "373") (name "/~OE114") (class "Default")
      (node (ref "TSB49") (pin "1") (pinfunction "~OE_1") (pintype "passive"))
    )
    (net (code "374") (name "/~OE115") (class "Default")
      (node (ref "TSB56") (pin "1") (pinfunction "~OE_1") (pintype "passive"))
    )
    (net (code "375") (name "/~OE116") (class "Default")
      (node (ref "TSB63") (pin "1") (pinfunction "~OE_1") (pintype "passive"))
    )
    (net (code "376") (name "/~OE117") (class "Default")
      (node (ref "TSB70") (pin "1") (pinfunction "~OE_1") (pintype "passive"))
    )
    (net (code "377") (name "/~OE118") (class "Default")
      (node (ref "TSB77") (pin "1") (pinfunction "~OE_1") (pintype "passive"))
    )
    (net (code "378") (name "/~OE119") (class "Default")
      (node (ref "TSB84") (pin "1") (pinfunction "~OE_1") (pintype "passive"))
    )
    (net (code "379") (name "/~OE120") (class "Default")
      (node (ref "TSB91") (pin "1") (pinfunction "~OE_1") (pintype "passive"))
    )
    (net (code "380") (name "/~OE121") (class "Default")
      (node (ref "TSB98") (pin "1") (pinfunction "~OE_1") (pintype "passive"))
    )
    (net (code "381") (name "/~OE122") (class "Default")
      (node (ref "TSB105") (pin "1") (pinfunction "~OE_1") (pintype "passive"))
    )
    (net (code "382") (name "/~OE123") (class "Default")
      (node (ref "TSB112") (pin "1") (pinfunction "~OE_1") (pintype "passive"))
    )
    (net (code "383") (name "/~OE124") (class "Default")
      (node (ref "TSB119") (pin "1") (pinfunction "~OE_1") (pintype "passive"))
    )
    (net (code "384") (name "/~OE125") (class "Default")
      (node (ref "TSB126") (pin "1") (pinfunction "~OE_1") (pintype "passive"))
    )
    (net (code "385") (name "/~OE126") (class "Default")
      (node (ref "TSB127") (pin "1") (pinfunction "~OE_1") (pintype "passive"))
    )
    (net (code "386") (name "/~OE127") (class "Default")
      (node (ref "TSB128") (pin "1") (pinfunction "~OE_1") (pintype "passive"))
    )
    (net (code "394") (name "unconnected-(TSB120-Vcc-Pad5)") (class "Default")
      (node (ref "TSB120") (pin "5") (pinfunction "Vcc_5") (pintype "passive"))
    )
    (net (code "395") (name "unconnected-(TSB121-Vcc-Pad5)") (class "Default")
      (node (ref "TSB121") (pin "5") (pinfunction "Vcc_5") (pintype "passive"))
    )
    (net (code "396") (name "unconnected-(TSB122-GND-Pad3)") (class "Default")
      (node (ref "TSB122") (pin "3") (pinfunction "GND_3") (pintype "passive"))
    )
    (net (code "397") (name "unconnected-(TSB122-Vcc-Pad5)") (class "Default")
      (node (ref "TSB122") (pin "5") (pinfunction "Vcc_5") (pintype "passive"))
    )
    (net (code "398") (name "unconnected-(TSB123-Vcc-Pad5)") (class "Default")
      (node (ref "TSB123") (pin "5") (pinfunction "Vcc_5") (pintype "passive"))
    )
    (net (code "399") (name "unconnected-(TSB124-Vcc-Pad5)") (class "Default")
      (node (ref "TSB124") (pin "5") (pinfunction "Vcc_5") (pintype "passive"))
    )
    (net (code "400") (name "unconnected-(TSB125-Vcc-Pad5)") (class "Default")
      (node (ref "TSB125") (pin "5") (pinfunction "Vcc_5") (pintype "passive"))
    )
    (net (code "401") (name "unconnected-(TSB127-Vcc-Pad5)") (class "Default")
      (node (ref "TSB127") (pin "5") (pinfunction "Vcc_5") (pintype "passive"))
    )
    (net (code "402") (name "unconnected-(TSB128-Vcc-Pad5)") (class "Default")
      (node (ref "TSB128") (pin "5") (pinfunction "Vcc_5") (pintype "passive"))
    )
  )
)
